# Ambisonic_Clock_Decoder_With_Phase_Shift.net
KiCad netlist of a schematic drawn in EAGLE
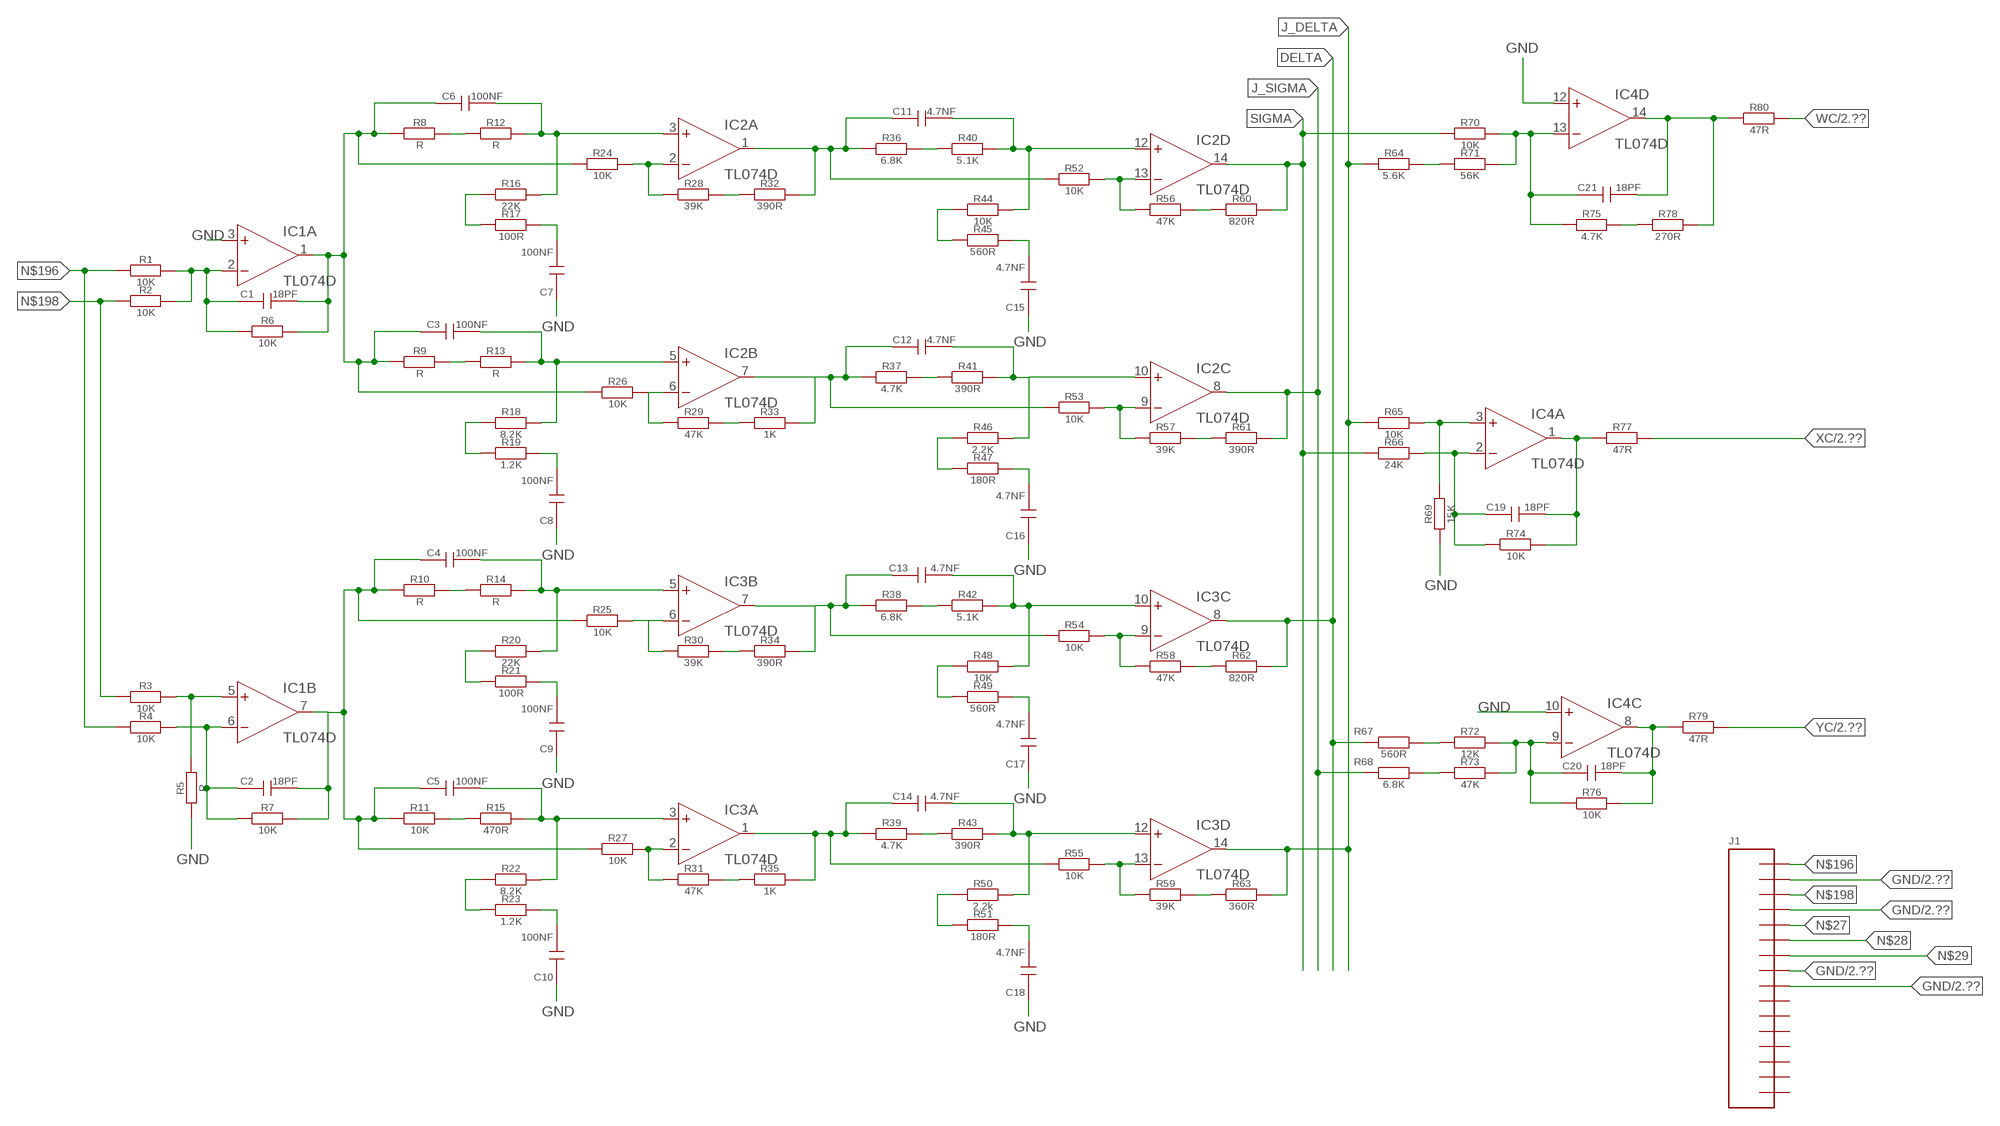
[diagram p0: schematic, sheet 1]
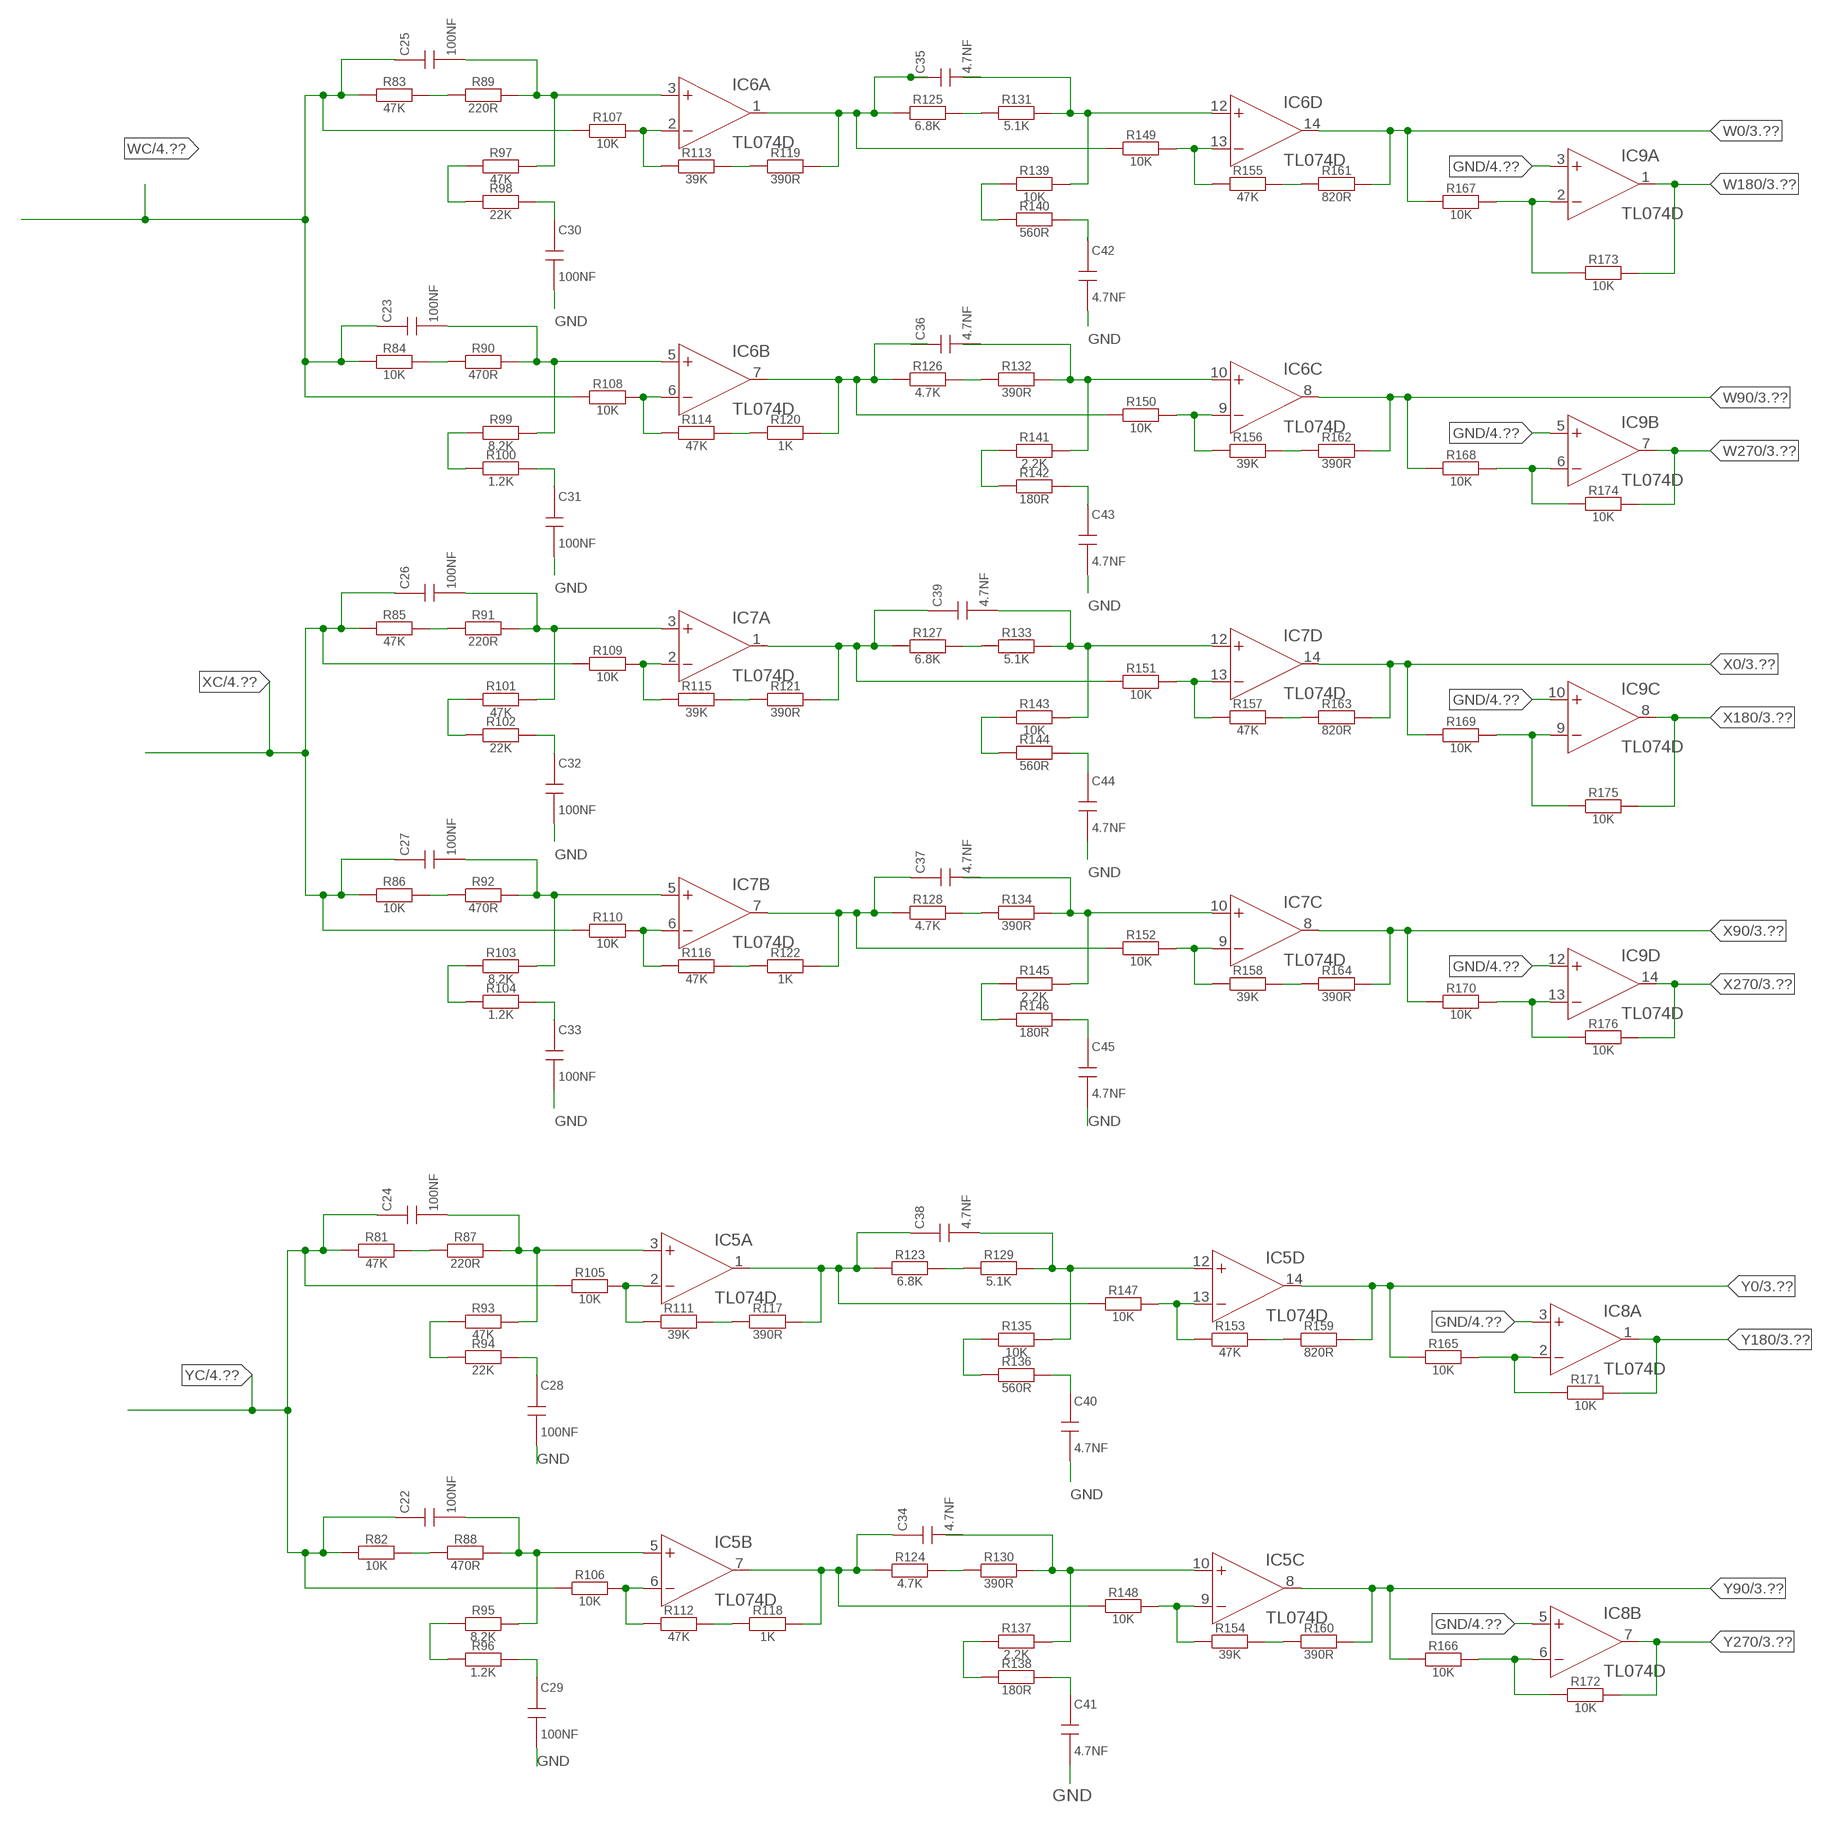
[diagram p1: schematic, sheet 2]
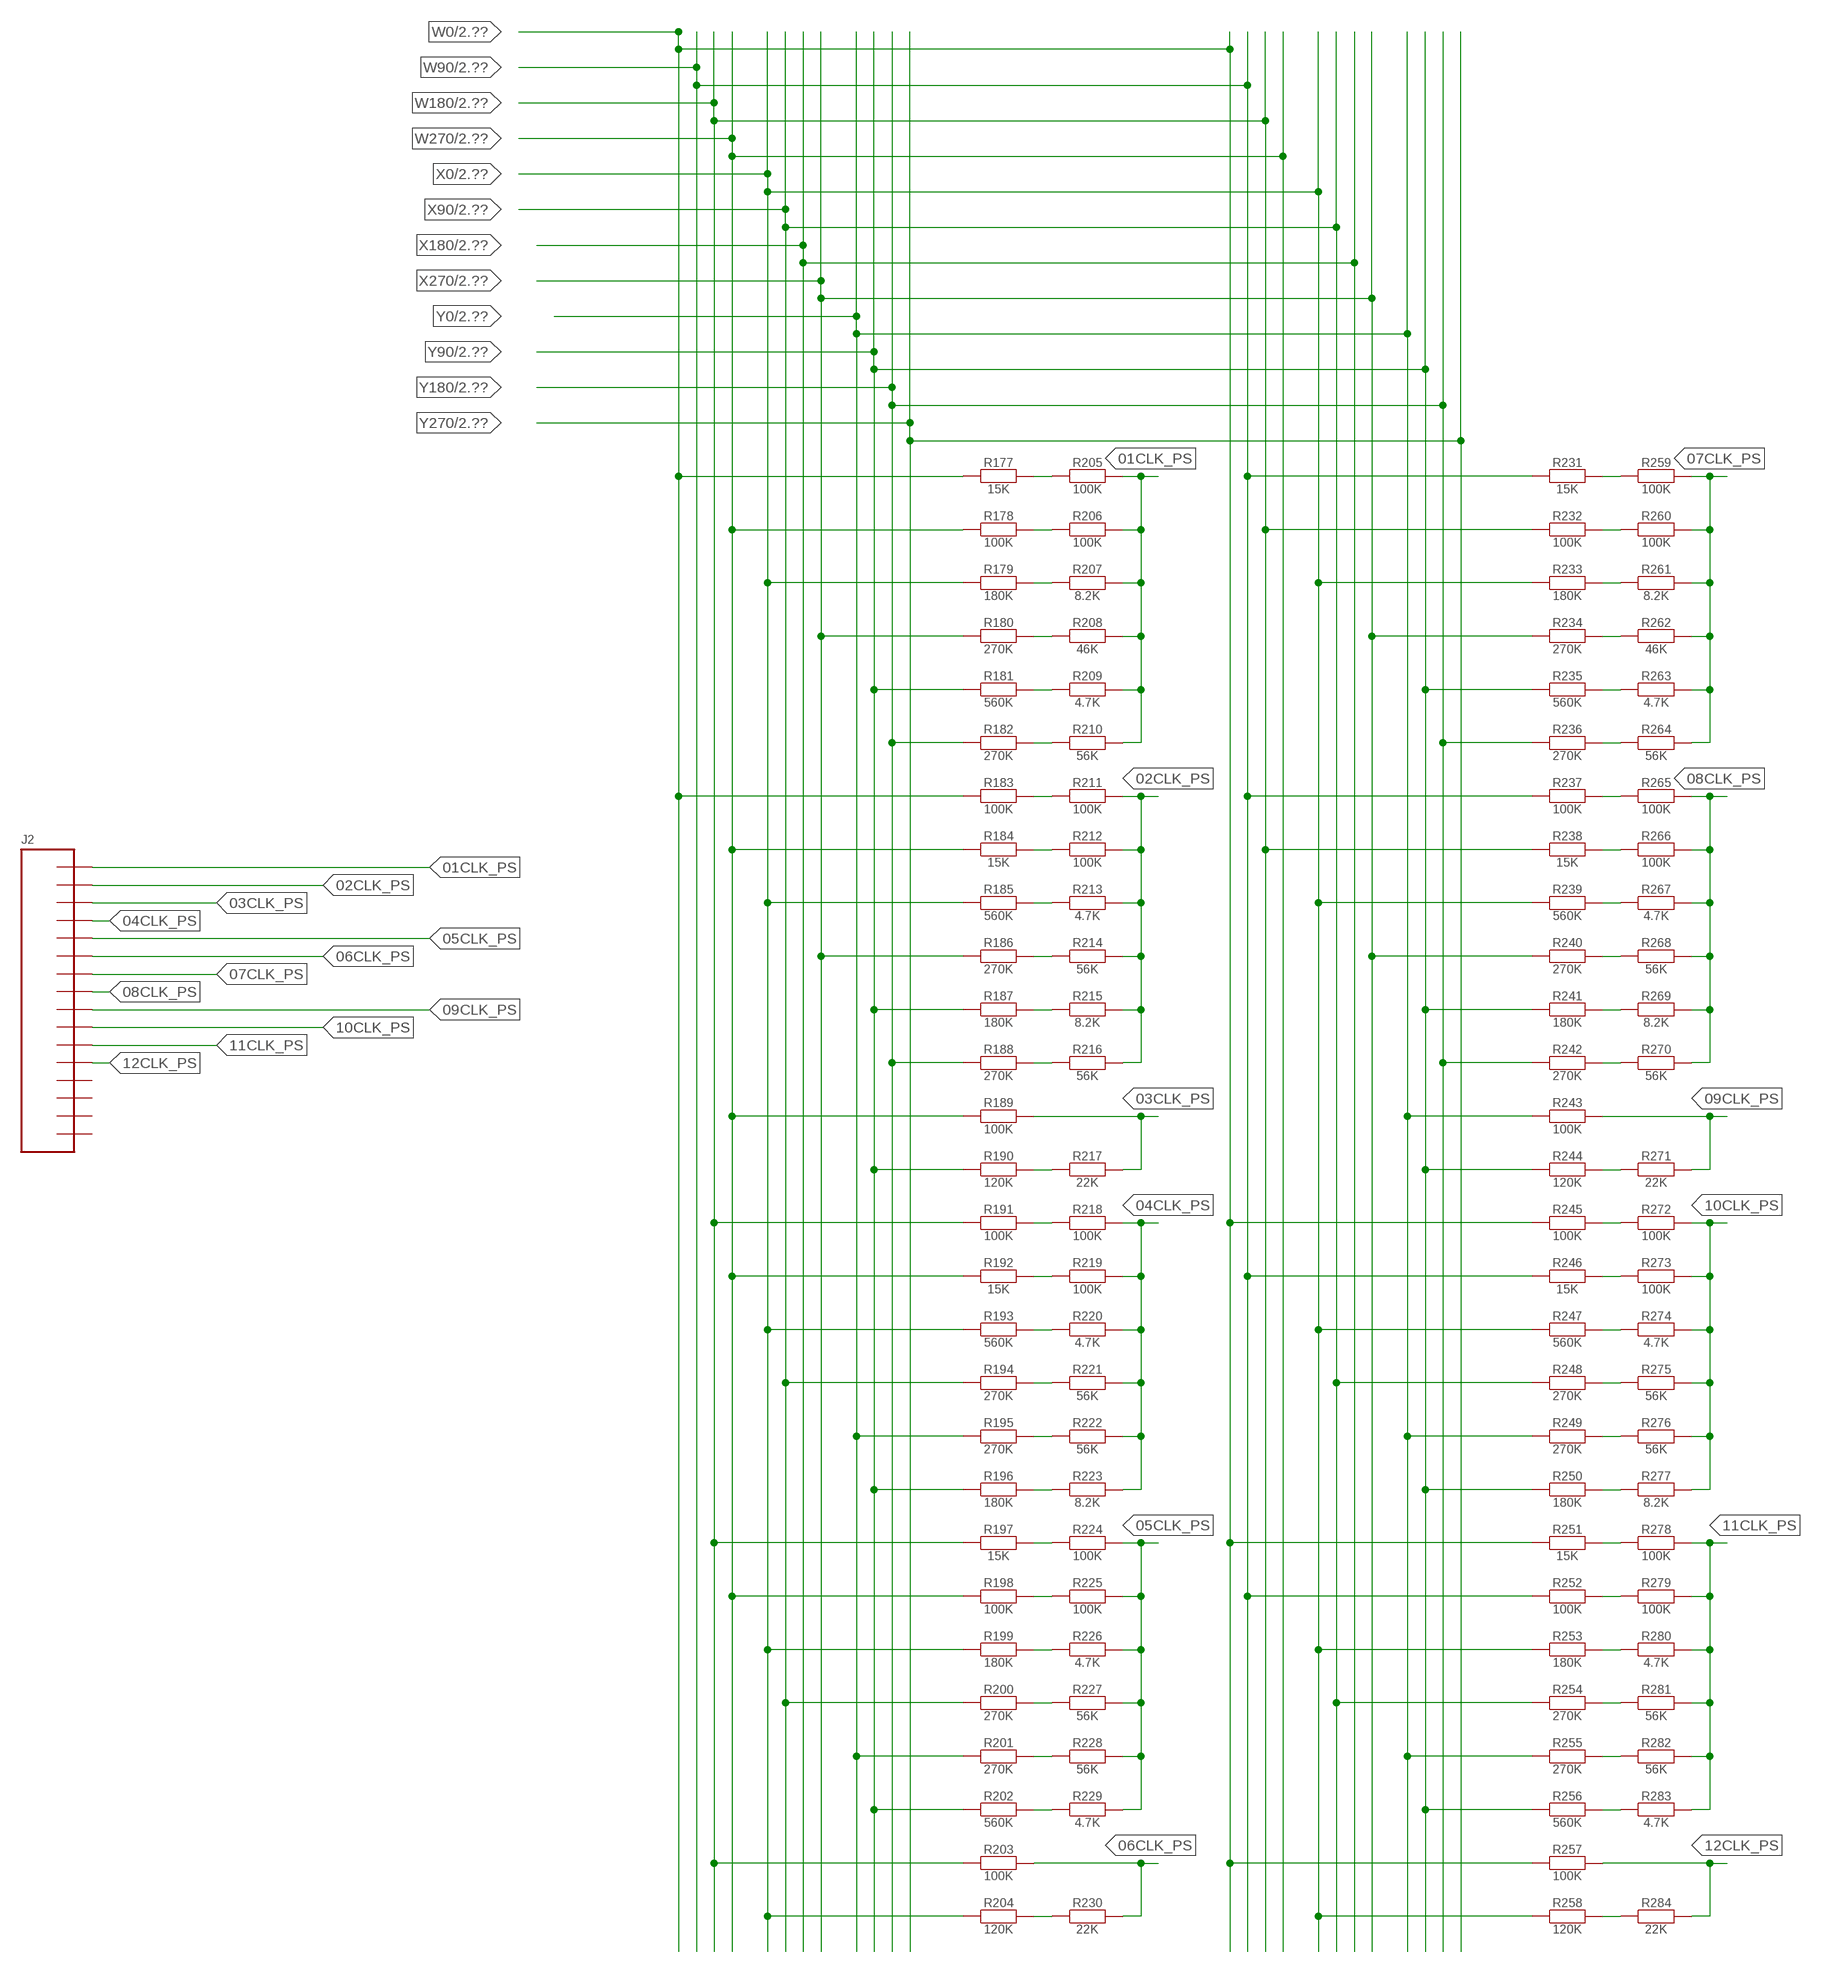
[diagram p2: schematic, sheet 3]
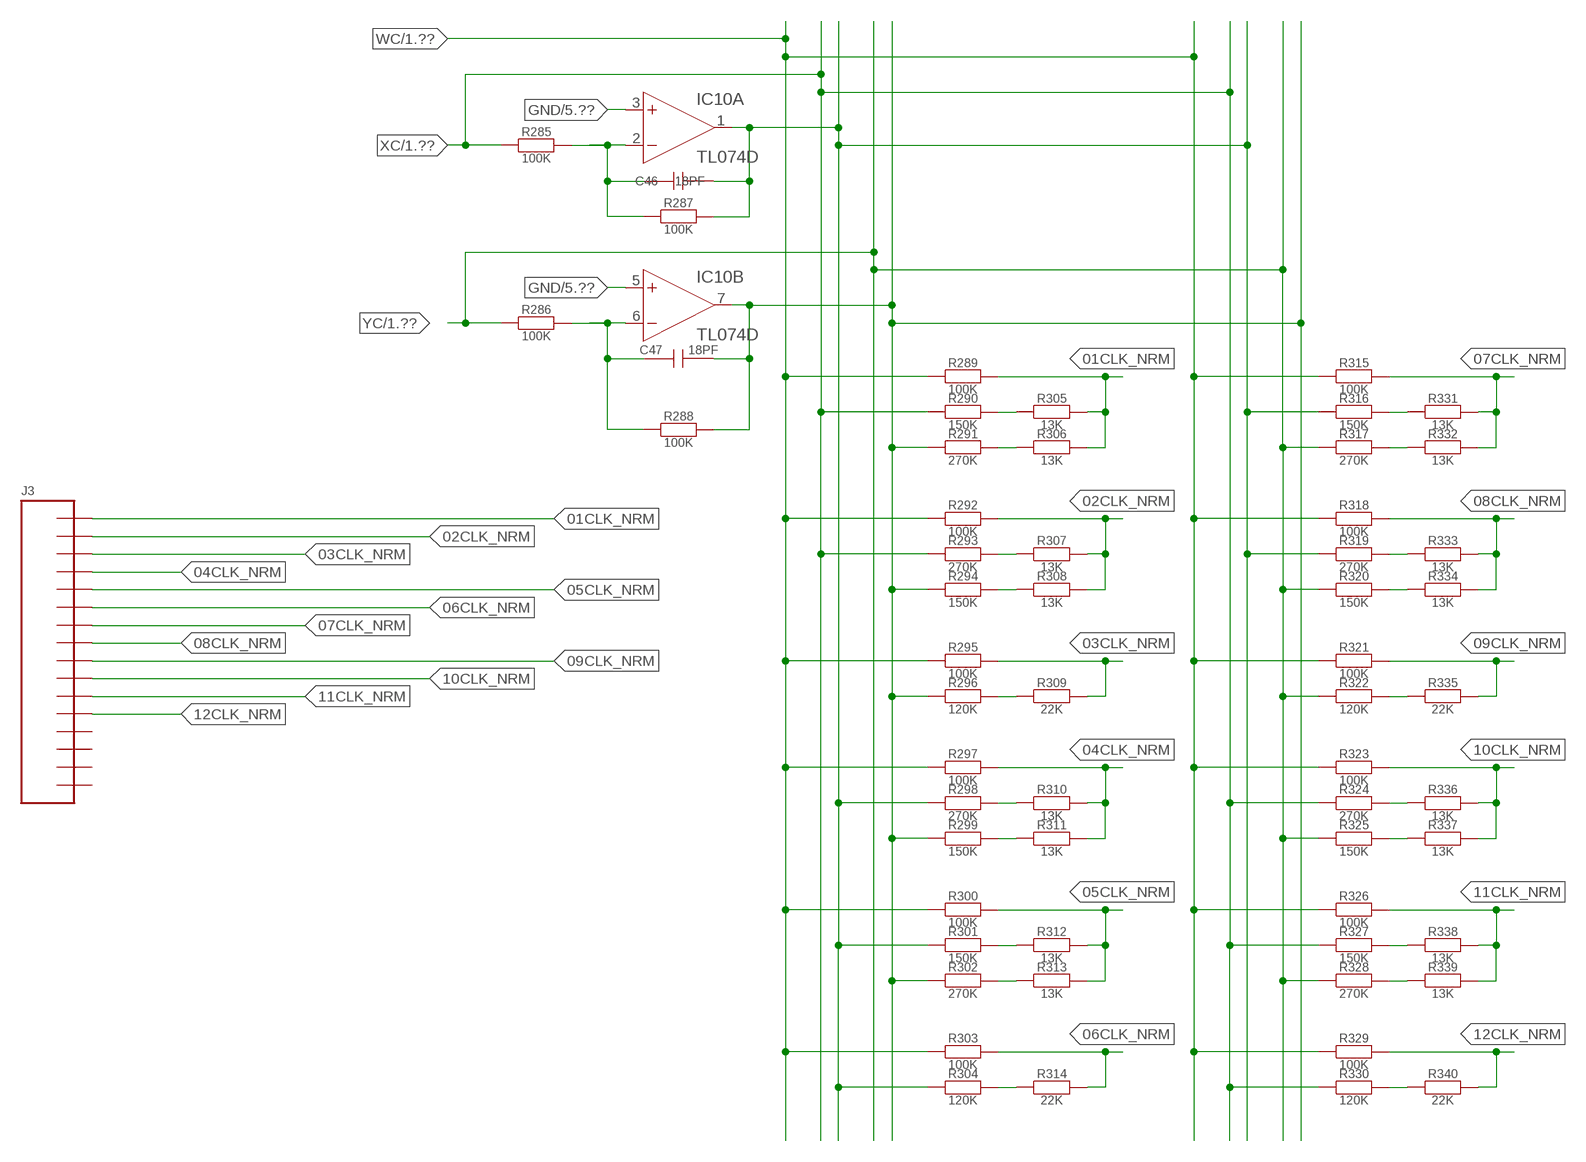
[diagram p3: schematic, sheet 4]
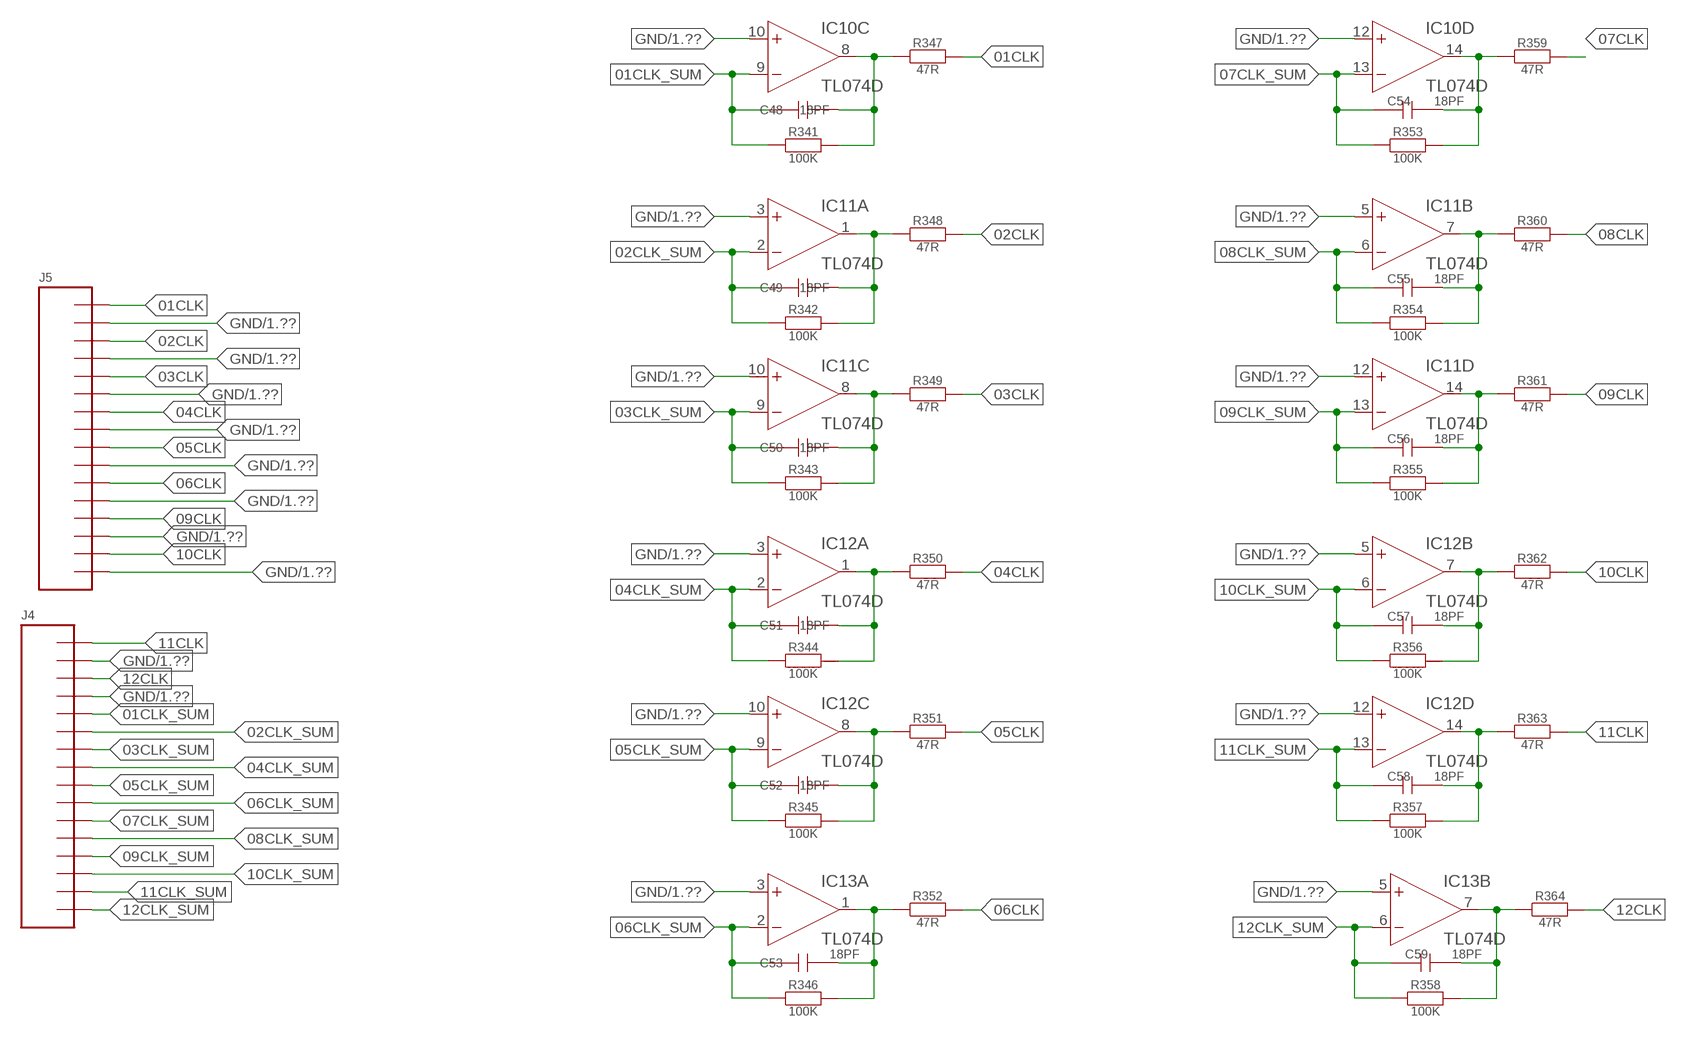
[diagram p4: schematic, sheet 5]

(export (version "E")
  (design (tool "Eeschema 10.0.6"))
  (components
    (comp (ref "J2")
      (value "CON_16")
      (footprint "eagle-import:2X08SMT")
      (libsource (lib "eagle-import") (part "CON_16"))
    )
    (comp (ref "R177")
      (value "15K")
      (footprint "eagle-import:R6332W")
      (libsource (lib "eagle-import") (part "R"))
    )
    (comp (ref "R178")
      (value "100K")
      (footprint "eagle-import:R6332W")
      (libsource (lib "eagle-import") (part "R"))
    )
    (comp (ref "R179")
      (value "180K")
      (footprint "eagle-import:R6332W")
      (libsource (lib "eagle-import") (part "R"))
    )
    (comp (ref "R180")
      (value "270K")
      (footprint "eagle-import:R6332W")
      (libsource (lib "eagle-import") (part "R"))
    )
    (comp (ref "R181")
      (value "560K")
      (footprint "eagle-import:R6332W")
      (libsource (lib "eagle-import") (part "R"))
    )
    (comp (ref "R182")
      (value "270K")
      (footprint "eagle-import:R6332W")
      (libsource (lib "eagle-import") (part "R"))
    )
    (comp (ref "R183")
      (value "100K")
      (footprint "eagle-import:R6332W")
      (libsource (lib "eagle-import") (part "R"))
    )
    (comp (ref "R184")
      (value "15K")
      (footprint "eagle-import:R6332W")
      (libsource (lib "eagle-import") (part "R"))
    )
    (comp (ref "R185")
      (value "560K")
      (footprint "eagle-import:R6332W")
      (libsource (lib "eagle-import") (part "R"))
    )
    (comp (ref "R186")
      (value "270K")
      (footprint "eagle-import:R6332W")
      (libsource (lib "eagle-import") (part "R"))
    )
    (comp (ref "R187")
      (value "180K")
      (footprint "eagle-import:R6332W")
      (libsource (lib "eagle-import") (part "R"))
    )
    (comp (ref "R188")
      (value "270K")
      (footprint "eagle-import:R6332W")
      (libsource (lib "eagle-import") (part "R"))
    )
    (comp (ref "R189")
      (value "100K")
      (footprint "eagle-import:R6332W")
      (libsource (lib "eagle-import") (part "R"))
    )
    (comp (ref "R190")
      (value "120K")
      (footprint "eagle-import:R6332W")
      (libsource (lib "eagle-import") (part "R"))
    )
    (comp (ref "R191")
      (value "100K")
      (footprint "eagle-import:R6332W")
      (libsource (lib "eagle-import") (part "R"))
    )
    (comp (ref "R192")
      (value "15K")
      (footprint "eagle-import:R6332W")
      (libsource (lib "eagle-import") (part "R"))
    )
    (comp (ref "R193")
      (value "560K")
      (footprint "eagle-import:R6332W")
      (libsource (lib "eagle-import") (part "R"))
    )
    (comp (ref "R194")
      (value "270K")
      (footprint "eagle-import:R6332W")
      (libsource (lib "eagle-import") (part "R"))
    )
    (comp (ref "R195")
      (value "270K")
      (footprint "eagle-import:R6332W")
      (libsource (lib "eagle-import") (part "R"))
    )
    (comp (ref "R196")
      (value "180K")
      (footprint "eagle-import:R6332W")
      (libsource (lib "eagle-import") (part "R"))
    )
    (comp (ref "R197")
      (value "15K")
      (footprint "eagle-import:R6332W")
      (libsource (lib "eagle-import") (part "R"))
    )
    (comp (ref "R198")
      (value "100K")
      (footprint "eagle-import:R6332W")
      (libsource (lib "eagle-import") (part "R"))
    )
    (comp (ref "R199")
      (value "180K")
      (footprint "eagle-import:R6332W")
      (libsource (lib "eagle-import") (part "R"))
    )
    (comp (ref "R200")
      (value "270K")
      (footprint "eagle-import:R6332W")
      (libsource (lib "eagle-import") (part "R"))
    )
    (comp (ref "R201")
      (value "270K")
      (footprint "eagle-import:R6332W")
      (libsource (lib "eagle-import") (part "R"))
    )
    (comp (ref "R202")
      (value "560K")
      (footprint "eagle-import:R6332W")
      (libsource (lib "eagle-import") (part "R"))
    )
    (comp (ref "R203")
      (value "100K")
      (footprint "eagle-import:R6332W")
      (libsource (lib "eagle-import") (part "R"))
    )
    (comp (ref "R204")
      (value "120K")
      (footprint "eagle-import:R6332W")
      (libsource (lib "eagle-import") (part "R"))
    )
    (comp (ref "R205")
      (value "100K")
      (footprint "eagle-import:R6332W")
      (libsource (lib "eagle-import") (part "R"))
    )
    (comp (ref "R206")
      (value "100K")
      (footprint "eagle-import:R6332W")
      (libsource (lib "eagle-import") (part "R"))
    )
    (comp (ref "R207")
      (value "8.2K")
      (footprint "eagle-import:R6332W")
      (libsource (lib "eagle-import") (part "R"))
    )
    (comp (ref "R208")
      (value "46K")
      (footprint "eagle-import:R6332W")
      (libsource (lib "eagle-import") (part "R"))
    )
    (comp (ref "R209")
      (value "4.7K")
      (footprint "eagle-import:R6332W")
      (libsource (lib "eagle-import") (part "R"))
    )
    (comp (ref "R210")
      (value "56K")
      (footprint "eagle-import:R6332W")
      (libsource (lib "eagle-import") (part "R"))
    )
    (comp (ref "R211")
      (value "100K")
      (footprint "eagle-import:R6332W")
      (libsource (lib "eagle-import") (part "R"))
    )
    (comp (ref "R212")
      (value "100K")
      (footprint "eagle-import:R6332W")
      (libsource (lib "eagle-import") (part "R"))
    )
    (comp (ref "R213")
      (value "4.7K")
      (footprint "eagle-import:R6332W")
      (libsource (lib "eagle-import") (part "R"))
    )
    (comp (ref "R214")
      (value "56K")
      (footprint "eagle-import:R6332W")
      (libsource (lib "eagle-import") (part "R"))
    )
    (comp (ref "R215")
      (value "8.2K")
      (footprint "eagle-import:R6332W")
      (libsource (lib "eagle-import") (part "R"))
    )
    (comp (ref "R216")
      (value "56K")
      (footprint "eagle-import:R6332W")
      (libsource (lib "eagle-import") (part "R"))
    )
    (comp (ref "R217")
      (value "22K")
      (footprint "eagle-import:R6332W")
      (libsource (lib "eagle-import") (part "R"))
    )
    (comp (ref "R218")
      (value "100K")
      (footprint "eagle-import:R6332W")
      (libsource (lib "eagle-import") (part "R"))
    )
    (comp (ref "R219")
      (value "100K")
      (footprint "eagle-import:R6332W")
      (libsource (lib "eagle-import") (part "R"))
    )
    (comp (ref "R220")
      (value "4.7K")
      (footprint "eagle-import:R6332W")
      (libsource (lib "eagle-import") (part "R"))
    )
    (comp (ref "R221")
      (value "56K")
      (footprint "eagle-import:R6332W")
      (libsource (lib "eagle-import") (part "R"))
    )
    (comp (ref "R222")
      (value "56K")
      (footprint "eagle-import:R6332W")
      (libsource (lib "eagle-import") (part "R"))
    )
    (comp (ref "R223")
      (value "8.2K")
      (footprint "eagle-import:R6332W")
      (libsource (lib "eagle-import") (part "R"))
    )
    (comp (ref "R224")
      (value "100K")
      (footprint "eagle-import:R6332W")
      (libsource (lib "eagle-import") (part "R"))
    )
    (comp (ref "R225")
      (value "100K")
      (footprint "eagle-import:R6332W")
      (libsource (lib "eagle-import") (part "R"))
    )
    (comp (ref "R226")
      (value "4.7K")
      (footprint "eagle-import:R6332W")
      (libsource (lib "eagle-import") (part "R"))
    )
    (comp (ref "R227")
      (value "56K")
      (footprint "eagle-import:R6332W")
      (libsource (lib "eagle-import") (part "R"))
    )
    (comp (ref "R228")
      (value "56K")
      (footprint "eagle-import:R6332W")
      (libsource (lib "eagle-import") (part "R"))
    )
    (comp (ref "R229")
      (value "4.7K")
      (footprint "eagle-import:R6332W")
      (libsource (lib "eagle-import") (part "R"))
    )
    (comp (ref "R230")
      (value "22K")
      (footprint "eagle-import:R6332W")
      (libsource (lib "eagle-import") (part "R"))
    )
    (comp (ref "R231")
      (value "15K")
      (footprint "eagle-import:R6332W")
      (libsource (lib "eagle-import") (part "R"))
    )
    (comp (ref "R232")
      (value "100K")
      (footprint "eagle-import:R6332W")
      (libsource (lib "eagle-import") (part "R"))
    )
    (comp (ref "R233")
      (value "180K")
      (footprint "eagle-import:R6332W")
      (libsource (lib "eagle-import") (part "R"))
    )
    (comp (ref "R234")
      (value "270K")
      (footprint "eagle-import:R6332W")
      (libsource (lib "eagle-import") (part "R"))
    )
    (comp (ref "R235")
      (value "560K")
      (footprint "eagle-import:R6332W")
      (libsource (lib "eagle-import") (part "R"))
    )
    (comp (ref "R236")
      (value "270K")
      (footprint "eagle-import:R6332W")
      (libsource (lib "eagle-import") (part "R"))
    )
    (comp (ref "R237")
      (value "100K")
      (footprint "eagle-import:R6332W")
      (libsource (lib "eagle-import") (part "R"))
    )
    (comp (ref "R238")
      (value "15K")
      (footprint "eagle-import:R6332W")
      (libsource (lib "eagle-import") (part "R"))
    )
    (comp (ref "R239")
      (value "560K")
      (footprint "eagle-import:R6332W")
      (libsource (lib "eagle-import") (part "R"))
    )
    (comp (ref "R240")
      (value "270K")
      (footprint "eagle-import:R6332W")
      (libsource (lib "eagle-import") (part "R"))
    )
    (comp (ref "R241")
      (value "180K")
      (footprint "eagle-import:R6332W")
      (libsource (lib "eagle-import") (part "R"))
    )
    (comp (ref "R242")
      (value "270K")
      (footprint "eagle-import:R6332W")
      (libsource (lib "eagle-import") (part "R"))
    )
    (comp (ref "R243")
      (value "100K")
      (footprint "eagle-import:R6332W")
      (libsource (lib "eagle-import") (part "R"))
    )
    (comp (ref "R244")
      (value "120K")
      (footprint "eagle-import:R6332W")
      (libsource (lib "eagle-import") (part "R"))
    )
    (comp (ref "R245")
      (value "100K")
      (footprint "eagle-import:R6332W")
      (libsource (lib "eagle-import") (part "R"))
    )
    (comp (ref "R246")
      (value "15K")
      (footprint "eagle-import:R6332W")
      (libsource (lib "eagle-import") (part "R"))
    )
    (comp (ref "R247")
      (value "560K")
      (footprint "eagle-import:R6332W")
      (libsource (lib "eagle-import") (part "R"))
    )
    (comp (ref "R248")
      (value "270K")
      (footprint "eagle-import:R6332W")
      (libsource (lib "eagle-import") (part "R"))
    )
    (comp (ref "R249")
      (value "270K")
      (footprint "eagle-import:R6332W")
      (libsource (lib "eagle-import") (part "R"))
    )
    (comp (ref "R250")
      (value "180K")
      (footprint "eagle-import:R6332W")
      (libsource (lib "eagle-import") (part "R"))
    )
    (comp (ref "R251")
      (value "15K")
      (footprint "eagle-import:R6332W")
      (libsource (lib "eagle-import") (part "R"))
    )
    (comp (ref "R252")
      (value "100K")
      (footprint "eagle-import:R6332W")
      (libsource (lib "eagle-import") (part "R"))
    )
    (comp (ref "R253")
      (value "180K")
      (footprint "eagle-import:R6332W")
      (libsource (lib "eagle-import") (part "R"))
    )
    (comp (ref "R254")
      (value "270K")
      (footprint "eagle-import:R6332W")
      (libsource (lib "eagle-import") (part "R"))
    )
    (comp (ref "R255")
      (value "270K")
      (footprint "eagle-import:R6332W")
      (libsource (lib "eagle-import") (part "R"))
    )
    (comp (ref "R256")
      (value "560K")
      (footprint "eagle-import:R6332W")
      (libsource (lib "eagle-import") (part "R"))
    )
    (comp (ref "R257")
      (value "100K")
      (footprint "eagle-import:R6332W")
      (libsource (lib "eagle-import") (part "R"))
    )
    (comp (ref "R258")
      (value "120K")
      (footprint "eagle-import:R6332W")
      (libsource (lib "eagle-import") (part "R"))
    )
    (comp (ref "R259")
      (value "100K")
      (footprint "eagle-import:R6332W")
      (libsource (lib "eagle-import") (part "R"))
    )
    (comp (ref "R260")
      (value "100K")
      (footprint "eagle-import:R6332W")
      (libsource (lib "eagle-import") (part "R"))
    )
    (comp (ref "R261")
      (value "8.2K")
      (footprint "eagle-import:R6332W")
      (libsource (lib "eagle-import") (part "R"))
    )
    (comp (ref "R262")
      (value "46K")
      (footprint "eagle-import:R6332W")
      (libsource (lib "eagle-import") (part "R"))
    )
    (comp (ref "R263")
      (value "4.7K")
      (footprint "eagle-import:R6332W")
      (libsource (lib "eagle-import") (part "R"))
    )
    (comp (ref "R264")
      (value "56K")
      (footprint "eagle-import:R6332W")
      (libsource (lib "eagle-import") (part "R"))
    )
    (comp (ref "R265")
      (value "100K")
      (footprint "eagle-import:R6332W")
      (libsource (lib "eagle-import") (part "R"))
    )
    (comp (ref "R266")
      (value "100K")
      (footprint "eagle-import:R6332W")
      (libsource (lib "eagle-import") (part "R"))
    )
    (comp (ref "R267")
      (value "4.7K")
      (footprint "eagle-import:R6332W")
      (libsource (lib "eagle-import") (part "R"))
    )
    (comp (ref "R268")
      (value "56K")
      (footprint "eagle-import:R6332W")
      (libsource (lib "eagle-import") (part "R"))
    )
    (comp (ref "R269")
      (value "8.2K")
      (footprint "eagle-import:R6332W")
      (libsource (lib "eagle-import") (part "R"))
    )
    (comp (ref "R270")
      (value "56K")
      (footprint "eagle-import:R6332W")
      (libsource (lib "eagle-import") (part "R"))
    )
    (comp (ref "R271")
      (value "22K")
      (footprint "eagle-import:R6332W")
      (libsource (lib "eagle-import") (part "R"))
    )
    (comp (ref "R272")
      (value "100K")
      (footprint "eagle-import:R6332W")
      (libsource (lib "eagle-import") (part "R"))
    )
    (comp (ref "R273")
      (value "100K")
      (footprint "eagle-import:R6332W")
      (libsource (lib "eagle-import") (part "R"))
    )
    (comp (ref "R274")
      (value "4.7K")
      (footprint "eagle-import:R6332W")
      (libsource (lib "eagle-import") (part "R"))
    )
    (comp (ref "R275")
      (value "56K")
      (footprint "eagle-import:R6332W")
      (libsource (lib "eagle-import") (part "R"))
    )
    (comp (ref "R276")
      (value "56K")
      (footprint "eagle-import:R6332W")
      (libsource (lib "eagle-import") (part "R"))
    )
    (comp (ref "R277")
      (value "8.2K")
      (footprint "eagle-import:R6332W")
      (libsource (lib "eagle-import") (part "R"))
    )
    (comp (ref "R278")
      (value "100K")
      (footprint "eagle-import:R6332W")
      (libsource (lib "eagle-import") (part "R"))
    )
    (comp (ref "R279")
      (value "100K")
      (footprint "eagle-import:R6332W")
      (libsource (lib "eagle-import") (part "R"))
    )
    (comp (ref "R280")
      (value "4.7K")
      (footprint "eagle-import:R6332W")
      (libsource (lib "eagle-import") (part "R"))
    )
    (comp (ref "R281")
      (value "56K")
      (footprint "eagle-import:R6332W")
      (libsource (lib "eagle-import") (part "R"))
    )
    (comp (ref "R282")
      (value "56K")
      (footprint "eagle-import:R6332W")
      (libsource (lib "eagle-import") (part "R"))
    )
    (comp (ref "R283")
      (value "4.7K")
      (footprint "eagle-import:R6332W")
      (libsource (lib "eagle-import") (part "R"))
    )
    (comp (ref "R284")
      (value "22K")
      (footprint "eagle-import:R6332W")
      (libsource (lib "eagle-import") (part "R"))
    )
    (comp (ref "C46")
      (value "18PF")
      (footprint "eagle-import:CT6032")
      (libsource (lib "eagle-import") (part "C"))
    )
    (comp (ref "C47")
      (value "18PF")
      (footprint "eagle-import:CT6032")
      (libsource (lib "eagle-import") (part "C"))
    )
    (comp (ref "IC10")
      (value "TL074D")
      (footprint "eagle-import:SO14")
      (libsource (lib "eagle-import") (part "TL074D"))
    )
    (comp (ref "J3")
      (value "CON_16")
      (footprint "eagle-import:2X08SMT")
      (libsource (lib "eagle-import") (part "CON_16"))
    )
    (comp (ref "R285")
      (value "100K")
      (footprint "eagle-import:R6332W")
      (libsource (lib "eagle-import") (part "R"))
    )
    (comp (ref "R286")
      (value "100K")
      (footprint "eagle-import:R6332W")
      (libsource (lib "eagle-import") (part "R"))
    )
    (comp (ref "R287")
      (value "100K")
      (footprint "eagle-import:R6332W")
      (libsource (lib "eagle-import") (part "R"))
    )
    (comp (ref "R288")
      (value "100K")
      (footprint "eagle-import:R6332W")
      (libsource (lib "eagle-import") (part "R"))
    )
    (comp (ref "R289")
      (value "100K")
      (footprint "eagle-import:R6332W")
      (libsource (lib "eagle-import") (part "R"))
    )
    (comp (ref "R290")
      (value "150K")
      (footprint "eagle-import:R6332W")
      (libsource (lib "eagle-import") (part "R"))
    )
    (comp (ref "R291")
      (value "270K")
      (footprint "eagle-import:R6332W")
      (libsource (lib "eagle-import") (part "R"))
    )
    (comp (ref "R292")
      (value "100K")
      (footprint "eagle-import:R6332W")
      (libsource (lib "eagle-import") (part "R"))
    )
    (comp (ref "R293")
      (value "270K")
      (footprint "eagle-import:R6332W")
      (libsource (lib "eagle-import") (part "R"))
    )
    (comp (ref "R294")
      (value "150K")
      (footprint "eagle-import:R6332W")
      (libsource (lib "eagle-import") (part "R"))
    )
    (comp (ref "R295")
      (value "100K")
      (footprint "eagle-import:R6332W")
      (libsource (lib "eagle-import") (part "R"))
    )
    (comp (ref "R296")
      (value "120K")
      (footprint "eagle-import:R6332W")
      (libsource (lib "eagle-import") (part "R"))
    )
    (comp (ref "R297")
      (value "100K")
      (footprint "eagle-import:R6332W")
      (libsource (lib "eagle-import") (part "R"))
    )
    (comp (ref "R298")
      (value "270K")
      (footprint "eagle-import:R6332W")
      (libsource (lib "eagle-import") (part "R"))
    )
    (comp (ref "R299")
      (value "150K")
      (footprint "eagle-import:R6332W")
      (libsource (lib "eagle-import") (part "R"))
    )
    (comp (ref "R300")
      (value "100K")
      (footprint "eagle-import:R6332W")
      (libsource (lib "eagle-import") (part "R"))
    )
    (comp (ref "R301")
      (value "150K")
      (footprint "eagle-import:R6332W")
      (libsource (lib "eagle-import") (part "R"))
    )
    (comp (ref "R302")
      (value "270K")
      (footprint "eagle-import:R6332W")
      (libsource (lib "eagle-import") (part "R"))
    )
    (comp (ref "R303")
      (value "100K")
      (footprint "eagle-import:R6332W")
      (libsource (lib "eagle-import") (part "R"))
    )
    (comp (ref "R304")
      (value "120K")
      (footprint "eagle-import:R6332W")
      (libsource (lib "eagle-import") (part "R"))
    )
    (comp (ref "R305")
      (value "13K")
      (footprint "eagle-import:R6332W")
      (libsource (lib "eagle-import") (part "R"))
    )
    (comp (ref "R306")
      (value "13K")
      (footprint "eagle-import:R6332W")
      (libsource (lib "eagle-import") (part "R"))
    )
    (comp (ref "R307")
      (value "13K")
      (footprint "eagle-import:R6332W")
      (libsource (lib "eagle-import") (part "R"))
    )
    (comp (ref "R308")
      (value "13K")
      (footprint "eagle-import:R6332W")
      (libsource (lib "eagle-import") (part "R"))
    )
    (comp (ref "R309")
      (value "22K")
      (footprint "eagle-import:R6332W")
      (libsource (lib "eagle-import") (part "R"))
    )
    (comp (ref "R310")
      (value "13K")
      (footprint "eagle-import:R6332W")
      (libsource (lib "eagle-import") (part "R"))
    )
    (comp (ref "R311")
      (value "13K")
      (footprint "eagle-import:R6332W")
      (libsource (lib "eagle-import") (part "R"))
    )
    (comp (ref "R312")
      (value "13K")
      (footprint "eagle-import:R6332W")
      (libsource (lib "eagle-import") (part "R"))
    )
    (comp (ref "R313")
      (value "13K")
      (footprint "eagle-import:R6332W")
      (libsource (lib "eagle-import") (part "R"))
    )
    (comp (ref "R314")
      (value "22K")
      (footprint "eagle-import:R6332W")
      (libsource (lib "eagle-import") (part "R"))
    )
    (comp (ref "R315")
      (value "100K")
      (footprint "eagle-import:R6332W")
      (libsource (lib "eagle-import") (part "R"))
    )
    (comp (ref "R316")
      (value "150K")
      (footprint "eagle-import:R6332W")
      (libsource (lib "eagle-import") (part "R"))
    )
    (comp (ref "R317")
      (value "270K")
      (footprint "eagle-import:R6332W")
      (libsource (lib "eagle-import") (part "R"))
    )
    (comp (ref "R318")
      (value "100K")
      (footprint "eagle-import:R6332W")
      (libsource (lib "eagle-import") (part "R"))
    )
    (comp (ref "R319")
      (value "270K")
      (footprint "eagle-import:R6332W")
      (libsource (lib "eagle-import") (part "R"))
    )
    (comp (ref "R320")
      (value "150K")
      (footprint "eagle-import:R6332W")
      (libsource (lib "eagle-import") (part "R"))
    )
    (comp (ref "R321")
      (value "100K")
      (footprint "eagle-import:R6332W")
      (libsource (lib "eagle-import") (part "R"))
    )
    (comp (ref "R322")
      (value "120K")
      (footprint "eagle-import:R6332W")
      (libsource (lib "eagle-import") (part "R"))
    )
    (comp (ref "R323")
      (value "100K")
      (footprint "eagle-import:R6332W")
      (libsource (lib "eagle-import") (part "R"))
    )
    (comp (ref "R324")
      (value "270K")
      (footprint "eagle-import:R6332W")
      (libsource (lib "eagle-import") (part "R"))
    )
    (comp (ref "R325")
      (value "150K")
      (footprint "eagle-import:R6332W")
      (libsource (lib "eagle-import") (part "R"))
    )
    (comp (ref "R326")
      (value "100K")
      (footprint "eagle-import:R6332W")
      (libsource (lib "eagle-import") (part "R"))
    )
    (comp (ref "R327")
      (value "150K")
      (footprint "eagle-import:R6332W")
      (libsource (lib "eagle-import") (part "R"))
    )
    (comp (ref "R328")
      (value "270K")
      (footprint "eagle-import:R6332W")
      (libsource (lib "eagle-import") (part "R"))
    )
    (comp (ref "R329")
      (value "100K")
      (footprint "eagle-import:R6332W")
      (libsource (lib "eagle-import") (part "R"))
    )
    (comp (ref "R330")
      (value "120K")
      (footprint "eagle-import:R6332W")
      (libsource (lib "eagle-import") (part "R"))
    )
    (comp (ref "R331")
      (value "13K")
      (footprint "eagle-import:R6332W")
      (libsource (lib "eagle-import") (part "R"))
    )
    (comp (ref "R332")
      (value "13K")
      (footprint "eagle-import:R6332W")
      (libsource (lib "eagle-import") (part "R"))
    )
    (comp (ref "R333")
      (value "13K")
      (footprint "eagle-import:R6332W")
      (libsource (lib "eagle-import") (part "R"))
    )
    (comp (ref "R334")
      (value "13K")
      (footprint "eagle-import:R6332W")
      (libsource (lib "eagle-import") (part "R"))
    )
    (comp (ref "R335")
      (value "22K")
      (footprint "eagle-import:R6332W")
      (libsource (lib "eagle-import") (part "R"))
    )
    (comp (ref "R336")
      (value "13K")
      (footprint "eagle-import:R6332W")
      (libsource (lib "eagle-import") (part "R"))
    )
    (comp (ref "R337")
      (value "13K")
      (footprint "eagle-import:R6332W")
      (libsource (lib "eagle-import") (part "R"))
    )
    (comp (ref "R338")
      (value "13K")
      (footprint "eagle-import:R6332W")
      (libsource (lib "eagle-import") (part "R"))
    )
    (comp (ref "R339")
      (value "13K")
      (footprint "eagle-import:R6332W")
      (libsource (lib "eagle-import") (part "R"))
    )
    (comp (ref "R340")
      (value "22K")
      (footprint "eagle-import:R6332W")
      (libsource (lib "eagle-import") (part "R"))
    )
    (comp (ref "C48")
      (value "18PF")
      (footprint "eagle-import:CT6032")
      (libsource (lib "eagle-import") (part "C"))
    )
    (comp (ref "C49")
      (value "18PF")
      (footprint "eagle-import:CT6032")
      (libsource (lib "eagle-import") (part "C"))
    )
    (comp (ref "C50")
      (value "18PF")
      (footprint "eagle-import:CT6032")
      (libsource (lib "eagle-import") (part "C"))
    )
    (comp (ref "C51")
      (value "18PF")
      (footprint "eagle-import:CT6032")
      (libsource (lib "eagle-import") (part "C"))
    )
    (comp (ref "C52")
      (value "18PF")
      (footprint "eagle-import:CT6032")
      (libsource (lib "eagle-import") (part "C"))
    )
    (comp (ref "C53")
      (value "18PF")
      (footprint "eagle-import:CT6032")
      (libsource (lib "eagle-import") (part "C"))
    )
    (comp (ref "C54")
      (value "18PF")
      (footprint "eagle-import:CT6032")
      (libsource (lib "eagle-import") (part "C"))
    )
    (comp (ref "C55")
      (value "18PF")
      (footprint "eagle-import:CT6032")
      (libsource (lib "eagle-import") (part "C"))
    )
    (comp (ref "C56")
      (value "18PF")
      (footprint "eagle-import:CT6032")
      (libsource (lib "eagle-import") (part "C"))
    )
    (comp (ref "C57")
      (value "18PF")
      (footprint "eagle-import:CT6032")
      (libsource (lib "eagle-import") (part "C"))
    )
    (comp (ref "C58")
      (value "18PF")
      (footprint "eagle-import:CT6032")
      (libsource (lib "eagle-import") (part "C"))
    )
    (comp (ref "C59")
      (value "18PF")
      (footprint "eagle-import:CT6032")
      (libsource (lib "eagle-import") (part "C"))
    )
    (comp (ref "IC11")
      (value "TL074D")
      (footprint "eagle-import:SO14")
      (libsource (lib "eagle-import") (part "TL074D"))
    )
    (comp (ref "IC12")
      (value "TL074D")
      (footprint "eagle-import:SO14")
      (libsource (lib "eagle-import") (part "TL074D"))
    )
    (comp (ref "IC13")
      (value "TL074D")
      (footprint "eagle-import:SO14")
      (libsource (lib "eagle-import") (part "TL074D"))
    )
    (comp (ref "J4")
      (value "CON_16")
      (footprint "eagle-import:2X08SMT")
      (libsource (lib "eagle-import") (part "CON_16"))
    )
    (comp (ref "J5")
      (value "CON_16")
      (footprint "eagle-import:2X08SMT")
      (libsource (lib "eagle-import") (part "CON_16"))
    )
    (comp (ref "R341")
      (value "100K")
      (footprint "eagle-import:R6332W")
      (libsource (lib "eagle-import") (part "R"))
    )
    (comp (ref "R342")
      (value "100K")
      (footprint "eagle-import:R6332W")
      (libsource (lib "eagle-import") (part "R"))
    )
    (comp (ref "R343")
      (value "100K")
      (footprint "eagle-import:R6332W")
      (libsource (lib "eagle-import") (part "R"))
    )
    (comp (ref "R344")
      (value "100K")
      (footprint "eagle-import:R6332W")
      (libsource (lib "eagle-import") (part "R"))
    )
    (comp (ref "R345")
      (value "100K")
      (footprint "eagle-import:R6332W")
      (libsource (lib "eagle-import") (part "R"))
    )
    (comp (ref "R346")
      (value "100K")
      (footprint "eagle-import:R6332W")
      (libsource (lib "eagle-import") (part "R"))
    )
    (comp (ref "R347")
      (value "47R")
      (footprint "eagle-import:R6332W")
      (libsource (lib "eagle-import") (part "R"))
    )
    (comp (ref "R348")
      (value "47R")
      (footprint "eagle-import:R6332W")
      (libsource (lib "eagle-import") (part "R"))
    )
    (comp (ref "R349")
      (value "47R")
      (footprint "eagle-import:R6332W")
      (libsource (lib "eagle-import") (part "R"))
    )
    (comp (ref "R350")
      (value "47R")
      (footprint "eagle-import:R6332W")
      (libsource (lib "eagle-import") (part "R"))
    )
    (comp (ref "R351")
      (value "47R")
      (footprint "eagle-import:R6332W")
      (libsource (lib "eagle-import") (part "R"))
    )
    (comp (ref "R352")
      (value "47R")
      (footprint "eagle-import:R6332W")
      (libsource (lib "eagle-import") (part "R"))
    )
    (comp (ref "R353")
      (value "100K")
      (footprint "eagle-import:R6332W")
      (libsource (lib "eagle-import") (part "R"))
    )
    (comp (ref "R354")
      (value "100K")
      (footprint "eagle-import:R6332W")
      (libsource (lib "eagle-import") (part "R"))
    )
    (comp (ref "R355")
      (value "100K")
      (footprint "eagle-import:R6332W")
      (libsource (lib "eagle-import") (part "R"))
    )
    (comp (ref "R356")
      (value "100K")
      (footprint "eagle-import:R6332W")
      (libsource (lib "eagle-import") (part "R"))
    )
    (comp (ref "R357")
      (value "100K")
      (footprint "eagle-import:R6332W")
      (libsource (lib "eagle-import") (part "R"))
    )
    (comp (ref "R358")
      (value "100K")
      (footprint "eagle-import:R6332W")
      (libsource (lib "eagle-import") (part "R"))
    )
    (comp (ref "R359")
      (value "47R")
      (footprint "eagle-import:R6332W")
      (libsource (lib "eagle-import") (part "R"))
    )
    (comp (ref "R360")
      (value "47R")
      (footprint "eagle-import:R6332W")
      (libsource (lib "eagle-import") (part "R"))
    )
    (comp (ref "R361")
      (value "47R")
      (footprint "eagle-import:R6332W")
      (libsource (lib "eagle-import") (part "R"))
    )
    (comp (ref "R362")
      (value "47R")
      (footprint "eagle-import:R6332W")
      (libsource (lib "eagle-import") (part "R"))
    )
    (comp (ref "R363")
      (value "47R")
      (footprint "eagle-import:R6332W")
      (libsource (lib "eagle-import") (part "R"))
    )
    (comp (ref "R364")
      (value "47R")
      (footprint "eagle-import:R6332W")
      (libsource (lib "eagle-import") (part "R"))
    )
    (comp (ref "C22")
      (value "100NF")
      (footprint "eagle-import:CT6032")
      (libsource (lib "eagle-import") (part "C"))
    )
    (comp (ref "C23")
      (value "100NF")
      (footprint "eagle-import:CT6032")
      (libsource (lib "eagle-import") (part "C"))
    )
    (comp (ref "C24")
      (value "100NF")
      (footprint "eagle-import:CT6032")
      (libsource (lib "eagle-import") (part "C"))
    )
    (comp (ref "C25")
      (value "100NF")
      (footprint "eagle-import:CT6032")
      (libsource (lib "eagle-import") (part "C"))
    )
    (comp (ref "C26")
      (value "100NF")
      (footprint "eagle-import:CT6032")
      (libsource (lib "eagle-import") (part "C"))
    )
    (comp (ref "C27")
      (value "100NF")
      (footprint "eagle-import:CT6032")
      (libsource (lib "eagle-import") (part "C"))
    )
    (comp (ref "C28")
      (value "100NF")
      (footprint "eagle-import:CT6032")
      (libsource (lib "eagle-import") (part "C"))
    )
    (comp (ref "C29")
      (value "100NF")
      (footprint "eagle-import:CT6032")
      (libsource (lib "eagle-import") (part "C"))
    )
    (comp (ref "C30")
      (value "100NF")
      (footprint "eagle-import:CT6032")
      (libsource (lib "eagle-import") (part "C"))
    )
    (comp (ref "C31")
      (value "100NF")
      (footprint "eagle-import:CT6032")
      (libsource (lib "eagle-import") (part "C"))
    )
    (comp (ref "C32")
      (value "100NF")
      (footprint "eagle-import:CT6032")
      (libsource (lib "eagle-import") (part "C"))
    )
    (comp (ref "C33")
      (value "100NF")
      (footprint "eagle-import:CT6032")
      (libsource (lib "eagle-import") (part "C"))
    )
    (comp (ref "C34")
      (value "4.7NF")
      (footprint "eagle-import:CT6032")
      (libsource (lib "eagle-import") (part "C"))
    )
    (comp (ref "C35")
      (value "4.7NF")
      (footprint "eagle-import:CT6032")
      (libsource (lib "eagle-import") (part "C"))
    )
    (comp (ref "C36")
      (value "4.7NF")
      (footprint "eagle-import:CT6032")
      (libsource (lib "eagle-import") (part "C"))
    )
    (comp (ref "C37")
      (value "4.7NF")
      (footprint "eagle-import:CT6032")
      (libsource (lib "eagle-import") (part "C"))
    )
    (comp (ref "C38")
      (value "4.7NF")
      (footprint "eagle-import:CT6032")
      (libsource (lib "eagle-import") (part "C"))
    )
    (comp (ref "C39")
      (value "4.7NF")
      (footprint "eagle-import:CT6032")
      (libsource (lib "eagle-import") (part "C"))
    )
    (comp (ref "C40")
      (value "4.7NF")
      (footprint "eagle-import:CT6032")
      (libsource (lib "eagle-import") (part "C"))
    )
    (comp (ref "C41")
      (value "4.7NF")
      (footprint "eagle-import:CT6032")
      (libsource (lib "eagle-import") (part "C"))
    )
    (comp (ref "C42")
      (value "4.7NF")
      (footprint "eagle-import:CT6032")
      (libsource (lib "eagle-import") (part "C"))
    )
    (comp (ref "C43")
      (value "4.7NF")
      (footprint "eagle-import:CT6032")
      (libsource (lib "eagle-import") (part "C"))
    )
    (comp (ref "C44")
      (value "4.7NF")
      (footprint "eagle-import:CT6032")
      (libsource (lib "eagle-import") (part "C"))
    )
    (comp (ref "C45")
      (value "4.7NF")
      (footprint "eagle-import:CT6032")
      (libsource (lib "eagle-import") (part "C"))
    )
    (comp (ref "IC5")
      (value "TL074D")
      (footprint "eagle-import:SO14")
      (libsource (lib "eagle-import") (part "TL074D"))
    )
    (comp (ref "IC6")
      (value "TL074D")
      (footprint "eagle-import:SO14")
      (libsource (lib "eagle-import") (part "TL074D"))
    )
    (comp (ref "IC7")
      (value "TL074D")
      (footprint "eagle-import:SO14")
      (libsource (lib "eagle-import") (part "TL074D"))
    )
    (comp (ref "IC8")
      (value "TL074D")
      (footprint "eagle-import:SO14")
      (libsource (lib "eagle-import") (part "TL074D"))
    )
    (comp (ref "IC9")
      (value "TL074D")
      (footprint "eagle-import:SO14")
      (libsource (lib "eagle-import") (part "TL074D"))
    )
    (comp (ref "R81")
      (value "47K")
      (footprint "eagle-import:R6332W")
      (libsource (lib "eagle-import") (part "R"))
    )
    (comp (ref "R82")
      (value "10K")
      (footprint "eagle-import:R6332W")
      (libsource (lib "eagle-import") (part "R"))
    )
    (comp (ref "R83")
      (value "47K")
      (footprint "eagle-import:R6332W")
      (libsource (lib "eagle-import") (part "R"))
    )
    (comp (ref "R84")
      (value "10K")
      (footprint "eagle-import:R6332W")
      (libsource (lib "eagle-import") (part "R"))
    )
    (comp (ref "R85")
      (value "47K")
      (footprint "eagle-import:R6332W")
      (libsource (lib "eagle-import") (part "R"))
    )
    (comp (ref "R86")
      (value "10K")
      (footprint "eagle-import:R6332W")
      (libsource (lib "eagle-import") (part "R"))
    )
    (comp (ref "R87")
      (value "220R")
      (footprint "eagle-import:R6332W")
      (libsource (lib "eagle-import") (part "R"))
    )
    (comp (ref "R88")
      (value "470R")
      (footprint "eagle-import:R6332W")
      (libsource (lib "eagle-import") (part "R"))
    )
    (comp (ref "R89")
      (value "220R")
      (footprint "eagle-import:R6332W")
      (libsource (lib "eagle-import") (part "R"))
    )
    (comp (ref "R90")
      (value "470R")
      (footprint "eagle-import:R6332W")
      (libsource (lib "eagle-import") (part "R"))
    )
    (comp (ref "R91")
      (value "220R")
      (footprint "eagle-import:R6332W")
      (libsource (lib "eagle-import") (part "R"))
    )
    (comp (ref "R92")
      (value "470R")
      (footprint "eagle-import:R6332W")
      (libsource (lib "eagle-import") (part "R"))
    )
    (comp (ref "R93")
      (value "47K")
      (footprint "eagle-import:R6332W")
      (libsource (lib "eagle-import") (part "R"))
    )
    (comp (ref "R94")
      (value "22K")
      (footprint "eagle-import:R6332W")
      (libsource (lib "eagle-import") (part "R"))
    )
    (comp (ref "R95")
      (value "8.2K")
      (footprint "eagle-import:R6332W")
      (libsource (lib "eagle-import") (part "R"))
    )
    (comp (ref "R96")
      (value "1.2K")
      (footprint "eagle-import:R6332W")
      (libsource (lib "eagle-import") (part "R"))
    )
    (comp (ref "R97")
      (value "47K")
      (footprint "eagle-import:R6332W")
      (libsource (lib "eagle-import") (part "R"))
    )
    (comp (ref "R98")
      (value "22K")
      (footprint "eagle-import:R6332W")
      (libsource (lib "eagle-import") (part "R"))
    )
    (comp (ref "R99")
      (value "8.2K")
      (footprint "eagle-import:R6332W")
      (libsource (lib "eagle-import") (part "R"))
    )
    (comp (ref "R100")
      (value "1.2K")
      (footprint "eagle-import:R6332W")
      (libsource (lib "eagle-import") (part "R"))
    )
    (comp (ref "R101")
      (value "47K")
      (footprint "eagle-import:R6332W")
      (libsource (lib "eagle-import") (part "R"))
    )
    (comp (ref "R102")
      (value "22K")
      (footprint "eagle-import:R6332W")
      (libsource (lib "eagle-import") (part "R"))
    )
    (comp (ref "R103")
      (value "8.2K")
      (footprint "eagle-import:R6332W")
      (libsource (lib "eagle-import") (part "R"))
    )
    (comp (ref "R104")
      (value "1.2K")
      (footprint "eagle-import:R6332W")
      (libsource (lib "eagle-import") (part "R"))
    )
    (comp (ref "R105")
      (value "10K")
      (footprint "eagle-import:R6332W")
      (libsource (lib "eagle-import") (part "R"))
    )
    (comp (ref "R106")
      (value "10K")
      (footprint "eagle-import:R6332W")
      (libsource (lib "eagle-import") (part "R"))
    )
    (comp (ref "R107")
      (value "10K")
      (footprint "eagle-import:R6332W")
      (libsource (lib "eagle-import") (part "R"))
    )
    (comp (ref "R108")
      (value "10K")
      (footprint "eagle-import:R6332W")
      (libsource (lib "eagle-import") (part "R"))
    )
    (comp (ref "R109")
      (value "10K")
      (footprint "eagle-import:R6332W")
      (libsource (lib "eagle-import") (part "R"))
    )
    (comp (ref "R110")
      (value "10K")
      (footprint "eagle-import:R6332W")
      (libsource (lib "eagle-import") (part "R"))
    )
    (comp (ref "R111")
      (value "39K")
      (footprint "eagle-import:R6332W")
      (libsource (lib "eagle-import") (part "R"))
    )
    (comp (ref "R112")
      (value "47K")
      (footprint "eagle-import:R6332W")
      (libsource (lib "eagle-import") (part "R"))
    )
    (comp (ref "R113")
      (value "39K")
      (footprint "eagle-import:R6332W")
      (libsource (lib "eagle-import") (part "R"))
    )
    (comp (ref "R114")
      (value "47K")
      (footprint "eagle-import:R6332W")
      (libsource (lib "eagle-import") (part "R"))
    )
    (comp (ref "R115")
      (value "39K")
      (footprint "eagle-import:R6332W")
      (libsource (lib "eagle-import") (part "R"))
    )
    (comp (ref "R116")
      (value "47K")
      (footprint "eagle-import:R6332W")
      (libsource (lib "eagle-import") (part "R"))
    )
    (comp (ref "R117")
      (value "390R")
      (footprint "eagle-import:R6332W")
      (libsource (lib "eagle-import") (part "R"))
    )
    (comp (ref "R118")
      (value "1K")
      (footprint "eagle-import:R6332W")
      (libsource (lib "eagle-import") (part "R"))
    )
    (comp (ref "R119")
      (value "390R")
      (footprint "eagle-import:R6332W")
      (libsource (lib "eagle-import") (part "R"))
    )
    (comp (ref "R120")
      (value "1K")
      (footprint "eagle-import:R6332W")
      (libsource (lib "eagle-import") (part "R"))
    )
    (comp (ref "R121")
      (value "390R")
      (footprint "eagle-import:R6332W")
      (libsource (lib "eagle-import") (part "R"))
    )
    (comp (ref "R122")
      (value "1K")
      (footprint "eagle-import:R6332W")
      (libsource (lib "eagle-import") (part "R"))
    )
    (comp (ref "R123")
      (value "6.8K")
      (footprint "eagle-import:R6332W")
      (libsource (lib "eagle-import") (part "R"))
    )
    (comp (ref "R124")
      (value "4.7K")
      (footprint "eagle-import:R6332W")
      (libsource (lib "eagle-import") (part "R"))
    )
    (comp (ref "R125")
      (value "6.8K")
      (footprint "eagle-import:R6332W")
      (libsource (lib "eagle-import") (part "R"))
    )
    (comp (ref "R126")
      (value "4.7K")
      (footprint "eagle-import:R6332W")
      (libsource (lib "eagle-import") (part "R"))
    )
    (comp (ref "R127")
      (value "6.8K")
      (footprint "eagle-import:R6332W")
      (libsource (lib "eagle-import") (part "R"))
    )
    (comp (ref "R128")
      (value "4.7K")
      (footprint "eagle-import:R6332W")
      (libsource (lib "eagle-import") (part "R"))
    )
    (comp (ref "R129")
      (value "5.1K")
      (footprint "eagle-import:R6332W")
      (libsource (lib "eagle-import") (part "R"))
    )
    (comp (ref "R130")
      (value "390R")
      (footprint "eagle-import:R6332W")
      (libsource (lib "eagle-import") (part "R"))
    )
    (comp (ref "R131")
      (value "5.1K")
      (footprint "eagle-import:R6332W")
      (libsource (lib "eagle-import") (part "R"))
    )
    (comp (ref "R132")
      (value "390R")
      (footprint "eagle-import:R6332W")
      (libsource (lib "eagle-import") (part "R"))
    )
    (comp (ref "R133")
      (value "5.1K")
      (footprint "eagle-import:R6332W")
      (libsource (lib "eagle-import") (part "R"))
    )
    (comp (ref "R134")
      (value "390R")
      (footprint "eagle-import:R6332W")
      (libsource (lib "eagle-import") (part "R"))
    )
    (comp (ref "R135")
      (value "10K")
      (footprint "eagle-import:R6332W")
      (libsource (lib "eagle-import") (part "R"))
    )
    (comp (ref "R136")
      (value "560R")
      (footprint "eagle-import:R6332W")
      (libsource (lib "eagle-import") (part "R"))
    )
    (comp (ref "R137")
      (value "2.2K")
      (footprint "eagle-import:R6332W")
      (libsource (lib "eagle-import") (part "R"))
    )
    (comp (ref "R138")
      (value "180R")
      (footprint "eagle-import:R6332W")
      (libsource (lib "eagle-import") (part "R"))
    )
    (comp (ref "R139")
      (value "10K")
      (footprint "eagle-import:R6332W")
      (libsource (lib "eagle-import") (part "R"))
    )
    (comp (ref "R140")
      (value "560R")
      (footprint "eagle-import:R6332W")
      (libsource (lib "eagle-import") (part "R"))
    )
    (comp (ref "R141")
      (value "2.2K")
      (footprint "eagle-import:R6332W")
      (libsource (lib "eagle-import") (part "R"))
    )
    (comp (ref "R142")
      (value "180R")
      (footprint "eagle-import:R6332W")
      (libsource (lib "eagle-import") (part "R"))
    )
    (comp (ref "R143")
      (value "10K")
      (footprint "eagle-import:R6332W")
      (libsource (lib "eagle-import") (part "R"))
    )
    (comp (ref "R144")
      (value "560R")
      (footprint "eagle-import:R6332W")
      (libsource (lib "eagle-import") (part "R"))
    )
    (comp (ref "R145")
      (value "2.2K")
      (footprint "eagle-import:R6332W")
      (libsource (lib "eagle-import") (part "R"))
    )
    (comp (ref "R146")
      (value "180R")
      (footprint "eagle-import:R6332W")
      (libsource (lib "eagle-import") (part "R"))
    )
    (comp (ref "R147")
      (value "10K")
      (footprint "eagle-import:R6332W")
      (libsource (lib "eagle-import") (part "R"))
    )
    (comp (ref "R148")
      (value "10K")
      (footprint "eagle-import:R6332W")
      (libsource (lib "eagle-import") (part "R"))
    )
    (comp (ref "R149")
      (value "10K")
      (footprint "eagle-import:R6332W")
      (libsource (lib "eagle-import") (part "R"))
    )
    (comp (ref "R150")
      (value "10K")
      (footprint "eagle-import:R6332W")
      (libsource (lib "eagle-import") (part "R"))
    )
    (comp (ref "R151")
      (value "10K")
      (footprint "eagle-import:R6332W")
      (libsource (lib "eagle-import") (part "R"))
    )
    (comp (ref "R152")
      (value "10K")
      (footprint "eagle-import:R6332W")
      (libsource (lib "eagle-import") (part "R"))
    )
    (comp (ref "R153")
      (value "47K")
      (footprint "eagle-import:R6332W")
      (libsource (lib "eagle-import") (part "R"))
    )
    (comp (ref "R154")
      (value "39K")
      (footprint "eagle-import:R6332W")
      (libsource (lib "eagle-import") (part "R"))
    )
    (comp (ref "R155")
      (value "47K")
      (footprint "eagle-import:R6332W")
      (libsource (lib "eagle-import") (part "R"))
    )
    (comp (ref "R156")
      (value "39K")
      (footprint "eagle-import:R6332W")
      (libsource (lib "eagle-import") (part "R"))
    )
    (comp (ref "R157")
      (value "47K")
      (footprint "eagle-import:R6332W")
      (libsource (lib "eagle-import") (part "R"))
    )
    (comp (ref "R158")
      (value "39K")
      (footprint "eagle-import:R6332W")
      (libsource (lib "eagle-import") (part "R"))
    )
    (comp (ref "R159")
      (value "820R")
      (footprint "eagle-import:R6332W")
      (libsource (lib "eagle-import") (part "R"))
    )
    (comp (ref "R160")
      (value "390R")
      (footprint "eagle-import:R6332W")
      (libsource (lib "eagle-import") (part "R"))
    )
    (comp (ref "R161")
      (value "820R")
      (footprint "eagle-import:R6332W")
      (libsource (lib "eagle-import") (part "R"))
    )
    (comp (ref "R162")
      (value "390R")
      (footprint "eagle-import:R6332W")
      (libsource (lib "eagle-import") (part "R"))
    )
    (comp (ref "R163")
      (value "820R")
      (footprint "eagle-import:R6332W")
      (libsource (lib "eagle-import") (part "R"))
    )
    (comp (ref "R164")
      (value "390R")
      (footprint "eagle-import:R6332W")
      (libsource (lib "eagle-import") (part "R"))
    )
    (comp (ref "R165")
      (value "10K")
      (footprint "eagle-import:R6332W")
      (libsource (lib "eagle-import") (part "R"))
    )
    (comp (ref "R166")
      (value "10K")
      (footprint "eagle-import:R6332W")
      (libsource (lib "eagle-import") (part "R"))
    )
    (comp (ref "R167")
      (value "10K")
      (footprint "eagle-import:R6332W")
      (libsource (lib "eagle-import") (part "R"))
    )
    (comp (ref "R168")
      (value "10K")
      (footprint "eagle-import:R6332W")
      (libsource (lib "eagle-import") (part "R"))
    )
    (comp (ref "R169")
      (value "10K")
      (footprint "eagle-import:R6332W")
      (libsource (lib "eagle-import") (part "R"))
    )
    (comp (ref "R170")
      (value "10K")
      (footprint "eagle-import:R6332W")
      (libsource (lib "eagle-import") (part "R"))
    )
    (comp (ref "R171")
      (value "10K")
      (footprint "eagle-import:R6332W")
      (libsource (lib "eagle-import") (part "R"))
    )
    (comp (ref "R172")
      (value "10K")
      (footprint "eagle-import:R6332W")
      (libsource (lib "eagle-import") (part "R"))
    )
    (comp (ref "R173")
      (value "10K")
      (footprint "eagle-import:R6332W")
      (libsource (lib "eagle-import") (part "R"))
    )
    (comp (ref "R174")
      (value "10K")
      (footprint "eagle-import:R6332W")
      (libsource (lib "eagle-import") (part "R"))
    )
    (comp (ref "R175")
      (value "10K")
      (footprint "eagle-import:R6332W")
      (libsource (lib "eagle-import") (part "R"))
    )
    (comp (ref "R176")
      (value "10K")
      (footprint "eagle-import:R6332W")
      (libsource (lib "eagle-import") (part "R"))
    )
    (comp (ref "C1")
      (value "18PF")
      (footprint "eagle-import:CT6032")
      (libsource (lib "eagle-import") (part "C"))
    )
    (comp (ref "C2")
      (value "18PF")
      (footprint "eagle-import:CT6032")
      (libsource (lib "eagle-import") (part "C"))
    )
    (comp (ref "C3")
      (value "100NF")
      (footprint "eagle-import:CT6032")
      (libsource (lib "eagle-import") (part "C"))
    )
    (comp (ref "C4")
      (value "100NF")
      (footprint "eagle-import:CT6032")
      (libsource (lib "eagle-import") (part "C"))
    )
    (comp (ref "C5")
      (value "100NF")
      (footprint "eagle-import:CT6032")
      (libsource (lib "eagle-import") (part "C"))
    )
    (comp (ref "C6")
      (value "100NF")
      (footprint "eagle-import:CT6032")
      (libsource (lib "eagle-import") (part "C"))
    )
    (comp (ref "C7")
      (value "100NF")
      (footprint "eagle-import:CT6032")
      (libsource (lib "eagle-import") (part "C"))
    )
    (comp (ref "C8")
      (value "100NF")
      (footprint "eagle-import:CT6032")
      (libsource (lib "eagle-import") (part "C"))
    )
    (comp (ref "C9")
      (value "100NF")
      (footprint "eagle-import:CT6032")
      (libsource (lib "eagle-import") (part "C"))
    )
    (comp (ref "C10")
      (value "100NF")
      (footprint "eagle-import:CT6032")
      (libsource (lib "eagle-import") (part "C"))
    )
    (comp (ref "C11")
      (value "4.7NF")
      (footprint "eagle-import:CT6032")
      (libsource (lib "eagle-import") (part "C"))
    )
    (comp (ref "C12")
      (value "4.7NF")
      (footprint "eagle-import:CT6032")
      (libsource (lib "eagle-import") (part "C"))
    )
    (comp (ref "C13")
      (value "4.7NF")
      (footprint "eagle-import:CT6032")
      (libsource (lib "eagle-import") (part "C"))
    )
    (comp (ref "C14")
      (value "4.7NF")
      (footprint "eagle-import:CT6032")
      (libsource (lib "eagle-import") (part "C"))
    )
    (comp (ref "C15")
      (value "4.7NF")
      (footprint "eagle-import:CT6032")
      (libsource (lib "eagle-import") (part "C"))
    )
    (comp (ref "C16")
      (value "4.7NF")
      (footprint "eagle-import:CT6032")
      (libsource (lib "eagle-import") (part "C"))
    )
    (comp (ref "C17")
      (value "4.7NF")
      (footprint "eagle-import:CT6032")
      (libsource (lib "eagle-import") (part "C"))
    )
    (comp (ref "C18")
      (value "4.7NF")
      (footprint "eagle-import:CT6032")
      (libsource (lib "eagle-import") (part "C"))
    )
    (comp (ref "C19")
      (value "18PF")
      (footprint "eagle-import:CT6032")
      (libsource (lib "eagle-import") (part "C"))
    )
    (comp (ref "C20")
      (value "18PF")
      (footprint "eagle-import:CT6032")
      (libsource (lib "eagle-import") (part "C"))
    )
    (comp (ref "C21")
      (value "18PF")
      (footprint "eagle-import:CT6032")
      (libsource (lib "eagle-import") (part "C"))
    )
    (comp (ref "IC1")
      (value "TL074D")
      (footprint "eagle-import:SO14")
      (libsource (lib "eagle-import") (part "TL074D"))
    )
    (comp (ref "IC2")
      (value "TL074D")
      (footprint "eagle-import:SO14")
      (libsource (lib "eagle-import") (part "TL074D"))
    )
    (comp (ref "IC3")
      (value "TL074D")
      (footprint "eagle-import:SO14")
      (libsource (lib "eagle-import") (part "TL074D"))
    )
    (comp (ref "IC4")
      (value "TL074D")
      (footprint "eagle-import:SO14")
      (libsource (lib "eagle-import") (part "TL074D"))
    )
    (comp (ref "J1")
      (value "CON_16")
      (footprint "eagle-import:2X08SMT")
      (libsource (lib "eagle-import") (part "CON_16"))
    )
    (comp (ref "R1")
      (value "10K")
      (footprint "eagle-import:R6332W")
      (libsource (lib "eagle-import") (part "R"))
    )
    (comp (ref "R2")
      (value "10K")
      (footprint "eagle-import:R6332W")
      (libsource (lib "eagle-import") (part "R"))
    )
    (comp (ref "R3")
      (value "10K")
      (footprint "eagle-import:R6332W")
      (libsource (lib "eagle-import") (part "R"))
    )
    (comp (ref "R4")
      (value "10K")
      (footprint "eagle-import:R6332W")
      (libsource (lib "eagle-import") (part "R"))
    )
    (comp (ref "R5")
      (value "R")
      (footprint "eagle-import:R6332W")
      (libsource (lib "eagle-import") (part "R"))
    )
    (comp (ref "R6")
      (value "10K")
      (footprint "eagle-import:R6332W")
      (libsource (lib "eagle-import") (part "R"))
    )
    (comp (ref "R7")
      (value "10K")
      (footprint "eagle-import:R6332W")
      (libsource (lib "eagle-import") (part "R"))
    )
    (comp (ref "R8")
      (value "R")
      (footprint "eagle-import:R6332W")
      (libsource (lib "eagle-import") (part "R"))
    )
    (comp (ref "R9")
      (value "R")
      (footprint "eagle-import:R6332W")
      (libsource (lib "eagle-import") (part "R"))
    )
    (comp (ref "R10")
      (value "R")
      (footprint "eagle-import:R6332W")
      (libsource (lib "eagle-import") (part "R"))
    )
    (comp (ref "R11")
      (value "10K")
      (footprint "eagle-import:R6332W")
      (libsource (lib "eagle-import") (part "R"))
    )
    (comp (ref "R12")
      (value "R")
      (footprint "eagle-import:R6332W")
      (libsource (lib "eagle-import") (part "R"))
    )
    (comp (ref "R13")
      (value "R")
      (footprint "eagle-import:R6332W")
      (libsource (lib "eagle-import") (part "R"))
    )
    (comp (ref "R14")
      (value "R")
      (footprint "eagle-import:R6332W")
      (libsource (lib "eagle-import") (part "R"))
    )
    (comp (ref "R15")
      (value "470R")
      (footprint "eagle-import:R6332W")
      (libsource (lib "eagle-import") (part "R"))
    )
    (comp (ref "R16")
      (value "22K")
      (footprint "eagle-import:R6332W")
      (libsource (lib "eagle-import") (part "R"))
    )
    (comp (ref "R17")
      (value "100R")
      (footprint "eagle-import:R6332W")
      (libsource (lib "eagle-import") (part "R"))
    )
    (comp (ref "R18")
      (value "8.2K")
      (footprint "eagle-import:R6332W")
      (libsource (lib "eagle-import") (part "R"))
    )
    (comp (ref "R19")
      (value "1.2K")
      (footprint "eagle-import:R6332W")
      (libsource (lib "eagle-import") (part "R"))
    )
    (comp (ref "R20")
      (value "22K")
      (footprint "eagle-import:R6332W")
      (libsource (lib "eagle-import") (part "R"))
    )
    (comp (ref "R21")
      (value "100R")
      (footprint "eagle-import:R6332W")
      (libsource (lib "eagle-import") (part "R"))
    )
    (comp (ref "R22")
      (value "8.2K")
      (footprint "eagle-import:R6332W")
      (libsource (lib "eagle-import") (part "R"))
    )
    (comp (ref "R23")
      (value "1.2K")
      (footprint "eagle-import:R6332W")
      (libsource (lib "eagle-import") (part "R"))
    )
    (comp (ref "R24")
      (value "10K")
      (footprint "eagle-import:R6332W")
      (libsource (lib "eagle-import") (part "R"))
    )
    (comp (ref "R25")
      (value "10K")
      (footprint "eagle-import:R6332W")
      (libsource (lib "eagle-import") (part "R"))
    )
    (comp (ref "R26")
      (value "10K")
      (footprint "eagle-import:R6332W")
      (libsource (lib "eagle-import") (part "R"))
    )
    (comp (ref "R27")
      (value "10K")
      (footprint "eagle-import:R6332W")
      (libsource (lib "eagle-import") (part "R"))
    )
    (comp (ref "R28")
      (value "39K")
      (footprint "eagle-import:R6332W")
      (libsource (lib "eagle-import") (part "R"))
    )
    (comp (ref "R29")
      (value "47K")
      (footprint "eagle-import:R6332W")
      (libsource (lib "eagle-import") (part "R"))
    )
    (comp (ref "R30")
      (value "39K")
      (footprint "eagle-import:R6332W")
      (libsource (lib "eagle-import") (part "R"))
    )
    (comp (ref "R31")
      (value "47K")
      (footprint "eagle-import:R6332W")
      (libsource (lib "eagle-import") (part "R"))
    )
    (comp (ref "R32")
      (value "390R")
      (footprint "eagle-import:R6332W")
      (libsource (lib "eagle-import") (part "R"))
    )
    (comp (ref "R33")
      (value "1K")
      (footprint "eagle-import:R6332W")
      (libsource (lib "eagle-import") (part "R"))
    )
    (comp (ref "R34")
      (value "390R")
      (footprint "eagle-import:R6332W")
      (libsource (lib "eagle-import") (part "R"))
    )
    (comp (ref "R35")
      (value "1K")
      (footprint "eagle-import:R6332W")
      (libsource (lib "eagle-import") (part "R"))
    )
    (comp (ref "R36")
      (value "6.8K")
      (footprint "eagle-import:R6332W")
      (libsource (lib "eagle-import") (part "R"))
    )
    (comp (ref "R37")
      (value "4.7K")
      (footprint "eagle-import:R6332W")
      (libsource (lib "eagle-import") (part "R"))
    )
    (comp (ref "R38")
      (value "6.8K")
      (footprint "eagle-import:R6332W")
      (libsource (lib "eagle-import") (part "R"))
    )
    (comp (ref "R39")
      (value "4.7K")
      (footprint "eagle-import:R6332W")
      (libsource (lib "eagle-import") (part "R"))
    )
    (comp (ref "R40")
      (value "5.1K")
      (footprint "eagle-import:R6332W")
      (libsource (lib "eagle-import") (part "R"))
    )
    (comp (ref "R41")
      (value "390R")
      (footprint "eagle-import:R6332W")
      (libsource (lib "eagle-import") (part "R"))
    )
    (comp (ref "R42")
      (value "5.1K")
      (footprint "eagle-import:R6332W")
      (libsource (lib "eagle-import") (part "R"))
    )
    (comp (ref "R43")
      (value "390R")
      (footprint "eagle-import:R6332W")
      (libsource (lib "eagle-import") (part "R"))
    )
    (comp (ref "R44")
      (value "10K")
      (footprint "eagle-import:R6332W")
      (libsource (lib "eagle-import") (part "R"))
    )
    (comp (ref "R45")
      (value "560R")
      (footprint "eagle-import:R6332W")
      (libsource (lib "eagle-import") (part "R"))
    )
    (comp (ref "R46")
      (value "2.2K")
      (footprint "eagle-import:R6332W")
      (libsource (lib "eagle-import") (part "R"))
    )
    (comp (ref "R47")
      (value "180R")
      (footprint "eagle-import:R6332W")
      (libsource (lib "eagle-import") (part "R"))
    )
    (comp (ref "R48")
      (value "10K")
      (footprint "eagle-import:R6332W")
      (libsource (lib "eagle-import") (part "R"))
    )
    (comp (ref "R49")
      (value "560R")
      (footprint "eagle-import:R6332W")
      (libsource (lib "eagle-import") (part "R"))
    )
    (comp (ref "R50")
      (value "2.2k")
      (footprint "eagle-import:R6332W")
      (libsource (lib "eagle-import") (part "R"))
    )
    (comp (ref "R51")
      (value "180R")
      (footprint "eagle-import:R6332W")
      (libsource (lib "eagle-import") (part "R"))
    )
    (comp (ref "R52")
      (value "10K")
      (footprint "eagle-import:R6332W")
      (libsource (lib "eagle-import") (part "R"))
    )
    (comp (ref "R53")
      (value "10K")
      (footprint "eagle-import:R6332W")
      (libsource (lib "eagle-import") (part "R"))
    )
    (comp (ref "R54")
      (value "10K")
      (footprint "eagle-import:R6332W")
      (libsource (lib "eagle-import") (part "R"))
    )
    (comp (ref "R55")
      (value "10K")
      (footprint "eagle-import:R6332W")
      (libsource (lib "eagle-import") (part "R"))
    )
    (comp (ref "R56")
      (value "47K")
      (footprint "eagle-import:R6332W")
      (libsource (lib "eagle-import") (part "R"))
    )
    (comp (ref "R57")
      (value "39K")
      (footprint "eagle-import:R6332W")
      (libsource (lib "eagle-import") (part "R"))
    )
    (comp (ref "R58")
      (value "47K")
      (footprint "eagle-import:R6332W")
      (libsource (lib "eagle-import") (part "R"))
    )
    (comp (ref "R59")
      (value "39K")
      (footprint "eagle-import:R6332W")
      (libsource (lib "eagle-import") (part "R"))
    )
    (comp (ref "R60")
      (value "820R")
      (footprint "eagle-import:R6332W")
      (libsource (lib "eagle-import") (part "R"))
    )
    (comp (ref "R61")
      (value "390R")
      (footprint "eagle-import:R6332W")
      (libsource (lib "eagle-import") (part "R"))
    )
    (comp (ref "R62")
      (value "820R")
      (footprint "eagle-import:R6332W")
      (libsource (lib "eagle-import") (part "R"))
    )
    (comp (ref "R63")
      (value "360R")
      (footprint "eagle-import:R6332W")
      (libsource (lib "eagle-import") (part "R"))
    )
    (comp (ref "R64")
      (value "5.6K")
      (footprint "eagle-import:R6332W")
      (libsource (lib "eagle-import") (part "R"))
    )
    (comp (ref "R65")
      (value "10K")
      (footprint "eagle-import:R6332W")
      (libsource (lib "eagle-import") (part "R"))
    )
    (comp (ref "R66")
      (value "24K")
      (footprint "eagle-import:R6332W")
      (libsource (lib "eagle-import") (part "R"))
    )
    (comp (ref "R67")
      (value "560R")
      (footprint "eagle-import:R6332W")
      (libsource (lib "eagle-import") (part "R"))
    )
    (comp (ref "R68")
      (value "6.8K")
      (footprint "eagle-import:R6332W")
      (libsource (lib "eagle-import") (part "R"))
    )
    (comp (ref "R69")
      (value "15K")
      (footprint "eagle-import:R6332W")
      (libsource (lib "eagle-import") (part "R"))
    )
    (comp (ref "R70")
      (value "10K")
      (footprint "eagle-import:R6332W")
      (libsource (lib "eagle-import") (part "R"))
    )
    (comp (ref "R71")
      (value "56K")
      (footprint "eagle-import:R6332W")
      (libsource (lib "eagle-import") (part "R"))
    )
    (comp (ref "R72")
      (value "12K")
      (footprint "eagle-import:R6332W")
      (libsource (lib "eagle-import") (part "R"))
    )
    (comp (ref "R73")
      (value "47K")
      (footprint "eagle-import:R6332W")
      (libsource (lib "eagle-import") (part "R"))
    )
    (comp (ref "R74")
      (value "10K")
      (footprint "eagle-import:R6332W")
      (libsource (lib "eagle-import") (part "R"))
    )
    (comp (ref "R75")
      (value "4.7K")
      (footprint "eagle-import:R6332W")
      (libsource (lib "eagle-import") (part "R"))
    )
    (comp (ref "R76")
      (value "10K")
      (footprint "eagle-import:R6332W")
      (libsource (lib "eagle-import") (part "R"))
    )
    (comp (ref "R77")
      (value "47R")
      (footprint "eagle-import:R6332W")
      (libsource (lib "eagle-import") (part "R"))
    )
    (comp (ref "R78")
      (value "270R")
      (footprint "eagle-import:R6332W")
      (libsource (lib "eagle-import") (part "R"))
    )
    (comp (ref "R79")
      (value "47R")
      (footprint "eagle-import:R6332W")
      (libsource (lib "eagle-import") (part "R"))
    )
    (comp (ref "R80")
      (value "47R")
      (footprint "eagle-import:R6332W")
      (libsource (lib "eagle-import") (part "R"))
    )
  )
  (nets
    (net (code "1") (name "01CLK") (class "Default")
      (node (ref "J5") (pin "1") (pinfunction "1_1") (pintype "bidirectional"))
      (node (ref "R347") (pin "2") (pinfunction "2_2") (pintype "passive"))
    )
    (net (code "2") (name "01CLK_NRM") (class "Default")
      (node (ref "J3") (pin "1") (pinfunction "1_1") (pintype "bidirectional"))
      (node (ref "R289") (pin "2") (pinfunction "2_2") (pintype "passive"))
      (node (ref "R305") (pin "2") (pinfunction "2_2") (pintype "passive"))
      (node (ref "R306") (pin "2") (pinfunction "2_2") (pintype "passive"))
    )
    (net (code "3") (name "01CLK_PS") (class "Default")
      (node (ref "J2") (pin "1") (pinfunction "1_1") (pintype "bidirectional"))
      (node (ref "R205") (pin "2") (pinfunction "2_2") (pintype "passive"))
      (node (ref "R206") (pin "2") (pinfunction "2_2") (pintype "passive"))
      (node (ref "R207") (pin "2") (pinfunction "2_2") (pintype "passive"))
      (node (ref "R208") (pin "2") (pinfunction "2_2") (pintype "passive"))
      (node (ref "R209") (pin "2") (pinfunction "2_2") (pintype "passive"))
      (node (ref "R210") (pin "2") (pinfunction "2_2") (pintype "passive"))
    )
    (net (code "4") (name "01CLK_SUM") (class "Default")
      (node (ref "C48") (pin "+") (pinfunction "1_+") (pintype "passive"))
      (node (ref "IC10") (pin "9") (pinfunction "-IN_9") (pintype "input"))
      (node (ref "J4") (pin "5") (pinfunction "5_5") (pintype "bidirectional"))
      (node (ref "R341") (pin "1") (pinfunction "1_1") (pintype "passive"))
    )
    (net (code "5") (name "02CLK") (class "Default")
      (node (ref "J5") (pin "3") (pinfunction "3_3") (pintype "bidirectional"))
      (node (ref "R348") (pin "2") (pinfunction "2_2") (pintype "passive"))
    )
    (net (code "6") (name "02CLK_NRM") (class "Default")
      (node (ref "J3") (pin "2") (pinfunction "2_2") (pintype "bidirectional"))
      (node (ref "R292") (pin "2") (pinfunction "2_2") (pintype "passive"))
      (node (ref "R307") (pin "2") (pinfunction "2_2") (pintype "passive"))
      (node (ref "R308") (pin "2") (pinfunction "2_2") (pintype "passive"))
    )
    (net (code "7") (name "02CLK_PS") (class "Default")
      (node (ref "J2") (pin "2") (pinfunction "2_2") (pintype "bidirectional"))
      (node (ref "R211") (pin "2") (pinfunction "2_2") (pintype "passive"))
      (node (ref "R212") (pin "2") (pinfunction "2_2") (pintype "passive"))
      (node (ref "R213") (pin "2") (pinfunction "2_2") (pintype "passive"))
      (node (ref "R214") (pin "2") (pinfunction "2_2") (pintype "passive"))
      (node (ref "R215") (pin "2") (pinfunction "2_2") (pintype "passive"))
      (node (ref "R216") (pin "2") (pinfunction "2_2") (pintype "passive"))
    )
    (net (code "8") (name "02CLK_SUM") (class "Default")
      (node (ref "C49") (pin "+") (pinfunction "1_+") (pintype "passive"))
      (node (ref "IC11") (pin "2") (pinfunction "-IN_2") (pintype "input"))
      (node (ref "J4") (pin "6") (pinfunction "6_6") (pintype "bidirectional"))
      (node (ref "R342") (pin "1") (pinfunction "1_1") (pintype "passive"))
    )
    (net (code "9") (name "03CLK") (class "Default")
      (node (ref "J5") (pin "5") (pinfunction "5_5") (pintype "bidirectional"))
      (node (ref "R349") (pin "2") (pinfunction "2_2") (pintype "passive"))
    )
    (net (code "10") (name "03CLK_NRM") (class "Default")
      (node (ref "J3") (pin "3") (pinfunction "3_3") (pintype "bidirectional"))
      (node (ref "R295") (pin "2") (pinfunction "2_2") (pintype "passive"))
      (node (ref "R309") (pin "2") (pinfunction "2_2") (pintype "passive"))
    )
    (net (code "11") (name "03CLK_PS") (class "Default")
      (node (ref "J2") (pin "3") (pinfunction "3_3") (pintype "bidirectional"))
      (node (ref "R189") (pin "2") (pinfunction "2_2") (pintype "passive"))
      (node (ref "R217") (pin "2") (pinfunction "2_2") (pintype "passive"))
    )
    (net (code "12") (name "03CLK_SUM") (class "Default")
      (node (ref "C50") (pin "+") (pinfunction "1_+") (pintype "passive"))
      (node (ref "IC11") (pin "9") (pinfunction "-IN_9") (pintype "input"))
      (node (ref "J4") (pin "7") (pinfunction "7_7") (pintype "bidirectional"))
      (node (ref "R343") (pin "1") (pinfunction "1_1") (pintype "passive"))
    )
    (net (code "13") (name "04CLK") (class "Default")
      (node (ref "J5") (pin "7") (pinfunction "7_7") (pintype "bidirectional"))
      (node (ref "R350") (pin "2") (pinfunction "2_2") (pintype "passive"))
    )
    (net (code "14") (name "04CLK_NRM") (class "Default")
      (node (ref "J3") (pin "4") (pinfunction "4_4") (pintype "bidirectional"))
      (node (ref "R297") (pin "2") (pinfunction "2_2") (pintype "passive"))
      (node (ref "R310") (pin "2") (pinfunction "2_2") (pintype "passive"))
      (node (ref "R311") (pin "2") (pinfunction "2_2") (pintype "passive"))
    )
    (net (code "15") (name "04CLK_PS") (class "Default")
      (node (ref "J2") (pin "4") (pinfunction "4_4") (pintype "bidirectional"))
      (node (ref "R218") (pin "2") (pinfunction "2_2") (pintype "passive"))
      (node (ref "R219") (pin "2") (pinfunction "2_2") (pintype "passive"))
      (node (ref "R220") (pin "2") (pinfunction "2_2") (pintype "passive"))
      (node (ref "R221") (pin "2") (pinfunction "2_2") (pintype "passive"))
      (node (ref "R222") (pin "2") (pinfunction "2_2") (pintype "passive"))
      (node (ref "R223") (pin "2") (pinfunction "2_2") (pintype "passive"))
    )
    (net (code "16") (name "04CLK_SUM") (class "Default")
      (node (ref "C51") (pin "+") (pinfunction "1_+") (pintype "passive"))
      (node (ref "IC12") (pin "2") (pinfunction "-IN_2") (pintype "input"))
      (node (ref "J4") (pin "8") (pinfunction "8_8") (pintype "bidirectional"))
      (node (ref "R344") (pin "1") (pinfunction "1_1") (pintype "passive"))
    )
    (net (code "17") (name "05CLK") (class "Default")
      (node (ref "J5") (pin "9") (pinfunction "9_9") (pintype "bidirectional"))
      (node (ref "R351") (pin "2") (pinfunction "2_2") (pintype "passive"))
    )
    (net (code "18") (name "05CLK_NRM") (class "Default")
      (node (ref "J3") (pin "5") (pinfunction "5_5") (pintype "bidirectional"))
      (node (ref "R300") (pin "2") (pinfunction "2_2") (pintype "passive"))
      (node (ref "R312") (pin "2") (pinfunction "2_2") (pintype "passive"))
      (node (ref "R313") (pin "2") (pinfunction "2_2") (pintype "passive"))
    )
    (net (code "19") (name "05CLK_PS") (class "Default")
      (node (ref "J2") (pin "5") (pinfunction "5_5") (pintype "bidirectional"))
      (node (ref "R224") (pin "2") (pinfunction "2_2") (pintype "passive"))
      (node (ref "R225") (pin "2") (pinfunction "2_2") (pintype "passive"))
      (node (ref "R226") (pin "2") (pinfunction "2_2") (pintype "passive"))
      (node (ref "R227") (pin "2") (pinfunction "2_2") (pintype "passive"))
      (node (ref "R228") (pin "2") (pinfunction "2_2") (pintype "passive"))
      (node (ref "R229") (pin "2") (pinfunction "2_2") (pintype "passive"))
    )
    (net (code "20") (name "05CLK_SUM") (class "Default")
      (node (ref "C52") (pin "+") (pinfunction "1_+") (pintype "passive"))
      (node (ref "IC12") (pin "9") (pinfunction "-IN_9") (pintype "input"))
      (node (ref "J4") (pin "9") (pinfunction "9_9") (pintype "bidirectional"))
      (node (ref "R345") (pin "1") (pinfunction "1_1") (pintype "passive"))
    )
    (net (code "21") (name "06CLK") (class "Default")
      (node (ref "J5") (pin "11") (pinfunction "11_11") (pintype "bidirectional"))
      (node (ref "R352") (pin "2") (pinfunction "2_2") (pintype "passive"))
    )
    (net (code "22") (name "06CLK_NRM") (class "Default")
      (node (ref "J3") (pin "6") (pinfunction "6_6") (pintype "bidirectional"))
      (node (ref "R303") (pin "2") (pinfunction "2_2") (pintype "passive"))
      (node (ref "R314") (pin "2") (pinfunction "2_2") (pintype "passive"))
    )
    (net (code "23") (name "06CLK_PS") (class "Default")
      (node (ref "J2") (pin "6") (pinfunction "6_6") (pintype "bidirectional"))
      (node (ref "R203") (pin "2") (pinfunction "2_2") (pintype "passive"))
      (node (ref "R230") (pin "2") (pinfunction "2_2") (pintype "passive"))
    )
    (net (code "24") (name "06CLK_SUM") (class "Default")
      (node (ref "C53") (pin "+") (pinfunction "1_+") (pintype "passive"))
      (node (ref "IC13") (pin "2") (pinfunction "-IN_2") (pintype "input"))
      (node (ref "J4") (pin "10") (pinfunction "10_10") (pintype "bidirectional"))
      (node (ref "R346") (pin "1") (pinfunction "1_1") (pintype "passive"))
    )
    (net (code "25") (name "07CLK") (class "Default")
      (node (ref "R359") (pin "2") (pinfunction "2_2") (pintype "passive"))
    )
    (net (code "26") (name "07CLK_NRM") (class "Default")
      (node (ref "J3") (pin "7") (pinfunction "7_7") (pintype "bidirectional"))
      (node (ref "R315") (pin "2") (pinfunction "2_2") (pintype "passive"))
      (node (ref "R331") (pin "2") (pinfunction "2_2") (pintype "passive"))
      (node (ref "R332") (pin "2") (pinfunction "2_2") (pintype "passive"))
    )
    (net (code "27") (name "07CLK_PS") (class "Default")
      (node (ref "J2") (pin "7") (pinfunction "7_7") (pintype "bidirectional"))
      (node (ref "R259") (pin "2") (pinfunction "2_2") (pintype "passive"))
      (node (ref "R260") (pin "2") (pinfunction "2_2") (pintype "passive"))
      (node (ref "R261") (pin "2") (pinfunction "2_2") (pintype "passive"))
      (node (ref "R262") (pin "2") (pinfunction "2_2") (pintype "passive"))
      (node (ref "R263") (pin "2") (pinfunction "2_2") (pintype "passive"))
      (node (ref "R264") (pin "2") (pinfunction "2_2") (pintype "passive"))
    )
    (net (code "28") (name "07CLK_SUM") (class "Default")
      (node (ref "C54") (pin "+") (pinfunction "1_+") (pintype "passive"))
      (node (ref "IC10") (pin "13") (pinfunction "-IN_13") (pintype "input"))
      (node (ref "J4") (pin "11") (pinfunction "11_11") (pintype "bidirectional"))
      (node (ref "R353") (pin "1") (pinfunction "1_1") (pintype "passive"))
    )
    (net (code "29") (name "08CLK") (class "Default")
      (node (ref "R360") (pin "2") (pinfunction "2_2") (pintype "passive"))
    )
    (net (code "30") (name "08CLK_NRM") (class "Default")
      (node (ref "J3") (pin "8") (pinfunction "8_8") (pintype "bidirectional"))
      (node (ref "R318") (pin "2") (pinfunction "2_2") (pintype "passive"))
      (node (ref "R333") (pin "2") (pinfunction "2_2") (pintype "passive"))
      (node (ref "R334") (pin "2") (pinfunction "2_2") (pintype "passive"))
    )
    (net (code "31") (name "08CLK_PS") (class "Default")
      (node (ref "J2") (pin "8") (pinfunction "8_8") (pintype "bidirectional"))
      (node (ref "R265") (pin "2") (pinfunction "2_2") (pintype "passive"))
      (node (ref "R266") (pin "2") (pinfunction "2_2") (pintype "passive"))
      (node (ref "R267") (pin "2") (pinfunction "2_2") (pintype "passive"))
      (node (ref "R268") (pin "2") (pinfunction "2_2") (pintype "passive"))
      (node (ref "R269") (pin "2") (pinfunction "2_2") (pintype "passive"))
      (node (ref "R270") (pin "2") (pinfunction "2_2") (pintype "passive"))
    )
    (net (code "32") (name "08CLK_SUM") (class "Default")
      (node (ref "C55") (pin "+") (pinfunction "1_+") (pintype "passive"))
      (node (ref "IC11") (pin "6") (pinfunction "-IN_6") (pintype "input"))
      (node (ref "J4") (pin "12") (pinfunction "12_12") (pintype "bidirectional"))
      (node (ref "R354") (pin "1") (pinfunction "1_1") (pintype "passive"))
    )
    (net (code "33") (name "09CLK") (class "Default")
      (node (ref "J5") (pin "13") (pinfunction "13_13") (pintype "bidirectional"))
      (node (ref "R361") (pin "2") (pinfunction "2_2") (pintype "passive"))
    )
    (net (code "34") (name "09CLK_NRM") (class "Default")
      (node (ref "J3") (pin "9") (pinfunction "9_9") (pintype "bidirectional"))
      (node (ref "R321") (pin "2") (pinfunction "2_2") (pintype "passive"))
      (node (ref "R335") (pin "2") (pinfunction "2_2") (pintype "passive"))
    )
    (net (code "35") (name "09CLK_PS") (class "Default")
      (node (ref "J2") (pin "9") (pinfunction "9_9") (pintype "bidirectional"))
      (node (ref "R243") (pin "2") (pinfunction "2_2") (pintype "passive"))
      (node (ref "R271") (pin "2") (pinfunction "2_2") (pintype "passive"))
    )
    (net (code "36") (name "09CLK_SUM") (class "Default")
      (node (ref "C56") (pin "+") (pinfunction "1_+") (pintype "passive"))
      (node (ref "IC11") (pin "13") (pinfunction "-IN_13") (pintype "input"))
      (node (ref "J4") (pin "13") (pinfunction "13_13") (pintype "bidirectional"))
      (node (ref "R355") (pin "1") (pinfunction "1_1") (pintype "passive"))
    )
    (net (code "37") (name "10CLK") (class "Default")
      (node (ref "J5") (pin "15") (pinfunction "15_15") (pintype "bidirectional"))
      (node (ref "R362") (pin "2") (pinfunction "2_2") (pintype "passive"))
    )
    (net (code "38") (name "10CLK_NRM") (class "Default")
      (node (ref "J3") (pin "10") (pinfunction "10_10") (pintype "bidirectional"))
      (node (ref "R323") (pin "2") (pinfunction "2_2") (pintype "passive"))
      (node (ref "R336") (pin "2") (pinfunction "2_2") (pintype "passive"))
      (node (ref "R337") (pin "2") (pinfunction "2_2") (pintype "passive"))
    )
    (net (code "39") (name "10CLK_PS") (class "Default")
      (node (ref "J2") (pin "10") (pinfunction "10_10") (pintype "bidirectional"))
      (node (ref "R272") (pin "2") (pinfunction "2_2") (pintype "passive"))
      (node (ref "R273") (pin "2") (pinfunction "2_2") (pintype "passive"))
      (node (ref "R274") (pin "2") (pinfunction "2_2") (pintype "passive"))
      (node (ref "R275") (pin "2") (pinfunction "2_2") (pintype "passive"))
      (node (ref "R276") (pin "2") (pinfunction "2_2") (pintype "passive"))
      (node (ref "R277") (pin "2") (pinfunction "2_2") (pintype "passive"))
    )
    (net (code "40") (name "10CLK_SUM") (class "Default")
      (node (ref "C57") (pin "+") (pinfunction "1_+") (pintype "passive"))
      (node (ref "IC12") (pin "6") (pinfunction "-IN_6") (pintype "input"))
      (node (ref "J4") (pin "14") (pinfunction "14_14") (pintype "bidirectional"))
      (node (ref "R356") (pin "1") (pinfunction "1_1") (pintype "passive"))
    )
    (net (code "41") (name "11CLK") (class "Default")
      (node (ref "J4") (pin "1") (pinfunction "1_1") (pintype "bidirectional"))
      (node (ref "R363") (pin "2") (pinfunction "2_2") (pintype "passive"))
    )
    (net (code "42") (name "11CLK_NRM") (class "Default")
      (node (ref "J3") (pin "11") (pinfunction "11_11") (pintype "bidirectional"))
      (node (ref "R326") (pin "2") (pinfunction "2_2") (pintype "passive"))
      (node (ref "R338") (pin "2") (pinfunction "2_2") (pintype "passive"))
      (node (ref "R339") (pin "2") (pinfunction "2_2") (pintype "passive"))
    )
    (net (code "43") (name "11CLK_PS") (class "Default")
      (node (ref "J2") (pin "11") (pinfunction "11_11") (pintype "bidirectional"))
      (node (ref "R278") (pin "2") (pinfunction "2_2") (pintype "passive"))
      (node (ref "R279") (pin "2") (pinfunction "2_2") (pintype "passive"))
      (node (ref "R280") (pin "2") (pinfunction "2_2") (pintype "passive"))
      (node (ref "R281") (pin "2") (pinfunction "2_2") (pintype "passive"))
      (node (ref "R282") (pin "2") (pinfunction "2_2") (pintype "passive"))
      (node (ref "R283") (pin "2") (pinfunction "2_2") (pintype "passive"))
    )
    (net (code "44") (name "11CLK_SUM") (class "Default")
      (node (ref "C58") (pin "+") (pinfunction "1_+") (pintype "passive"))
      (node (ref "IC12") (pin "13") (pinfunction "-IN_13") (pintype "input"))
      (node (ref "J4") (pin "15") (pinfunction "15_15") (pintype "bidirectional"))
      (node (ref "R357") (pin "1") (pinfunction "1_1") (pintype "passive"))
    )
    (net (code "45") (name "12CLK") (class "Default")
      (node (ref "J4") (pin "3") (pinfunction "3_3") (pintype "bidirectional"))
      (node (ref "R364") (pin "2") (pinfunction "2_2") (pintype "passive"))
    )
    (net (code "46") (name "12CLK_NRM") (class "Default")
      (node (ref "J3") (pin "12") (pinfunction "12_12") (pintype "bidirectional"))
      (node (ref "R329") (pin "2") (pinfunction "2_2") (pintype "passive"))
      (node (ref "R340") (pin "2") (pinfunction "2_2") (pintype "passive"))
    )
    (net (code "47") (name "12CLK_PS") (class "Default")
      (node (ref "J2") (pin "12") (pinfunction "12_12") (pintype "bidirectional"))
      (node (ref "R257") (pin "2") (pinfunction "2_2") (pintype "passive"))
      (node (ref "R284") (pin "2") (pinfunction "2_2") (pintype "passive"))
    )
    (net (code "48") (name "12CLK_SUM") (class "Default")
      (node (ref "C59") (pin "+") (pinfunction "1_+") (pintype "passive"))
      (node (ref "IC13") (pin "6") (pinfunction "-IN_6") (pintype "input"))
      (node (ref "J4") (pin "16") (pinfunction "16_16") (pintype "bidirectional"))
      (node (ref "R358") (pin "1") (pinfunction "1_1") (pintype "passive"))
    )
    (net (code "49") (name "DELTA") (class "Default")
      (node (ref "IC3") (pin "8") (pinfunction "OUT_8") (pintype "output"))
      (node (ref "R62") (pin "2") (pinfunction "2_2") (pintype "passive"))
      (node (ref "R67") (pin "1") (pinfunction "1_1") (pintype "passive"))
    )
    (net (code "50") (name "GND") (class "Default")
      (node (ref "C10") (pin "+") (pinfunction "1_+") (pintype "passive"))
      (node (ref "C15") (pin "+") (pinfunction "1_+") (pintype "passive"))
      (node (ref "C16") (pin "+") (pinfunction "1_+") (pintype "passive"))
      (node (ref "C17") (pin "+") (pinfunction "1_+") (pintype "passive"))
      (node (ref "C18") (pin "+") (pinfunction "1_+") (pintype "passive"))
      (node (ref "C28") (pin "-") (pinfunction "2_-") (pintype "passive"))
      (node (ref "C29") (pin "-") (pinfunction "2_-") (pintype "passive"))
      (node (ref "C30") (pin "-") (pinfunction "2_-") (pintype "passive"))
      (node (ref "C31") (pin "-") (pinfunction "2_-") (pintype "passive"))
      (node (ref "C32") (pin "-") (pinfunction "2_-") (pintype "passive"))
      (node (ref "C33") (pin "-") (pinfunction "2_-") (pintype "passive"))
      (node (ref "C40") (pin "-") (pinfunction "2_-") (pintype "passive"))
      (node (ref "C41") (pin "-") (pinfunction "2_-") (pintype "passive"))
      (node (ref "C42") (pin "-") (pinfunction "2_-") (pintype "passive"))
      (node (ref "C43") (pin "-") (pinfunction "2_-") (pintype "passive"))
      (node (ref "C44") (pin "-") (pinfunction "2_-") (pintype "passive"))
      (node (ref "C45") (pin "-") (pinfunction "2_-") (pintype "passive"))
      (node (ref "C7") (pin "+") (pinfunction "1_+") (pintype "passive"))
      (node (ref "C8") (pin "+") (pinfunction "1_+") (pintype "passive"))
      (node (ref "C9") (pin "+") (pinfunction "1_+") (pintype "passive"))
      (node (ref "IC1") (pin "3") (pinfunction "+IN_3") (pintype "input"))
      (node (ref "IC10") (pin "10") (pinfunction "+IN_10") (pintype "input"))
      (node (ref "IC10") (pin "12") (pinfunction "+IN_12") (pintype "input"))
      (node (ref "IC10") (pin "3") (pinfunction "+IN_3") (pintype "input"))
      (node (ref "IC10") (pin "5") (pinfunction "+IN_5") (pintype "input"))
      (node (ref "IC11") (pin "10") (pinfunction "+IN_10") (pintype "input"))
      (node (ref "IC11") (pin "12") (pinfunction "+IN_12") (pintype "input"))
      (node (ref "IC11") (pin "3") (pinfunction "+IN_3") (pintype "input"))
      (node (ref "IC11") (pin "5") (pinfunction "+IN_5") (pintype "input"))
      (node (ref "IC12") (pin "10") (pinfunction "+IN_10") (pintype "input"))
      (node (ref "IC12") (pin "12") (pinfunction "+IN_12") (pintype "input"))
      (node (ref "IC12") (pin "3") (pinfunction "+IN_3") (pintype "input"))
      (node (ref "IC12") (pin "5") (pinfunction "+IN_5") (pintype "input"))
      (node (ref "IC13") (pin "3") (pinfunction "+IN_3") (pintype "input"))
      (node (ref "IC13") (pin "5") (pinfunction "+IN_5") (pintype "input"))
      (node (ref "IC4") (pin "10") (pinfunction "+IN_10") (pintype "input"))
      (node (ref "IC4") (pin "12") (pinfunction "+IN_12") (pintype "input"))
      (node (ref "IC8") (pin "3") (pinfunction "+IN_3") (pintype "input"))
      (node (ref "IC8") (pin "5") (pinfunction "+IN_5") (pintype "input"))
      (node (ref "IC9") (pin "10") (pinfunction "+IN_10") (pintype "input"))
      (node (ref "IC9") (pin "12") (pinfunction "+IN_12") (pintype "input"))
      (node (ref "IC9") (pin "3") (pinfunction "+IN_3") (pintype "input"))
      (node (ref "IC9") (pin "5") (pinfunction "+IN_5") (pintype "input"))
      (node (ref "J1") (pin "2") (pinfunction "2_2") (pintype "bidirectional"))
      (node (ref "J1") (pin "4") (pinfunction "4_4") (pintype "bidirectional"))
      (node (ref "J1") (pin "8") (pinfunction "8_8") (pintype "bidirectional"))
      (node (ref "J1") (pin "9") (pinfunction "9_9") (pintype "bidirectional"))
      (node (ref "J4") (pin "2") (pinfunction "2_2") (pintype "bidirectional"))
      (node (ref "J4") (pin "4") (pinfunction "4_4") (pintype "bidirectional"))
      (node (ref "J5") (pin "10") (pinfunction "10_10") (pintype "bidirectional"))
      (node (ref "J5") (pin "12") (pinfunction "12_12") (pintype "bidirectional"))
      (node (ref "J5") (pin "14") (pinfunction "14_14") (pintype "bidirectional"))
      (node (ref "J5") (pin "16") (pinfunction "16_16") (pintype "bidirectional"))
      (node (ref "J5") (pin "2") (pinfunction "2_2") (pintype "bidirectional"))
      (node (ref "J5") (pin "4") (pinfunction "4_4") (pintype "bidirectional"))
      (node (ref "J5") (pin "6") (pinfunction "6_6") (pintype "bidirectional"))
      (node (ref "J5") (pin "8") (pinfunction "8_8") (pintype "bidirectional"))
      (node (ref "R5") (pin "1") (pinfunction "1_1") (pintype "passive"))
      (node (ref "R69") (pin "1") (pinfunction "1_1") (pintype "passive"))
    )
    (net (code "51") (name "J_DELTA") (class "Default")
      (node (ref "IC3") (pin "14") (pinfunction "OUT_14") (pintype "output"))
      (node (ref "R63") (pin "2") (pinfunction "2_2") (pintype "passive"))
      (node (ref "R64") (pin "1") (pinfunction "1_1") (pintype "passive"))
      (node (ref "R65") (pin "1") (pinfunction "1_1") (pintype "passive"))
    )
    (net (code "52") (name "J_SIGMA") (class "Default")
      (node (ref "IC2") (pin "8") (pinfunction "OUT_8") (pintype "output"))
      (node (ref "R61") (pin "2") (pinfunction "2_2") (pintype "passive"))
      (node (ref "R68") (pin "1") (pinfunction "1_1") (pintype "passive"))
    )
    (net (code "53") (name "N$27") (class "Default")
      (node (ref "J1") (pin "5") (pinfunction "5_5") (pintype "bidirectional"))
    )
    (net (code "54") (name "N$28") (class "Default")
      (node (ref "J1") (pin "6") (pinfunction "6_6") (pintype "bidirectional"))
    )
    (net (code "55") (name "N$29") (class "Default")
      (node (ref "J1") (pin "7") (pinfunction "7_7") (pintype "bidirectional"))
    )
    (net (code "56") (name "N$196") (class "Default")
      (node (ref "J1") (pin "1") (pinfunction "1_1") (pintype "bidirectional"))
      (node (ref "R1") (pin "1") (pinfunction "1_1") (pintype "passive"))
      (node (ref "R4") (pin "1") (pinfunction "1_1") (pintype "passive"))
    )
    (net (code "57") (name "N$198") (class "Default")
      (node (ref "J1") (pin "3") (pinfunction "3_3") (pintype "bidirectional"))
      (node (ref "R2") (pin "1") (pinfunction "1_1") (pintype "passive"))
      (node (ref "R3") (pin "1") (pinfunction "1_1") (pintype "passive"))
    )
    (net (code "58") (name "Net-(C1-1)") (class "Default")
      (node (ref "C1") (pin "+") (pinfunction "1_+") (pintype "passive"))
      (node (ref "IC1") (pin "2") (pinfunction "-IN_2") (pintype "input"))
      (node (ref "R1") (pin "2") (pinfunction "2_2") (pintype "passive"))
      (node (ref "R2") (pin "2") (pinfunction "2_2") (pintype "passive"))
      (node (ref "R6") (pin "1") (pinfunction "1_1") (pintype "passive"))
    )
    (net (code "59") (name "Net-(C1-2)") (class "Default")
      (node (ref "C1") (pin "-") (pinfunction "2_-") (pintype "passive"))
      (node (ref "C3") (pin "+") (pinfunction "1_+") (pintype "passive"))
      (node (ref "C6") (pin "+") (pinfunction "1_+") (pintype "passive"))
      (node (ref "IC1") (pin "1") (pinfunction "OUT_1") (pintype "output"))
      (node (ref "R24") (pin "1") (pinfunction "1_1") (pintype "passive"))
      (node (ref "R26") (pin "1") (pinfunction "1_1") (pintype "passive"))
      (node (ref "R6") (pin "2") (pinfunction "2_2") (pintype "passive"))
      (node (ref "R8") (pin "1") (pinfunction "1_1") (pintype "passive"))
      (node (ref "R9") (pin "1") (pinfunction "1_1") (pintype "passive"))
    )
    (net (code "60") (name "Net-(C2-1)") (class "Default")
      (node (ref "C2") (pin "+") (pinfunction "1_+") (pintype "passive"))
      (node (ref "IC1") (pin "6") (pinfunction "-IN_6") (pintype "input"))
      (node (ref "R4") (pin "2") (pinfunction "2_2") (pintype "passive"))
      (node (ref "R7") (pin "1") (pinfunction "1_1") (pintype "passive"))
    )
    (net (code "61") (name "Net-(C2-2)") (class "Default")
      (node (ref "C2") (pin "-") (pinfunction "2_-") (pintype "passive"))
      (node (ref "C4") (pin "+") (pinfunction "1_+") (pintype "passive"))
      (node (ref "C5") (pin "+") (pinfunction "1_+") (pintype "passive"))
      (node (ref "IC1") (pin "7") (pinfunction "OUT_7") (pintype "output"))
      (node (ref "R10") (pin "1") (pinfunction "1_1") (pintype "passive"))
      (node (ref "R11") (pin "1") (pinfunction "1_1") (pintype "passive"))
      (node (ref "R25") (pin "1") (pinfunction "1_1") (pintype "passive"))
      (node (ref "R27") (pin "1") (pinfunction "1_1") (pintype "passive"))
      (node (ref "R7") (pin "2") (pinfunction "2_2") (pintype "passive"))
    )
    (net (code "62") (name "Net-(C3-2)") (class "Default")
      (node (ref "C3") (pin "-") (pinfunction "2_-") (pintype "passive"))
      (node (ref "IC2") (pin "5") (pinfunction "+IN_5") (pintype "input"))
      (node (ref "R13") (pin "2") (pinfunction "2_2") (pintype "passive"))
      (node (ref "R18") (pin "2") (pinfunction "2_2") (pintype "passive"))
    )
    (net (code "63") (name "Net-(C4-2)") (class "Default")
      (node (ref "C4") (pin "-") (pinfunction "2_-") (pintype "passive"))
      (node (ref "IC3") (pin "5") (pinfunction "+IN_5") (pintype "input"))
      (node (ref "R14") (pin "2") (pinfunction "2_2") (pintype "passive"))
      (node (ref "R20") (pin "2") (pinfunction "2_2") (pintype "passive"))
    )
    (net (code "64") (name "Net-(C5-2)") (class "Default")
      (node (ref "C5") (pin "-") (pinfunction "2_-") (pintype "passive"))
      (node (ref "IC3") (pin "3") (pinfunction "+IN_3") (pintype "input"))
      (node (ref "R15") (pin "2") (pinfunction "2_2") (pintype "passive"))
      (node (ref "R22") (pin "2") (pinfunction "2_2") (pintype "passive"))
    )
    (net (code "65") (name "Net-(C6-2)") (class "Default")
      (node (ref "C6") (pin "-") (pinfunction "2_-") (pintype "passive"))
      (node (ref "IC2") (pin "3") (pinfunction "+IN_3") (pintype "input"))
      (node (ref "R12") (pin "2") (pinfunction "2_2") (pintype "passive"))
      (node (ref "R16") (pin "2") (pinfunction "2_2") (pintype "passive"))
    )
    (net (code "66") (name "Net-(C7-2)") (class "Default")
      (node (ref "C7") (pin "-") (pinfunction "2_-") (pintype "passive"))
      (node (ref "R17") (pin "2") (pinfunction "2_2") (pintype "passive"))
    )
    (net (code "67") (name "Net-(C8-2)") (class "Default")
      (node (ref "C8") (pin "-") (pinfunction "2_-") (pintype "passive"))
      (node (ref "R19") (pin "2") (pinfunction "2_2") (pintype "passive"))
    )
    (net (code "68") (name "Net-(C9-2)") (class "Default")
      (node (ref "C9") (pin "-") (pinfunction "2_-") (pintype "passive"))
      (node (ref "R21") (pin "2") (pinfunction "2_2") (pintype "passive"))
    )
    (net (code "69") (name "Net-(C10-2)") (class "Default")
      (node (ref "C10") (pin "-") (pinfunction "2_-") (pintype "passive"))
      (node (ref "R23") (pin "2") (pinfunction "2_2") (pintype "passive"))
    )
    (net (code "70") (name "Net-(C11-1)") (class "Default")
      (node (ref "C11") (pin "+") (pinfunction "1_+") (pintype "passive"))
      (node (ref "IC2") (pin "1") (pinfunction "OUT_1") (pintype "output"))
      (node (ref "R32") (pin "2") (pinfunction "2_2") (pintype "passive"))
      (node (ref "R36") (pin "1") (pinfunction "1_1") (pintype "passive"))
      (node (ref "R52") (pin "1") (pinfunction "1_1") (pintype "passive"))
    )
    (net (code "71") (name "Net-(C11-2)") (class "Default")
      (node (ref "C11") (pin "-") (pinfunction "2_-") (pintype "passive"))
      (node (ref "IC2") (pin "12") (pinfunction "+IN_12") (pintype "input"))
      (node (ref "R40") (pin "2") (pinfunction "2_2") (pintype "passive"))
      (node (ref "R44") (pin "2") (pinfunction "2_2") (pintype "passive"))
    )
    (net (code "72") (name "Net-(C12-1)") (class "Default")
      (node (ref "C12") (pin "+") (pinfunction "1_+") (pintype "passive"))
      (node (ref "IC2") (pin "7") (pinfunction "OUT_7") (pintype "output"))
      (node (ref "R33") (pin "2") (pinfunction "2_2") (pintype "passive"))
      (node (ref "R37") (pin "1") (pinfunction "1_1") (pintype "passive"))
      (node (ref "R53") (pin "1") (pinfunction "1_1") (pintype "passive"))
    )
    (net (code "73") (name "Net-(C12-2)") (class "Default")
      (node (ref "C12") (pin "-") (pinfunction "2_-") (pintype "passive"))
      (node (ref "IC2") (pin "10") (pinfunction "+IN_10") (pintype "input"))
      (node (ref "R41") (pin "2") (pinfunction "2_2") (pintype "passive"))
      (node (ref "R46") (pin "2") (pinfunction "2_2") (pintype "passive"))
    )
    (net (code "74") (name "Net-(C13-1)") (class "Default")
      (node (ref "C13") (pin "+") (pinfunction "1_+") (pintype "passive"))
      (node (ref "IC3") (pin "7") (pinfunction "OUT_7") (pintype "output"))
      (node (ref "R34") (pin "2") (pinfunction "2_2") (pintype "passive"))
      (node (ref "R38") (pin "1") (pinfunction "1_1") (pintype "passive"))
      (node (ref "R54") (pin "1") (pinfunction "1_1") (pintype "passive"))
    )
    (net (code "75") (name "Net-(C13-2)") (class "Default")
      (node (ref "C13") (pin "-") (pinfunction "2_-") (pintype "passive"))
      (node (ref "IC3") (pin "10") (pinfunction "+IN_10") (pintype "input"))
      (node (ref "R42") (pin "2") (pinfunction "2_2") (pintype "passive"))
      (node (ref "R48") (pin "2") (pinfunction "2_2") (pintype "passive"))
    )
    (net (code "76") (name "Net-(C14-1)") (class "Default")
      (node (ref "C14") (pin "+") (pinfunction "1_+") (pintype "passive"))
      (node (ref "IC3") (pin "1") (pinfunction "OUT_1") (pintype "output"))
      (node (ref "R35") (pin "2") (pinfunction "2_2") (pintype "passive"))
      (node (ref "R39") (pin "1") (pinfunction "1_1") (pintype "passive"))
      (node (ref "R55") (pin "1") (pinfunction "1_1") (pintype "passive"))
    )
    (net (code "77") (name "Net-(C14-2)") (class "Default")
      (node (ref "C14") (pin "-") (pinfunction "2_-") (pintype "passive"))
      (node (ref "IC3") (pin "12") (pinfunction "+IN_12") (pintype "input"))
      (node (ref "R43") (pin "2") (pinfunction "2_2") (pintype "passive"))
      (node (ref "R50") (pin "2") (pinfunction "2_2") (pintype "passive"))
    )
    (net (code "78") (name "Net-(C15-2)") (class "Default")
      (node (ref "C15") (pin "-") (pinfunction "2_-") (pintype "passive"))
      (node (ref "R45") (pin "2") (pinfunction "2_2") (pintype "passive"))
    )
    (net (code "79") (name "Net-(C16-2)") (class "Default")
      (node (ref "C16") (pin "-") (pinfunction "2_-") (pintype "passive"))
      (node (ref "R47") (pin "2") (pinfunction "2_2") (pintype "passive"))
    )
    (net (code "80") (name "Net-(C17-2)") (class "Default")
      (node (ref "C17") (pin "-") (pinfunction "2_-") (pintype "passive"))
      (node (ref "R49") (pin "2") (pinfunction "2_2") (pintype "passive"))
    )
    (net (code "81") (name "Net-(C18-2)") (class "Default")
      (node (ref "C18") (pin "-") (pinfunction "2_-") (pintype "passive"))
      (node (ref "R51") (pin "2") (pinfunction "2_2") (pintype "passive"))
    )
    (net (code "82") (name "Net-(C19-1)") (class "Default")
      (node (ref "C19") (pin "+") (pinfunction "1_+") (pintype "passive"))
      (node (ref "IC4") (pin "2") (pinfunction "-IN_2") (pintype "input"))
      (node (ref "R66") (pin "2") (pinfunction "2_2") (pintype "passive"))
      (node (ref "R74") (pin "1") (pinfunction "1_1") (pintype "passive"))
    )
    (net (code "83") (name "Net-(C19-2)") (class "Default")
      (node (ref "C19") (pin "-") (pinfunction "2_-") (pintype "passive"))
      (node (ref "IC4") (pin "1") (pinfunction "OUT_1") (pintype "output"))
      (node (ref "R74") (pin "2") (pinfunction "2_2") (pintype "passive"))
      (node (ref "R77") (pin "1") (pinfunction "1_1") (pintype "passive"))
    )
    (net (code "84") (name "Net-(C20-1)") (class "Default")
      (node (ref "C20") (pin "+") (pinfunction "1_+") (pintype "passive"))
      (node (ref "IC4") (pin "9") (pinfunction "-IN_9") (pintype "input"))
      (node (ref "R72") (pin "2") (pinfunction "2_2") (pintype "passive"))
      (node (ref "R73") (pin "2") (pinfunction "2_2") (pintype "passive"))
      (node (ref "R76") (pin "1") (pinfunction "1_1") (pintype "passive"))
    )
    (net (code "85") (name "Net-(C20-2)") (class "Default")
      (node (ref "C20") (pin "-") (pinfunction "2_-") (pintype "passive"))
      (node (ref "IC4") (pin "8") (pinfunction "OUT_8") (pintype "output"))
      (node (ref "R76") (pin "2") (pinfunction "2_2") (pintype "passive"))
      (node (ref "R79") (pin "1") (pinfunction "1_1") (pintype "passive"))
    )
    (net (code "86") (name "Net-(C21-1)") (class "Default")
      (node (ref "C21") (pin "+") (pinfunction "1_+") (pintype "passive"))
      (node (ref "IC4") (pin "13") (pinfunction "-IN_13") (pintype "input"))
      (node (ref "R70") (pin "2") (pinfunction "2_2") (pintype "passive"))
      (node (ref "R71") (pin "2") (pinfunction "2_2") (pintype "passive"))
      (node (ref "R75") (pin "1") (pinfunction "1_1") (pintype "passive"))
    )
    (net (code "87") (name "Net-(C21-2)") (class "Default")
      (node (ref "C21") (pin "-") (pinfunction "2_-") (pintype "passive"))
      (node (ref "IC4") (pin "14") (pinfunction "OUT_14") (pintype "output"))
      (node (ref "R78") (pin "2") (pinfunction "2_2") (pintype "passive"))
      (node (ref "R80") (pin "1") (pinfunction "1_1") (pintype "passive"))
    )
    (net (code "88") (name "Net-(C22-2)") (class "Default")
      (node (ref "C22") (pin "-") (pinfunction "2_-") (pintype "passive"))
      (node (ref "IC5") (pin "5") (pinfunction "+IN_5") (pintype "input"))
      (node (ref "R88") (pin "2") (pinfunction "2_2") (pintype "passive"))
      (node (ref "R95") (pin "2") (pinfunction "2_2") (pintype "passive"))
    )
    (net (code "89") (name "Net-(C23-2)") (class "Default")
      (node (ref "C23") (pin "-") (pinfunction "2_-") (pintype "passive"))
      (node (ref "IC6") (pin "5") (pinfunction "+IN_5") (pintype "input"))
      (node (ref "R90") (pin "2") (pinfunction "2_2") (pintype "passive"))
      (node (ref "R99") (pin "2") (pinfunction "2_2") (pintype "passive"))
    )
    (net (code "90") (name "Net-(C24-2)") (class "Default")
      (node (ref "C24") (pin "-") (pinfunction "2_-") (pintype "passive"))
      (node (ref "IC5") (pin "3") (pinfunction "+IN_3") (pintype "input"))
      (node (ref "R87") (pin "2") (pinfunction "2_2") (pintype "passive"))
      (node (ref "R93") (pin "2") (pinfunction "2_2") (pintype "passive"))
    )
    (net (code "91") (name "Net-(C25-2)") (class "Default")
      (node (ref "C25") (pin "-") (pinfunction "2_-") (pintype "passive"))
      (node (ref "IC6") (pin "3") (pinfunction "+IN_3") (pintype "input"))
      (node (ref "R89") (pin "2") (pinfunction "2_2") (pintype "passive"))
      (node (ref "R97") (pin "2") (pinfunction "2_2") (pintype "passive"))
    )
    (net (code "92") (name "Net-(C26-2)") (class "Default")
      (node (ref "C26") (pin "-") (pinfunction "2_-") (pintype "passive"))
      (node (ref "IC7") (pin "3") (pinfunction "+IN_3") (pintype "input"))
      (node (ref "R101") (pin "2") (pinfunction "2_2") (pintype "passive"))
      (node (ref "R91") (pin "2") (pinfunction "2_2") (pintype "passive"))
    )
    (net (code "93") (name "Net-(C27-2)") (class "Default")
      (node (ref "C27") (pin "-") (pinfunction "2_-") (pintype "passive"))
      (node (ref "IC7") (pin "5") (pinfunction "+IN_5") (pintype "input"))
      (node (ref "R103") (pin "2") (pinfunction "2_2") (pintype "passive"))
      (node (ref "R92") (pin "2") (pinfunction "2_2") (pintype "passive"))
    )
    (net (code "94") (name "Net-(C28-1)") (class "Default")
      (node (ref "C28") (pin "+") (pinfunction "1_+") (pintype "passive"))
      (node (ref "R94") (pin "2") (pinfunction "2_2") (pintype "passive"))
    )
    (net (code "95") (name "Net-(C29-1)") (class "Default")
      (node (ref "C29") (pin "+") (pinfunction "1_+") (pintype "passive"))
      (node (ref "R96") (pin "2") (pinfunction "2_2") (pintype "passive"))
    )
    (net (code "96") (name "Net-(C30-1)") (class "Default")
      (node (ref "C30") (pin "+") (pinfunction "1_+") (pintype "passive"))
      (node (ref "R98") (pin "2") (pinfunction "2_2") (pintype "passive"))
    )
    (net (code "97") (name "Net-(C31-1)") (class "Default")
      (node (ref "C31") (pin "+") (pinfunction "1_+") (pintype "passive"))
      (node (ref "R100") (pin "2") (pinfunction "2_2") (pintype "passive"))
    )
    (net (code "98") (name "Net-(C32-1)") (class "Default")
      (node (ref "C32") (pin "+") (pinfunction "1_+") (pintype "passive"))
      (node (ref "R102") (pin "2") (pinfunction "2_2") (pintype "passive"))
    )
    (net (code "99") (name "Net-(C33-1)") (class "Default")
      (node (ref "C33") (pin "+") (pinfunction "1_+") (pintype "passive"))
      (node (ref "R104") (pin "2") (pinfunction "2_2") (pintype "passive"))
    )
    (net (code "100") (name "Net-(C34-1)") (class "Default")
      (node (ref "C34") (pin "+") (pinfunction "1_+") (pintype "passive"))
      (node (ref "IC5") (pin "7") (pinfunction "OUT_7") (pintype "output"))
      (node (ref "R118") (pin "2") (pinfunction "2_2") (pintype "passive"))
      (node (ref "R124") (pin "1") (pinfunction "1_1") (pintype "passive"))
      (node (ref "R148") (pin "1") (pinfunction "1_1") (pintype "passive"))
    )
    (net (code "101") (name "Net-(C34-2)") (class "Default")
      (node (ref "C34") (pin "-") (pinfunction "2_-") (pintype "passive"))
      (node (ref "IC5") (pin "10") (pinfunction "+IN_10") (pintype "input"))
      (node (ref "R130") (pin "2") (pinfunction "2_2") (pintype "passive"))
      (node (ref "R137") (pin "2") (pinfunction "2_2") (pintype "passive"))
    )
    (net (code "102") (name "Net-(C35-1)") (class "Default")
      (node (ref "C35") (pin "+") (pinfunction "1_+") (pintype "passive"))
      (node (ref "IC6") (pin "1") (pinfunction "OUT_1") (pintype "output"))
      (node (ref "R119") (pin "2") (pinfunction "2_2") (pintype "passive"))
      (node (ref "R125") (pin "1") (pinfunction "1_1") (pintype "passive"))
      (node (ref "R149") (pin "1") (pinfunction "1_1") (pintype "passive"))
    )
    (net (code "103") (name "Net-(C35-2)") (class "Default")
      (node (ref "C35") (pin "-") (pinfunction "2_-") (pintype "passive"))
      (node (ref "IC6") (pin "12") (pinfunction "+IN_12") (pintype "input"))
      (node (ref "R131") (pin "2") (pinfunction "2_2") (pintype "passive"))
      (node (ref "R139") (pin "2") (pinfunction "2_2") (pintype "passive"))
    )
    (net (code "104") (name "Net-(C36-1)") (class "Default")
      (node (ref "C36") (pin "+") (pinfunction "1_+") (pintype "passive"))
      (node (ref "IC6") (pin "7") (pinfunction "OUT_7") (pintype "output"))
      (node (ref "R120") (pin "2") (pinfunction "2_2") (pintype "passive"))
      (node (ref "R126") (pin "1") (pinfunction "1_1") (pintype "passive"))
      (node (ref "R150") (pin "1") (pinfunction "1_1") (pintype "passive"))
    )
    (net (code "105") (name "Net-(C36-2)") (class "Default")
      (node (ref "C36") (pin "-") (pinfunction "2_-") (pintype "passive"))
      (node (ref "IC6") (pin "10") (pinfunction "+IN_10") (pintype "input"))
      (node (ref "R132") (pin "2") (pinfunction "2_2") (pintype "passive"))
      (node (ref "R141") (pin "2") (pinfunction "2_2") (pintype "passive"))
    )
    (net (code "106") (name "Net-(C37-1)") (class "Default")
      (node (ref "C37") (pin "+") (pinfunction "1_+") (pintype "passive"))
      (node (ref "IC7") (pin "7") (pinfunction "OUT_7") (pintype "output"))
      (node (ref "R122") (pin "2") (pinfunction "2_2") (pintype "passive"))
      (node (ref "R128") (pin "1") (pinfunction "1_1") (pintype "passive"))
      (node (ref "R152") (pin "1") (pinfunction "1_1") (pintype "passive"))
    )
    (net (code "107") (name "Net-(C37-2)") (class "Default")
      (node (ref "C37") (pin "-") (pinfunction "2_-") (pintype "passive"))
      (node (ref "IC7") (pin "10") (pinfunction "+IN_10") (pintype "input"))
      (node (ref "R134") (pin "2") (pinfunction "2_2") (pintype "passive"))
      (node (ref "R145") (pin "2") (pinfunction "2_2") (pintype "passive"))
    )
    (net (code "108") (name "Net-(C38-1)") (class "Default")
      (node (ref "C38") (pin "+") (pinfunction "1_+") (pintype "passive"))
      (node (ref "IC5") (pin "1") (pinfunction "OUT_1") (pintype "output"))
      (node (ref "R117") (pin "2") (pinfunction "2_2") (pintype "passive"))
      (node (ref "R123") (pin "1") (pinfunction "1_1") (pintype "passive"))
      (node (ref "R147") (pin "1") (pinfunction "1_1") (pintype "passive"))
    )
    (net (code "109") (name "Net-(C38-2)") (class "Default")
      (node (ref "C38") (pin "-") (pinfunction "2_-") (pintype "passive"))
      (node (ref "IC5") (pin "12") (pinfunction "+IN_12") (pintype "input"))
      (node (ref "R129") (pin "2") (pinfunction "2_2") (pintype "passive"))
      (node (ref "R135") (pin "2") (pinfunction "2_2") (pintype "passive"))
    )
    (net (code "110") (name "Net-(C39-1)") (class "Default")
      (node (ref "C39") (pin "+") (pinfunction "1_+") (pintype "passive"))
      (node (ref "IC7") (pin "1") (pinfunction "OUT_1") (pintype "output"))
      (node (ref "R121") (pin "2") (pinfunction "2_2") (pintype "passive"))
      (node (ref "R127") (pin "1") (pinfunction "1_1") (pintype "passive"))
      (node (ref "R151") (pin "1") (pinfunction "1_1") (pintype "passive"))
    )
    (net (code "111") (name "Net-(C39-2)") (class "Default")
      (node (ref "C39") (pin "-") (pinfunction "2_-") (pintype "passive"))
      (node (ref "IC7") (pin "12") (pinfunction "+IN_12") (pintype "input"))
      (node (ref "R133") (pin "2") (pinfunction "2_2") (pintype "passive"))
      (node (ref "R143") (pin "2") (pinfunction "2_2") (pintype "passive"))
    )
    (net (code "112") (name "Net-(C40-1)") (class "Default")
      (node (ref "C40") (pin "+") (pinfunction "1_+") (pintype "passive"))
      (node (ref "R136") (pin "2") (pinfunction "2_2") (pintype "passive"))
    )
    (net (code "113") (name "Net-(C41-1)") (class "Default")
      (node (ref "C41") (pin "+") (pinfunction "1_+") (pintype "passive"))
      (node (ref "R138") (pin "2") (pinfunction "2_2") (pintype "passive"))
    )
    (net (code "114") (name "Net-(C42-1)") (class "Default")
      (node (ref "C42") (pin "+") (pinfunction "1_+") (pintype "passive"))
      (node (ref "R140") (pin "2") (pinfunction "2_2") (pintype "passive"))
    )
    (net (code "115") (name "Net-(C43-1)") (class "Default")
      (node (ref "C43") (pin "+") (pinfunction "1_+") (pintype "passive"))
      (node (ref "R142") (pin "2") (pinfunction "2_2") (pintype "passive"))
    )
    (net (code "116") (name "Net-(C44-1)") (class "Default")
      (node (ref "C44") (pin "+") (pinfunction "1_+") (pintype "passive"))
      (node (ref "R144") (pin "2") (pinfunction "2_2") (pintype "passive"))
    )
    (net (code "117") (name "Net-(C45-1)") (class "Default")
      (node (ref "C45") (pin "+") (pinfunction "1_+") (pintype "passive"))
      (node (ref "R146") (pin "2") (pinfunction "2_2") (pintype "passive"))
    )
    (net (code "118") (name "Net-(C46-1)") (class "Default")
      (node (ref "C46") (pin "+") (pinfunction "1_+") (pintype "passive"))
      (node (ref "IC10") (pin "2") (pinfunction "-IN_2") (pintype "input"))
      (node (ref "R285") (pin "2") (pinfunction "2_2") (pintype "passive"))
      (node (ref "R287") (pin "1") (pinfunction "1_1") (pintype "passive"))
    )
    (net (code "119") (name "Net-(C46-2)") (class "Default")
      (node (ref "C46") (pin "-") (pinfunction "2_-") (pintype "passive"))
      (node (ref "IC10") (pin "1") (pinfunction "OUT_1") (pintype "output"))
      (node (ref "R287") (pin "2") (pinfunction "2_2") (pintype "passive"))
      (node (ref "R298") (pin "1") (pinfunction "1_1") (pintype "passive"))
      (node (ref "R301") (pin "1") (pinfunction "1_1") (pintype "passive"))
      (node (ref "R304") (pin "1") (pinfunction "1_1") (pintype "passive"))
      (node (ref "R316") (pin "1") (pinfunction "1_1") (pintype "passive"))
      (node (ref "R319") (pin "1") (pinfunction "1_1") (pintype "passive"))
    )
    (net (code "120") (name "Net-(C47-1)") (class "Default")
      (node (ref "C47") (pin "+") (pinfunction "1_+") (pintype "passive"))
      (node (ref "IC10") (pin "6") (pinfunction "-IN_6") (pintype "input"))
      (node (ref "R286") (pin "2") (pinfunction "2_2") (pintype "passive"))
      (node (ref "R288") (pin "1") (pinfunction "1_1") (pintype "passive"))
    )
    (net (code "121") (name "Net-(C47-2)") (class "Default")
      (node (ref "C47") (pin "-") (pinfunction "2_-") (pintype "passive"))
      (node (ref "IC10") (pin "7") (pinfunction "OUT_7") (pintype "output"))
      (node (ref "R288") (pin "2") (pinfunction "2_2") (pintype "passive"))
      (node (ref "R291") (pin "1") (pinfunction "1_1") (pintype "passive"))
      (node (ref "R294") (pin "1") (pinfunction "1_1") (pintype "passive"))
      (node (ref "R296") (pin "1") (pinfunction "1_1") (pintype "passive"))
      (node (ref "R299") (pin "1") (pinfunction "1_1") (pintype "passive"))
      (node (ref "R302") (pin "1") (pinfunction "1_1") (pintype "passive"))
    )
    (net (code "122") (name "Net-(C48-2)") (class "Default")
      (node (ref "C48") (pin "-") (pinfunction "2_-") (pintype "passive"))
      (node (ref "IC10") (pin "8") (pinfunction "OUT_8") (pintype "output"))
      (node (ref "R341") (pin "2") (pinfunction "2_2") (pintype "passive"))
      (node (ref "R347") (pin "1") (pinfunction "1_1") (pintype "passive"))
    )
    (net (code "123") (name "Net-(C49-2)") (class "Default")
      (node (ref "C49") (pin "-") (pinfunction "2_-") (pintype "passive"))
      (node (ref "IC11") (pin "1") (pinfunction "OUT_1") (pintype "output"))
      (node (ref "R342") (pin "2") (pinfunction "2_2") (pintype "passive"))
      (node (ref "R348") (pin "1") (pinfunction "1_1") (pintype "passive"))
    )
    (net (code "124") (name "Net-(C50-2)") (class "Default")
      (node (ref "C50") (pin "-") (pinfunction "2_-") (pintype "passive"))
      (node (ref "IC11") (pin "8") (pinfunction "OUT_8") (pintype "output"))
      (node (ref "R343") (pin "2") (pinfunction "2_2") (pintype "passive"))
      (node (ref "R349") (pin "1") (pinfunction "1_1") (pintype "passive"))
    )
    (net (code "125") (name "Net-(C51-2)") (class "Default")
      (node (ref "C51") (pin "-") (pinfunction "2_-") (pintype "passive"))
      (node (ref "IC12") (pin "1") (pinfunction "OUT_1") (pintype "output"))
      (node (ref "R344") (pin "2") (pinfunction "2_2") (pintype "passive"))
      (node (ref "R350") (pin "1") (pinfunction "1_1") (pintype "passive"))
    )
    (net (code "126") (name "Net-(C52-2)") (class "Default")
      (node (ref "C52") (pin "-") (pinfunction "2_-") (pintype "passive"))
      (node (ref "IC12") (pin "8") (pinfunction "OUT_8") (pintype "output"))
      (node (ref "R345") (pin "2") (pinfunction "2_2") (pintype "passive"))
      (node (ref "R351") (pin "1") (pinfunction "1_1") (pintype "passive"))
    )
    (net (code "127") (name "Net-(C53-2)") (class "Default")
      (node (ref "C53") (pin "-") (pinfunction "2_-") (pintype "passive"))
      (node (ref "IC13") (pin "1") (pinfunction "OUT_1") (pintype "output"))
      (node (ref "R346") (pin "2") (pinfunction "2_2") (pintype "passive"))
      (node (ref "R352") (pin "1") (pinfunction "1_1") (pintype "passive"))
    )
    (net (code "128") (name "Net-(C54-2)") (class "Default")
      (node (ref "C54") (pin "-") (pinfunction "2_-") (pintype "passive"))
      (node (ref "IC10") (pin "14") (pinfunction "OUT_14") (pintype "output"))
      (node (ref "R353") (pin "2") (pinfunction "2_2") (pintype "passive"))
      (node (ref "R359") (pin "1") (pinfunction "1_1") (pintype "passive"))
    )
    (net (code "129") (name "Net-(C55-2)") (class "Default")
      (node (ref "C55") (pin "-") (pinfunction "2_-") (pintype "passive"))
      (node (ref "IC11") (pin "7") (pinfunction "OUT_7") (pintype "output"))
      (node (ref "R354") (pin "2") (pinfunction "2_2") (pintype "passive"))
      (node (ref "R360") (pin "1") (pinfunction "1_1") (pintype "passive"))
    )
    (net (code "130") (name "Net-(C56-2)") (class "Default")
      (node (ref "C56") (pin "-") (pinfunction "2_-") (pintype "passive"))
      (node (ref "IC11") (pin "14") (pinfunction "OUT_14") (pintype "output"))
      (node (ref "R355") (pin "2") (pinfunction "2_2") (pintype "passive"))
      (node (ref "R361") (pin "1") (pinfunction "1_1") (pintype "passive"))
    )
    (net (code "131") (name "Net-(C57-2)") (class "Default")
      (node (ref "C57") (pin "-") (pinfunction "2_-") (pintype "passive"))
      (node (ref "IC12") (pin "7") (pinfunction "OUT_7") (pintype "output"))
      (node (ref "R356") (pin "2") (pinfunction "2_2") (pintype "passive"))
      (node (ref "R362") (pin "1") (pinfunction "1_1") (pintype "passive"))
    )
    (net (code "132") (name "Net-(C58-2)") (class "Default")
      (node (ref "C58") (pin "-") (pinfunction "2_-") (pintype "passive"))
      (node (ref "IC12") (pin "14") (pinfunction "OUT_14") (pintype "output"))
      (node (ref "R357") (pin "2") (pinfunction "2_2") (pintype "passive"))
      (node (ref "R363") (pin "1") (pinfunction "1_1") (pintype "passive"))
    )
    (net (code "133") (name "Net-(C59-2)") (class "Default")
      (node (ref "C59") (pin "-") (pinfunction "2_-") (pintype "passive"))
      (node (ref "IC13") (pin "7") (pinfunction "OUT_7") (pintype "output"))
      (node (ref "R358") (pin "2") (pinfunction "2_2") (pintype "passive"))
      (node (ref "R364") (pin "1") (pinfunction "1_1") (pintype "passive"))
    )
    (net (code "134") (name "Net-(IC1B-+IN)") (class "Default")
      (node (ref "IC1") (pin "5") (pinfunction "+IN_5") (pintype "input"))
      (node (ref "R3") (pin "2") (pinfunction "2_2") (pintype "passive"))
      (node (ref "R5") (pin "2") (pinfunction "2_2") (pintype "passive"))
    )
    (net (code "135") (name "Net-(IC2A--IN)") (class "Default")
      (node (ref "IC2") (pin "2") (pinfunction "-IN_2") (pintype "input"))
      (node (ref "R24") (pin "2") (pinfunction "2_2") (pintype "passive"))
      (node (ref "R28") (pin "1") (pinfunction "1_1") (pintype "passive"))
    )
    (net (code "136") (name "Net-(IC2B--IN)") (class "Default")
      (node (ref "IC2") (pin "6") (pinfunction "-IN_6") (pintype "input"))
      (node (ref "R26") (pin "2") (pinfunction "2_2") (pintype "passive"))
      (node (ref "R29") (pin "1") (pinfunction "1_1") (pintype "passive"))
    )
    (net (code "137") (name "Net-(IC2C--IN)") (class "Default")
      (node (ref "IC2") (pin "9") (pinfunction "-IN_9") (pintype "input"))
      (node (ref "R53") (pin "2") (pinfunction "2_2") (pintype "passive"))
      (node (ref "R57") (pin "1") (pinfunction "1_1") (pintype "passive"))
    )
    (net (code "138") (name "Net-(IC2D--IN)") (class "Default")
      (node (ref "IC2") (pin "13") (pinfunction "-IN_13") (pintype "input"))
      (node (ref "R52") (pin "2") (pinfunction "2_2") (pintype "passive"))
      (node (ref "R56") (pin "1") (pinfunction "1_1") (pintype "passive"))
    )
    (net (code "139") (name "Net-(IC3A--IN)") (class "Default")
      (node (ref "IC3") (pin "2") (pinfunction "-IN_2") (pintype "input"))
      (node (ref "R27") (pin "2") (pinfunction "2_2") (pintype "passive"))
      (node (ref "R31") (pin "1") (pinfunction "1_1") (pintype "passive"))
    )
    (net (code "140") (name "Net-(IC3B--IN)") (class "Default")
      (node (ref "IC3") (pin "6") (pinfunction "-IN_6") (pintype "input"))
      (node (ref "R25") (pin "2") (pinfunction "2_2") (pintype "passive"))
      (node (ref "R30") (pin "1") (pinfunction "1_1") (pintype "passive"))
    )
    (net (code "141") (name "Net-(IC3C--IN)") (class "Default")
      (node (ref "IC3") (pin "9") (pinfunction "-IN_9") (pintype "input"))
      (node (ref "R54") (pin "2") (pinfunction "2_2") (pintype "passive"))
      (node (ref "R58") (pin "1") (pinfunction "1_1") (pintype "passive"))
    )
    (net (code "142") (name "Net-(IC3D--IN)") (class "Default")
      (node (ref "IC3") (pin "13") (pinfunction "-IN_13") (pintype "input"))
      (node (ref "R55") (pin "2") (pinfunction "2_2") (pintype "passive"))
      (node (ref "R59") (pin "1") (pinfunction "1_1") (pintype "passive"))
    )
    (net (code "143") (name "Net-(IC4A-+IN)") (class "Default")
      (node (ref "IC4") (pin "3") (pinfunction "+IN_3") (pintype "input"))
      (node (ref "R65") (pin "2") (pinfunction "2_2") (pintype "passive"))
      (node (ref "R69") (pin "2") (pinfunction "2_2") (pintype "passive"))
    )
    (net (code "144") (name "Net-(IC5A--IN)") (class "Default")
      (node (ref "IC5") (pin "2") (pinfunction "-IN_2") (pintype "input"))
      (node (ref "R105") (pin "2") (pinfunction "2_2") (pintype "passive"))
      (node (ref "R111") (pin "1") (pinfunction "1_1") (pintype "passive"))
    )
    (net (code "145") (name "Net-(IC5B--IN)") (class "Default")
      (node (ref "IC5") (pin "6") (pinfunction "-IN_6") (pintype "input"))
      (node (ref "R106") (pin "2") (pinfunction "2_2") (pintype "passive"))
      (node (ref "R112") (pin "1") (pinfunction "1_1") (pintype "passive"))
    )
    (net (code "146") (name "Net-(IC5C--IN)") (class "Default")
      (node (ref "IC5") (pin "9") (pinfunction "-IN_9") (pintype "input"))
      (node (ref "R148") (pin "2") (pinfunction "2_2") (pintype "passive"))
      (node (ref "R154") (pin "1") (pinfunction "1_1") (pintype "passive"))
    )
    (net (code "147") (name "Net-(IC5D--IN)") (class "Default")
      (node (ref "IC5") (pin "13") (pinfunction "-IN_13") (pintype "input"))
      (node (ref "R147") (pin "2") (pinfunction "2_2") (pintype "passive"))
      (node (ref "R153") (pin "1") (pinfunction "1_1") (pintype "passive"))
    )
    (net (code "148") (name "Net-(IC6A--IN)") (class "Default")
      (node (ref "IC6") (pin "2") (pinfunction "-IN_2") (pintype "input"))
      (node (ref "R107") (pin "2") (pinfunction "2_2") (pintype "passive"))
      (node (ref "R113") (pin "1") (pinfunction "1_1") (pintype "passive"))
    )
    (net (code "149") (name "Net-(IC6B--IN)") (class "Default")
      (node (ref "IC6") (pin "6") (pinfunction "-IN_6") (pintype "input"))
      (node (ref "R108") (pin "2") (pinfunction "2_2") (pintype "passive"))
      (node (ref "R114") (pin "1") (pinfunction "1_1") (pintype "passive"))
    )
    (net (code "150") (name "Net-(IC6C--IN)") (class "Default")
      (node (ref "IC6") (pin "9") (pinfunction "-IN_9") (pintype "input"))
      (node (ref "R150") (pin "2") (pinfunction "2_2") (pintype "passive"))
      (node (ref "R156") (pin "1") (pinfunction "1_1") (pintype "passive"))
    )
    (net (code "151") (name "Net-(IC6D--IN)") (class "Default")
      (node (ref "IC6") (pin "13") (pinfunction "-IN_13") (pintype "input"))
      (node (ref "R149") (pin "2") (pinfunction "2_2") (pintype "passive"))
      (node (ref "R155") (pin "1") (pinfunction "1_1") (pintype "passive"))
    )
    (net (code "152") (name "Net-(IC7A--IN)") (class "Default")
      (node (ref "IC7") (pin "2") (pinfunction "-IN_2") (pintype "input"))
      (node (ref "R109") (pin "2") (pinfunction "2_2") (pintype "passive"))
      (node (ref "R115") (pin "1") (pinfunction "1_1") (pintype "passive"))
    )
    (net (code "153") (name "Net-(IC7B--IN)") (class "Default")
      (node (ref "IC7") (pin "6") (pinfunction "-IN_6") (pintype "input"))
      (node (ref "R110") (pin "2") (pinfunction "2_2") (pintype "passive"))
      (node (ref "R116") (pin "1") (pinfunction "1_1") (pintype "passive"))
    )
    (net (code "154") (name "Net-(IC7C--IN)") (class "Default")
      (node (ref "IC7") (pin "9") (pinfunction "-IN_9") (pintype "input"))
      (node (ref "R152") (pin "2") (pinfunction "2_2") (pintype "passive"))
      (node (ref "R158") (pin "1") (pinfunction "1_1") (pintype "passive"))
    )
    (net (code "155") (name "Net-(IC7D--IN)") (class "Default")
      (node (ref "IC7") (pin "13") (pinfunction "-IN_13") (pintype "input"))
      (node (ref "R151") (pin "2") (pinfunction "2_2") (pintype "passive"))
      (node (ref "R157") (pin "1") (pinfunction "1_1") (pintype "passive"))
    )
    (net (code "156") (name "Net-(IC8A--IN)") (class "Default")
      (node (ref "IC8") (pin "2") (pinfunction "-IN_2") (pintype "input"))
      (node (ref "R165") (pin "2") (pinfunction "2_2") (pintype "passive"))
      (node (ref "R171") (pin "1") (pinfunction "1_1") (pintype "passive"))
    )
    (net (code "157") (name "Net-(IC8B--IN)") (class "Default")
      (node (ref "IC8") (pin "6") (pinfunction "-IN_6") (pintype "input"))
      (node (ref "R166") (pin "2") (pinfunction "2_2") (pintype "passive"))
      (node (ref "R172") (pin "1") (pinfunction "1_1") (pintype "passive"))
    )
    (net (code "158") (name "Net-(IC9A--IN)") (class "Default")
      (node (ref "IC9") (pin "2") (pinfunction "-IN_2") (pintype "input"))
      (node (ref "R167") (pin "2") (pinfunction "2_2") (pintype "passive"))
      (node (ref "R173") (pin "1") (pinfunction "1_1") (pintype "passive"))
    )
    (net (code "159") (name "Net-(IC9B--IN)") (class "Default")
      (node (ref "IC9") (pin "6") (pinfunction "-IN_6") (pintype "input"))
      (node (ref "R168") (pin "2") (pinfunction "2_2") (pintype "passive"))
      (node (ref "R174") (pin "1") (pinfunction "1_1") (pintype "passive"))
    )
    (net (code "160") (name "Net-(IC9C--IN)") (class "Default")
      (node (ref "IC9") (pin "9") (pinfunction "-IN_9") (pintype "input"))
      (node (ref "R169") (pin "2") (pinfunction "2_2") (pintype "passive"))
      (node (ref "R175") (pin "1") (pinfunction "1_1") (pintype "passive"))
    )
    (net (code "161") (name "Net-(IC9D--IN)") (class "Default")
      (node (ref "IC9") (pin "13") (pinfunction "-IN_13") (pintype "input"))
      (node (ref "R170") (pin "2") (pinfunction "2_2") (pintype "passive"))
      (node (ref "R176") (pin "1") (pinfunction "1_1") (pintype "passive"))
    )
    (net (code "162") (name "Net-(R10-Pad2)") (class "Default")
      (node (ref "R10") (pin "2") (pinfunction "2_2") (pintype "passive"))
      (node (ref "R14") (pin "1") (pinfunction "1_1") (pintype "passive"))
    )
    (net (code "163") (name "Net-(R11-Pad2)") (class "Default")
      (node (ref "R11") (pin "2") (pinfunction "2_2") (pintype "passive"))
      (node (ref "R15") (pin "1") (pinfunction "1_1") (pintype "passive"))
    )
    (net (code "164") (name "Net-(R12-Pad1)") (class "Default")
      (node (ref "R12") (pin "1") (pinfunction "1_1") (pintype "passive"))
      (node (ref "R8") (pin "2") (pinfunction "2_2") (pintype "passive"))
    )
    (net (code "165") (name "Net-(R13-Pad1)") (class "Default")
      (node (ref "R13") (pin "1") (pinfunction "1_1") (pintype "passive"))
      (node (ref "R9") (pin "2") (pinfunction "2_2") (pintype "passive"))
    )
    (net (code "166") (name "Net-(R16-Pad1)") (class "Default")
      (node (ref "R16") (pin "1") (pinfunction "1_1") (pintype "passive"))
      (node (ref "R17") (pin "1") (pinfunction "1_1") (pintype "passive"))
    )
    (net (code "167") (name "Net-(R18-Pad1)") (class "Default")
      (node (ref "R18") (pin "1") (pinfunction "1_1") (pintype "passive"))
      (node (ref "R19") (pin "1") (pinfunction "1_1") (pintype "passive"))
    )
    (net (code "168") (name "Net-(R20-Pad1)") (class "Default")
      (node (ref "R20") (pin "1") (pinfunction "1_1") (pintype "passive"))
      (node (ref "R21") (pin "1") (pinfunction "1_1") (pintype "passive"))
    )
    (net (code "169") (name "Net-(R22-Pad1)") (class "Default")
      (node (ref "R22") (pin "1") (pinfunction "1_1") (pintype "passive"))
      (node (ref "R23") (pin "1") (pinfunction "1_1") (pintype "passive"))
    )
    (net (code "170") (name "Net-(R28-Pad2)") (class "Default")
      (node (ref "R28") (pin "2") (pinfunction "2_2") (pintype "passive"))
      (node (ref "R32") (pin "1") (pinfunction "1_1") (pintype "passive"))
    )
    (net (code "171") (name "Net-(R29-Pad2)") (class "Default")
      (node (ref "R29") (pin "2") (pinfunction "2_2") (pintype "passive"))
      (node (ref "R33") (pin "1") (pinfunction "1_1") (pintype "passive"))
    )
    (net (code "172") (name "Net-(R30-Pad2)") (class "Default")
      (node (ref "R30") (pin "2") (pinfunction "2_2") (pintype "passive"))
      (node (ref "R34") (pin "1") (pinfunction "1_1") (pintype "passive"))
    )
    (net (code "173") (name "Net-(R31-Pad2)") (class "Default")
      (node (ref "R31") (pin "2") (pinfunction "2_2") (pintype "passive"))
      (node (ref "R35") (pin "1") (pinfunction "1_1") (pintype "passive"))
    )
    (net (code "174") (name "Net-(R36-Pad2)") (class "Default")
      (node (ref "R36") (pin "2") (pinfunction "2_2") (pintype "passive"))
      (node (ref "R40") (pin "1") (pinfunction "1_1") (pintype "passive"))
    )
    (net (code "175") (name "Net-(R37-Pad2)") (class "Default")
      (node (ref "R37") (pin "2") (pinfunction "2_2") (pintype "passive"))
      (node (ref "R41") (pin "1") (pinfunction "1_1") (pintype "passive"))
    )
    (net (code "176") (name "Net-(R38-Pad2)") (class "Default")
      (node (ref "R38") (pin "2") (pinfunction "2_2") (pintype "passive"))
      (node (ref "R42") (pin "1") (pinfunction "1_1") (pintype "passive"))
    )
    (net (code "177") (name "Net-(R39-Pad2)") (class "Default")
      (node (ref "R39") (pin "2") (pinfunction "2_2") (pintype "passive"))
      (node (ref "R43") (pin "1") (pinfunction "1_1") (pintype "passive"))
    )
    (net (code "178") (name "Net-(R44-Pad1)") (class "Default")
      (node (ref "R44") (pin "1") (pinfunction "1_1") (pintype "passive"))
      (node (ref "R45") (pin "1") (pinfunction "1_1") (pintype "passive"))
    )
    (net (code "179") (name "Net-(R46-Pad1)") (class "Default")
      (node (ref "R46") (pin "1") (pinfunction "1_1") (pintype "passive"))
      (node (ref "R47") (pin "1") (pinfunction "1_1") (pintype "passive"))
    )
    (net (code "180") (name "Net-(R48-Pad1)") (class "Default")
      (node (ref "R48") (pin "1") (pinfunction "1_1") (pintype "passive"))
      (node (ref "R49") (pin "1") (pinfunction "1_1") (pintype "passive"))
    )
    (net (code "181") (name "Net-(R50-Pad1)") (class "Default")
      (node (ref "R50") (pin "1") (pinfunction "1_1") (pintype "passive"))
      (node (ref "R51") (pin "1") (pinfunction "1_1") (pintype "passive"))
    )
    (net (code "182") (name "Net-(R56-Pad2)") (class "Default")
      (node (ref "R56") (pin "2") (pinfunction "2_2") (pintype "passive"))
      (node (ref "R60") (pin "1") (pinfunction "1_1") (pintype "passive"))
    )
    (net (code "183") (name "Net-(R57-Pad2)") (class "Default")
      (node (ref "R57") (pin "2") (pinfunction "2_2") (pintype "passive"))
      (node (ref "R61") (pin "1") (pinfunction "1_1") (pintype "passive"))
    )
    (net (code "184") (name "Net-(R58-Pad2)") (class "Default")
      (node (ref "R58") (pin "2") (pinfunction "2_2") (pintype "passive"))
      (node (ref "R62") (pin "1") (pinfunction "1_1") (pintype "passive"))
    )
    (net (code "185") (name "Net-(R59-Pad2)") (class "Default")
      (node (ref "R59") (pin "2") (pinfunction "2_2") (pintype "passive"))
      (node (ref "R63") (pin "1") (pinfunction "1_1") (pintype "passive"))
    )
    (net (code "186") (name "Net-(R64-Pad2)") (class "Default")
      (node (ref "R64") (pin "2") (pinfunction "2_2") (pintype "passive"))
      (node (ref "R71") (pin "1") (pinfunction "1_1") (pintype "passive"))
    )
    (net (code "187") (name "Net-(R67-Pad2)") (class "Default")
      (node (ref "R67") (pin "2") (pinfunction "2_2") (pintype "passive"))
      (node (ref "R72") (pin "1") (pinfunction "1_1") (pintype "passive"))
    )
    (net (code "188") (name "Net-(R68-Pad2)") (class "Default")
      (node (ref "R68") (pin "2") (pinfunction "2_2") (pintype "passive"))
      (node (ref "R73") (pin "1") (pinfunction "1_1") (pintype "passive"))
    )
    (net (code "189") (name "Net-(R75-Pad2)") (class "Default")
      (node (ref "R75") (pin "2") (pinfunction "2_2") (pintype "passive"))
      (node (ref "R78") (pin "1") (pinfunction "1_1") (pintype "passive"))
    )
    (net (code "190") (name "Net-(R81-Pad2)") (class "Default")
      (node (ref "R81") (pin "2") (pinfunction "2_2") (pintype "passive"))
      (node (ref "R87") (pin "1") (pinfunction "1_1") (pintype "passive"))
    )
    (net (code "191") (name "Net-(R82-Pad2)") (class "Default")
      (node (ref "R82") (pin "2") (pinfunction "2_2") (pintype "passive"))
      (node (ref "R88") (pin "1") (pinfunction "1_1") (pintype "passive"))
    )
    (net (code "192") (name "Net-(R83-Pad2)") (class "Default")
      (node (ref "R83") (pin "2") (pinfunction "2_2") (pintype "passive"))
      (node (ref "R89") (pin "1") (pinfunction "1_1") (pintype "passive"))
    )
    (net (code "193") (name "Net-(R84-Pad2)") (class "Default")
      (node (ref "R84") (pin "2") (pinfunction "2_2") (pintype "passive"))
      (node (ref "R90") (pin "1") (pinfunction "1_1") (pintype "passive"))
    )
    (net (code "194") (name "Net-(R85-Pad2)") (class "Default")
      (node (ref "R85") (pin "2") (pinfunction "2_2") (pintype "passive"))
      (node (ref "R91") (pin "1") (pinfunction "1_1") (pintype "passive"))
    )
    (net (code "195") (name "Net-(R86-Pad2)") (class "Default")
      (node (ref "R86") (pin "2") (pinfunction "2_2") (pintype "passive"))
      (node (ref "R92") (pin "1") (pinfunction "1_1") (pintype "passive"))
    )
    (net (code "196") (name "Net-(R93-Pad1)") (class "Default")
      (node (ref "R93") (pin "1") (pinfunction "1_1") (pintype "passive"))
      (node (ref "R94") (pin "1") (pinfunction "1_1") (pintype "passive"))
    )
    (net (code "197") (name "Net-(R95-Pad1)") (class "Default")
      (node (ref "R95") (pin "1") (pinfunction "1_1") (pintype "passive"))
      (node (ref "R96") (pin "1") (pinfunction "1_1") (pintype "passive"))
    )
    (net (code "198") (name "Net-(R97-Pad1)") (class "Default")
      (node (ref "R97") (pin "1") (pinfunction "1_1") (pintype "passive"))
      (node (ref "R98") (pin "1") (pinfunction "1_1") (pintype "passive"))
    )
    (net (code "199") (name "Net-(R100-Pad1)") (class "Default")
      (node (ref "R100") (pin "1") (pinfunction "1_1") (pintype "passive"))
      (node (ref "R99") (pin "1") (pinfunction "1_1") (pintype "passive"))
    )
    (net (code "200") (name "Net-(R101-Pad1)") (class "Default")
      (node (ref "R101") (pin "1") (pinfunction "1_1") (pintype "passive"))
      (node (ref "R102") (pin "1") (pinfunction "1_1") (pintype "passive"))
    )
    (net (code "201") (name "Net-(R103-Pad1)") (class "Default")
      (node (ref "R103") (pin "1") (pinfunction "1_1") (pintype "passive"))
      (node (ref "R104") (pin "1") (pinfunction "1_1") (pintype "passive"))
    )
    (net (code "202") (name "Net-(R111-Pad2)") (class "Default")
      (node (ref "R111") (pin "2") (pinfunction "2_2") (pintype "passive"))
      (node (ref "R117") (pin "1") (pinfunction "1_1") (pintype "passive"))
    )
    (net (code "203") (name "Net-(R112-Pad2)") (class "Default")
      (node (ref "R112") (pin "2") (pinfunction "2_2") (pintype "passive"))
      (node (ref "R118") (pin "1") (pinfunction "1_1") (pintype "passive"))
    )
    (net (code "204") (name "Net-(R113-Pad2)") (class "Default")
      (node (ref "R113") (pin "2") (pinfunction "2_2") (pintype "passive"))
      (node (ref "R119") (pin "1") (pinfunction "1_1") (pintype "passive"))
    )
    (net (code "205") (name "Net-(R114-Pad2)") (class "Default")
      (node (ref "R114") (pin "2") (pinfunction "2_2") (pintype "passive"))
      (node (ref "R120") (pin "1") (pinfunction "1_1") (pintype "passive"))
    )
    (net (code "206") (name "Net-(R115-Pad2)") (class "Default")
      (node (ref "R115") (pin "2") (pinfunction "2_2") (pintype "passive"))
      (node (ref "R121") (pin "1") (pinfunction "1_1") (pintype "passive"))
    )
    (net (code "207") (name "Net-(R116-Pad2)") (class "Default")
      (node (ref "R116") (pin "2") (pinfunction "2_2") (pintype "passive"))
      (node (ref "R122") (pin "1") (pinfunction "1_1") (pintype "passive"))
    )
    (net (code "208") (name "Net-(R123-Pad2)") (class "Default")
      (node (ref "R123") (pin "2") (pinfunction "2_2") (pintype "passive"))
      (node (ref "R129") (pin "1") (pinfunction "1_1") (pintype "passive"))
    )
    (net (code "209") (name "Net-(R124-Pad2)") (class "Default")
      (node (ref "R124") (pin "2") (pinfunction "2_2") (pintype "passive"))
      (node (ref "R130") (pin "1") (pinfunction "1_1") (pintype "passive"))
    )
    (net (code "210") (name "Net-(R125-Pad2)") (class "Default")
      (node (ref "R125") (pin "2") (pinfunction "2_2") (pintype "passive"))
      (node (ref "R131") (pin "1") (pinfunction "1_1") (pintype "passive"))
    )
    (net (code "211") (name "Net-(R126-Pad2)") (class "Default")
      (node (ref "R126") (pin "2") (pinfunction "2_2") (pintype "passive"))
      (node (ref "R132") (pin "1") (pinfunction "1_1") (pintype "passive"))
    )
    (net (code "212") (name "Net-(R127-Pad2)") (class "Default")
      (node (ref "R127") (pin "2") (pinfunction "2_2") (pintype "passive"))
      (node (ref "R133") (pin "1") (pinfunction "1_1") (pintype "passive"))
    )
    (net (code "213") (name "Net-(R128-Pad2)") (class "Default")
      (node (ref "R128") (pin "2") (pinfunction "2_2") (pintype "passive"))
      (node (ref "R134") (pin "1") (pinfunction "1_1") (pintype "passive"))
    )
    (net (code "214") (name "Net-(R135-Pad1)") (class "Default")
      (node (ref "R135") (pin "1") (pinfunction "1_1") (pintype "passive"))
      (node (ref "R136") (pin "1") (pinfunction "1_1") (pintype "passive"))
    )
    (net (code "215") (name "Net-(R137-Pad1)") (class "Default")
      (node (ref "R137") (pin "1") (pinfunction "1_1") (pintype "passive"))
      (node (ref "R138") (pin "1") (pinfunction "1_1") (pintype "passive"))
    )
    (net (code "216") (name "Net-(R139-Pad1)") (class "Default")
      (node (ref "R139") (pin "1") (pinfunction "1_1") (pintype "passive"))
      (node (ref "R140") (pin "1") (pinfunction "1_1") (pintype "passive"))
    )
    (net (code "217") (name "Net-(R141-Pad1)") (class "Default")
      (node (ref "R141") (pin "1") (pinfunction "1_1") (pintype "passive"))
      (node (ref "R142") (pin "1") (pinfunction "1_1") (pintype "passive"))
    )
    (net (code "218") (name "Net-(R143-Pad1)") (class "Default")
      (node (ref "R143") (pin "1") (pinfunction "1_1") (pintype "passive"))
      (node (ref "R144") (pin "1") (pinfunction "1_1") (pintype "passive"))
    )
    (net (code "219") (name "Net-(R145-Pad1)") (class "Default")
      (node (ref "R145") (pin "1") (pinfunction "1_1") (pintype "passive"))
      (node (ref "R146") (pin "1") (pinfunction "1_1") (pintype "passive"))
    )
    (net (code "220") (name "Net-(R153-Pad2)") (class "Default")
      (node (ref "R153") (pin "2") (pinfunction "2_2") (pintype "passive"))
      (node (ref "R159") (pin "1") (pinfunction "1_1") (pintype "passive"))
    )
    (net (code "221") (name "Net-(R154-Pad2)") (class "Default")
      (node (ref "R154") (pin "2") (pinfunction "2_2") (pintype "passive"))
      (node (ref "R160") (pin "1") (pinfunction "1_1") (pintype "passive"))
    )
    (net (code "222") (name "Net-(R155-Pad2)") (class "Default")
      (node (ref "R155") (pin "2") (pinfunction "2_2") (pintype "passive"))
      (node (ref "R161") (pin "1") (pinfunction "1_1") (pintype "passive"))
    )
    (net (code "223") (name "Net-(R156-Pad2)") (class "Default")
      (node (ref "R156") (pin "2") (pinfunction "2_2") (pintype "passive"))
      (node (ref "R162") (pin "1") (pinfunction "1_1") (pintype "passive"))
    )
    (net (code "224") (name "Net-(R157-Pad2)") (class "Default")
      (node (ref "R157") (pin "2") (pinfunction "2_2") (pintype "passive"))
      (node (ref "R163") (pin "1") (pinfunction "1_1") (pintype "passive"))
    )
    (net (code "225") (name "Net-(R158-Pad2)") (class "Default")
      (node (ref "R158") (pin "2") (pinfunction "2_2") (pintype "passive"))
      (node (ref "R164") (pin "1") (pinfunction "1_1") (pintype "passive"))
    )
    (net (code "226") (name "Net-(R177-Pad2)") (class "Default")
      (node (ref "R177") (pin "2") (pinfunction "2_2") (pintype "passive"))
      (node (ref "R205") (pin "1") (pinfunction "1_1") (pintype "passive"))
    )
    (net (code "227") (name "Net-(R178-Pad2)") (class "Default")
      (node (ref "R178") (pin "2") (pinfunction "2_2") (pintype "passive"))
      (node (ref "R206") (pin "1") (pinfunction "1_1") (pintype "passive"))
    )
    (net (code "228") (name "Net-(R179-Pad2)") (class "Default")
      (node (ref "R179") (pin "2") (pinfunction "2_2") (pintype "passive"))
      (node (ref "R207") (pin "1") (pinfunction "1_1") (pintype "passive"))
    )
    (net (code "229") (name "Net-(R180-Pad2)") (class "Default")
      (node (ref "R180") (pin "2") (pinfunction "2_2") (pintype "passive"))
      (node (ref "R208") (pin "1") (pinfunction "1_1") (pintype "passive"))
    )
    (net (code "230") (name "Net-(R181-Pad2)") (class "Default")
      (node (ref "R181") (pin "2") (pinfunction "2_2") (pintype "passive"))
      (node (ref "R209") (pin "1") (pinfunction "1_1") (pintype "passive"))
    )
    (net (code "231") (name "Net-(R182-Pad2)") (class "Default")
      (node (ref "R182") (pin "2") (pinfunction "2_2") (pintype "passive"))
      (node (ref "R210") (pin "1") (pinfunction "1_1") (pintype "passive"))
    )
    (net (code "232") (name "Net-(R183-Pad2)") (class "Default")
      (node (ref "R183") (pin "2") (pinfunction "2_2") (pintype "passive"))
      (node (ref "R211") (pin "1") (pinfunction "1_1") (pintype "passive"))
    )
    (net (code "233") (name "Net-(R184-Pad2)") (class "Default")
      (node (ref "R184") (pin "2") (pinfunction "2_2") (pintype "passive"))
      (node (ref "R212") (pin "1") (pinfunction "1_1") (pintype "passive"))
    )
    (net (code "234") (name "Net-(R185-Pad2)") (class "Default")
      (node (ref "R185") (pin "2") (pinfunction "2_2") (pintype "passive"))
      (node (ref "R213") (pin "1") (pinfunction "1_1") (pintype "passive"))
    )
    (net (code "235") (name "Net-(R186-Pad2)") (class "Default")
      (node (ref "R186") (pin "2") (pinfunction "2_2") (pintype "passive"))
      (node (ref "R214") (pin "1") (pinfunction "1_1") (pintype "passive"))
    )
    (net (code "236") (name "Net-(R187-Pad2)") (class "Default")
      (node (ref "R187") (pin "2") (pinfunction "2_2") (pintype "passive"))
      (node (ref "R215") (pin "1") (pinfunction "1_1") (pintype "passive"))
    )
    (net (code "237") (name "Net-(R188-Pad2)") (class "Default")
      (node (ref "R188") (pin "2") (pinfunction "2_2") (pintype "passive"))
      (node (ref "R216") (pin "1") (pinfunction "1_1") (pintype "passive"))
    )
    (net (code "238") (name "Net-(R190-Pad2)") (class "Default")
      (node (ref "R190") (pin "2") (pinfunction "2_2") (pintype "passive"))
      (node (ref "R217") (pin "1") (pinfunction "1_1") (pintype "passive"))
    )
    (net (code "239") (name "Net-(R191-Pad2)") (class "Default")
      (node (ref "R191") (pin "2") (pinfunction "2_2") (pintype "passive"))
      (node (ref "R218") (pin "1") (pinfunction "1_1") (pintype "passive"))
    )
    (net (code "240") (name "Net-(R192-Pad2)") (class "Default")
      (node (ref "R192") (pin "2") (pinfunction "2_2") (pintype "passive"))
      (node (ref "R219") (pin "1") (pinfunction "1_1") (pintype "passive"))
    )
    (net (code "241") (name "Net-(R193-Pad2)") (class "Default")
      (node (ref "R193") (pin "2") (pinfunction "2_2") (pintype "passive"))
      (node (ref "R220") (pin "1") (pinfunction "1_1") (pintype "passive"))
    )
    (net (code "242") (name "Net-(R194-Pad2)") (class "Default")
      (node (ref "R194") (pin "2") (pinfunction "2_2") (pintype "passive"))
      (node (ref "R221") (pin "1") (pinfunction "1_1") (pintype "passive"))
    )
    (net (code "243") (name "Net-(R195-Pad2)") (class "Default")
      (node (ref "R195") (pin "2") (pinfunction "2_2") (pintype "passive"))
      (node (ref "R222") (pin "1") (pinfunction "1_1") (pintype "passive"))
    )
    (net (code "244") (name "Net-(R196-Pad2)") (class "Default")
      (node (ref "R196") (pin "2") (pinfunction "2_2") (pintype "passive"))
      (node (ref "R223") (pin "1") (pinfunction "1_1") (pintype "passive"))
    )
    (net (code "245") (name "Net-(R197-Pad2)") (class "Default")
      (node (ref "R197") (pin "2") (pinfunction "2_2") (pintype "passive"))
      (node (ref "R224") (pin "1") (pinfunction "1_1") (pintype "passive"))
    )
    (net (code "246") (name "Net-(R198-Pad2)") (class "Default")
      (node (ref "R198") (pin "2") (pinfunction "2_2") (pintype "passive"))
      (node (ref "R225") (pin "1") (pinfunction "1_1") (pintype "passive"))
    )
    (net (code "247") (name "Net-(R199-Pad2)") (class "Default")
      (node (ref "R199") (pin "2") (pinfunction "2_2") (pintype "passive"))
      (node (ref "R226") (pin "1") (pinfunction "1_1") (pintype "passive"))
    )
    (net (code "248") (name "Net-(R200-Pad2)") (class "Default")
      (node (ref "R200") (pin "2") (pinfunction "2_2") (pintype "passive"))
      (node (ref "R227") (pin "1") (pinfunction "1_1") (pintype "passive"))
    )
    (net (code "249") (name "Net-(R201-Pad2)") (class "Default")
      (node (ref "R201") (pin "2") (pinfunction "2_2") (pintype "passive"))
      (node (ref "R228") (pin "1") (pinfunction "1_1") (pintype "passive"))
    )
    (net (code "250") (name "Net-(R202-Pad2)") (class "Default")
      (node (ref "R202") (pin "2") (pinfunction "2_2") (pintype "passive"))
      (node (ref "R229") (pin "1") (pinfunction "1_1") (pintype "passive"))
    )
    (net (code "251") (name "Net-(R204-Pad2)") (class "Default")
      (node (ref "R204") (pin "2") (pinfunction "2_2") (pintype "passive"))
      (node (ref "R230") (pin "1") (pinfunction "1_1") (pintype "passive"))
    )
    (net (code "252") (name "Net-(R231-Pad2)") (class "Default")
      (node (ref "R231") (pin "2") (pinfunction "2_2") (pintype "passive"))
      (node (ref "R259") (pin "1") (pinfunction "1_1") (pintype "passive"))
    )
    (net (code "253") (name "Net-(R232-Pad2)") (class "Default")
      (node (ref "R232") (pin "2") (pinfunction "2_2") (pintype "passive"))
      (node (ref "R260") (pin "1") (pinfunction "1_1") (pintype "passive"))
    )
    (net (code "254") (name "Net-(R233-Pad2)") (class "Default")
      (node (ref "R233") (pin "2") (pinfunction "2_2") (pintype "passive"))
      (node (ref "R261") (pin "1") (pinfunction "1_1") (pintype "passive"))
    )
    (net (code "255") (name "Net-(R234-Pad2)") (class "Default")
      (node (ref "R234") (pin "2") (pinfunction "2_2") (pintype "passive"))
      (node (ref "R262") (pin "1") (pinfunction "1_1") (pintype "passive"))
    )
    (net (code "256") (name "Net-(R235-Pad2)") (class "Default")
      (node (ref "R235") (pin "2") (pinfunction "2_2") (pintype "passive"))
      (node (ref "R263") (pin "1") (pinfunction "1_1") (pintype "passive"))
    )
    (net (code "257") (name "Net-(R236-Pad2)") (class "Default")
      (node (ref "R236") (pin "2") (pinfunction "2_2") (pintype "passive"))
      (node (ref "R264") (pin "1") (pinfunction "1_1") (pintype "passive"))
    )
    (net (code "258") (name "Net-(R237-Pad2)") (class "Default")
      (node (ref "R237") (pin "2") (pinfunction "2_2") (pintype "passive"))
      (node (ref "R265") (pin "1") (pinfunction "1_1") (pintype "passive"))
    )
    (net (code "259") (name "Net-(R238-Pad2)") (class "Default")
      (node (ref "R238") (pin "2") (pinfunction "2_2") (pintype "passive"))
      (node (ref "R266") (pin "1") (pinfunction "1_1") (pintype "passive"))
    )
    (net (code "260") (name "Net-(R239-Pad2)") (class "Default")
      (node (ref "R239") (pin "2") (pinfunction "2_2") (pintype "passive"))
      (node (ref "R267") (pin "1") (pinfunction "1_1") (pintype "passive"))
    )
    (net (code "261") (name "Net-(R240-Pad2)") (class "Default")
      (node (ref "R240") (pin "2") (pinfunction "2_2") (pintype "passive"))
      (node (ref "R268") (pin "1") (pinfunction "1_1") (pintype "passive"))
    )
    (net (code "262") (name "Net-(R241-Pad2)") (class "Default")
      (node (ref "R241") (pin "2") (pinfunction "2_2") (pintype "passive"))
      (node (ref "R269") (pin "1") (pinfunction "1_1") (pintype "passive"))
    )
    (net (code "263") (name "Net-(R242-Pad2)") (class "Default")
      (node (ref "R242") (pin "2") (pinfunction "2_2") (pintype "passive"))
      (node (ref "R270") (pin "1") (pinfunction "1_1") (pintype "passive"))
    )
    (net (code "264") (name "Net-(R244-Pad2)") (class "Default")
      (node (ref "R244") (pin "2") (pinfunction "2_2") (pintype "passive"))
      (node (ref "R271") (pin "1") (pinfunction "1_1") (pintype "passive"))
    )
    (net (code "265") (name "Net-(R245-Pad2)") (class "Default")
      (node (ref "R245") (pin "2") (pinfunction "2_2") (pintype "passive"))
      (node (ref "R272") (pin "1") (pinfunction "1_1") (pintype "passive"))
    )
    (net (code "266") (name "Net-(R246-Pad2)") (class "Default")
      (node (ref "R246") (pin "2") (pinfunction "2_2") (pintype "passive"))
      (node (ref "R273") (pin "1") (pinfunction "1_1") (pintype "passive"))
    )
    (net (code "267") (name "Net-(R247-Pad2)") (class "Default")
      (node (ref "R247") (pin "2") (pinfunction "2_2") (pintype "passive"))
      (node (ref "R274") (pin "1") (pinfunction "1_1") (pintype "passive"))
    )
    (net (code "268") (name "Net-(R248-Pad2)") (class "Default")
      (node (ref "R248") (pin "2") (pinfunction "2_2") (pintype "passive"))
      (node (ref "R275") (pin "1") (pinfunction "1_1") (pintype "passive"))
    )
    (net (code "269") (name "Net-(R249-Pad2)") (class "Default")
      (node (ref "R249") (pin "2") (pinfunction "2_2") (pintype "passive"))
      (node (ref "R276") (pin "1") (pinfunction "1_1") (pintype "passive"))
    )
    (net (code "270") (name "Net-(R250-Pad2)") (class "Default")
      (node (ref "R250") (pin "2") (pinfunction "2_2") (pintype "passive"))
      (node (ref "R277") (pin "1") (pinfunction "1_1") (pintype "passive"))
    )
    (net (code "271") (name "Net-(R251-Pad2)") (class "Default")
      (node (ref "R251") (pin "2") (pinfunction "2_2") (pintype "passive"))
      (node (ref "R278") (pin "1") (pinfunction "1_1") (pintype "passive"))
    )
    (net (code "272") (name "Net-(R252-Pad2)") (class "Default")
      (node (ref "R252") (pin "2") (pinfunction "2_2") (pintype "passive"))
      (node (ref "R279") (pin "1") (pinfunction "1_1") (pintype "passive"))
    )
    (net (code "273") (name "Net-(R253-Pad2)") (class "Default")
      (node (ref "R253") (pin "2") (pinfunction "2_2") (pintype "passive"))
      (node (ref "R280") (pin "1") (pinfunction "1_1") (pintype "passive"))
    )
    (net (code "274") (name "Net-(R254-Pad2)") (class "Default")
      (node (ref "R254") (pin "2") (pinfunction "2_2") (pintype "passive"))
      (node (ref "R281") (pin "1") (pinfunction "1_1") (pintype "passive"))
    )
    (net (code "275") (name "Net-(R255-Pad2)") (class "Default")
      (node (ref "R255") (pin "2") (pinfunction "2_2") (pintype "passive"))
      (node (ref "R282") (pin "1") (pinfunction "1_1") (pintype "passive"))
    )
    (net (code "276") (name "Net-(R256-Pad2)") (class "Default")
      (node (ref "R256") (pin "2") (pinfunction "2_2") (pintype "passive"))
      (node (ref "R283") (pin "1") (pinfunction "1_1") (pintype "passive"))
    )
    (net (code "277") (name "Net-(R258-Pad2)") (class "Default")
      (node (ref "R258") (pin "2") (pinfunction "2_2") (pintype "passive"))
      (node (ref "R284") (pin "1") (pinfunction "1_1") (pintype "passive"))
    )
    (net (code "278") (name "Net-(R290-Pad2)") (class "Default")
      (node (ref "R290") (pin "2") (pinfunction "2_2") (pintype "passive"))
      (node (ref "R305") (pin "1") (pinfunction "1_1") (pintype "passive"))
    )
    (net (code "279") (name "Net-(R291-Pad2)") (class "Default")
      (node (ref "R291") (pin "2") (pinfunction "2_2") (pintype "passive"))
      (node (ref "R306") (pin "1") (pinfunction "1_1") (pintype "passive"))
    )
    (net (code "280") (name "Net-(R293-Pad2)") (class "Default")
      (node (ref "R293") (pin "2") (pinfunction "2_2") (pintype "passive"))
      (node (ref "R307") (pin "1") (pinfunction "1_1") (pintype "passive"))
    )
    (net (code "281") (name "Net-(R294-Pad2)") (class "Default")
      (node (ref "R294") (pin "2") (pinfunction "2_2") (pintype "passive"))
      (node (ref "R308") (pin "1") (pinfunction "1_1") (pintype "passive"))
    )
    (net (code "282") (name "Net-(R296-Pad2)") (class "Default")
      (node (ref "R296") (pin "2") (pinfunction "2_2") (pintype "passive"))
      (node (ref "R309") (pin "1") (pinfunction "1_1") (pintype "passive"))
    )
    (net (code "283") (name "Net-(R298-Pad2)") (class "Default")
      (node (ref "R298") (pin "2") (pinfunction "2_2") (pintype "passive"))
      (node (ref "R310") (pin "1") (pinfunction "1_1") (pintype "passive"))
    )
    (net (code "284") (name "Net-(R299-Pad2)") (class "Default")
      (node (ref "R299") (pin "2") (pinfunction "2_2") (pintype "passive"))
      (node (ref "R311") (pin "1") (pinfunction "1_1") (pintype "passive"))
    )
    (net (code "285") (name "Net-(R301-Pad2)") (class "Default")
      (node (ref "R301") (pin "2") (pinfunction "2_2") (pintype "passive"))
      (node (ref "R312") (pin "1") (pinfunction "1_1") (pintype "passive"))
    )
    (net (code "286") (name "Net-(R302-Pad2)") (class "Default")
      (node (ref "R302") (pin "2") (pinfunction "2_2") (pintype "passive"))
      (node (ref "R313") (pin "1") (pinfunction "1_1") (pintype "passive"))
    )
    (net (code "287") (name "Net-(R304-Pad2)") (class "Default")
      (node (ref "R304") (pin "2") (pinfunction "2_2") (pintype "passive"))
      (node (ref "R314") (pin "1") (pinfunction "1_1") (pintype "passive"))
    )
    (net (code "288") (name "Net-(R316-Pad2)") (class "Default")
      (node (ref "R316") (pin "2") (pinfunction "2_2") (pintype "passive"))
      (node (ref "R331") (pin "1") (pinfunction "1_1") (pintype "passive"))
    )
    (net (code "289") (name "Net-(R317-Pad2)") (class "Default")
      (node (ref "R317") (pin "2") (pinfunction "2_2") (pintype "passive"))
      (node (ref "R332") (pin "1") (pinfunction "1_1") (pintype "passive"))
    )
    (net (code "290") (name "Net-(R319-Pad2)") (class "Default")
      (node (ref "R319") (pin "2") (pinfunction "2_2") (pintype "passive"))
      (node (ref "R333") (pin "1") (pinfunction "1_1") (pintype "passive"))
    )
    (net (code "291") (name "Net-(R320-Pad2)") (class "Default")
      (node (ref "R320") (pin "2") (pinfunction "2_2") (pintype "passive"))
      (node (ref "R334") (pin "1") (pinfunction "1_1") (pintype "passive"))
    )
    (net (code "292") (name "Net-(R322-Pad2)") (class "Default")
      (node (ref "R322") (pin "2") (pinfunction "2_2") (pintype "passive"))
      (node (ref "R335") (pin "1") (pinfunction "1_1") (pintype "passive"))
    )
    (net (code "293") (name "Net-(R324-Pad2)") (class "Default")
      (node (ref "R324") (pin "2") (pinfunction "2_2") (pintype "passive"))
      (node (ref "R336") (pin "1") (pinfunction "1_1") (pintype "passive"))
    )
    (net (code "294") (name "Net-(R325-Pad2)") (class "Default")
      (node (ref "R325") (pin "2") (pinfunction "2_2") (pintype "passive"))
      (node (ref "R337") (pin "1") (pinfunction "1_1") (pintype "passive"))
    )
    (net (code "295") (name "Net-(R327-Pad2)") (class "Default")
      (node (ref "R327") (pin "2") (pinfunction "2_2") (pintype "passive"))
      (node (ref "R338") (pin "1") (pinfunction "1_1") (pintype "passive"))
    )
    (net (code "296") (name "Net-(R328-Pad2)") (class "Default")
      (node (ref "R328") (pin "2") (pinfunction "2_2") (pintype "passive"))
      (node (ref "R339") (pin "1") (pinfunction "1_1") (pintype "passive"))
    )
    (net (code "297") (name "Net-(R330-Pad2)") (class "Default")
      (node (ref "R330") (pin "2") (pinfunction "2_2") (pintype "passive"))
      (node (ref "R340") (pin "1") (pinfunction "1_1") (pintype "passive"))
    )
    (net (code "298") (name "SIGMA") (class "Default")
      (node (ref "IC2") (pin "14") (pinfunction "OUT_14") (pintype "output"))
      (node (ref "R60") (pin "2") (pinfunction "2_2") (pintype "passive"))
      (node (ref "R66") (pin "1") (pinfunction "1_1") (pintype "passive"))
      (node (ref "R70") (pin "1") (pinfunction "1_1") (pintype "passive"))
    )
    (net (code "299") (name "W0") (class "Default")
      (node (ref "IC6") (pin "14") (pinfunction "OUT_14") (pintype "output"))
      (node (ref "R161") (pin "2") (pinfunction "2_2") (pintype "passive"))
      (node (ref "R167") (pin "1") (pinfunction "1_1") (pintype "passive"))
      (node (ref "R177") (pin "1") (pinfunction "1_1") (pintype "passive"))
      (node (ref "R183") (pin "1") (pinfunction "1_1") (pintype "passive"))
      (node (ref "R245") (pin "1") (pinfunction "1_1") (pintype "passive"))
      (node (ref "R251") (pin "1") (pinfunction "1_1") (pintype "passive"))
      (node (ref "R257") (pin "1") (pinfunction "1_1") (pintype "passive"))
    )
    (net (code "300") (name "W90") (class "Default")
      (node (ref "IC6") (pin "8") (pinfunction "OUT_8") (pintype "output"))
      (node (ref "R162") (pin "2") (pinfunction "2_2") (pintype "passive"))
      (node (ref "R168") (pin "1") (pinfunction "1_1") (pintype "passive"))
      (node (ref "R231") (pin "1") (pinfunction "1_1") (pintype "passive"))
      (node (ref "R237") (pin "1") (pinfunction "1_1") (pintype "passive"))
      (node (ref "R246") (pin "1") (pinfunction "1_1") (pintype "passive"))
      (node (ref "R252") (pin "1") (pinfunction "1_1") (pintype "passive"))
    )
    (net (code "301") (name "W180") (class "Default")
      (node (ref "IC9") (pin "1") (pinfunction "OUT_1") (pintype "output"))
      (node (ref "R173") (pin "2") (pinfunction "2_2") (pintype "passive"))
      (node (ref "R191") (pin "1") (pinfunction "1_1") (pintype "passive"))
      (node (ref "R197") (pin "1") (pinfunction "1_1") (pintype "passive"))
      (node (ref "R203") (pin "1") (pinfunction "1_1") (pintype "passive"))
      (node (ref "R232") (pin "1") (pinfunction "1_1") (pintype "passive"))
      (node (ref "R238") (pin "1") (pinfunction "1_1") (pintype "passive"))
    )
    (net (code "302") (name "W270") (class "Default")
      (node (ref "IC9") (pin "7") (pinfunction "OUT_7") (pintype "output"))
      (node (ref "R174") (pin "2") (pinfunction "2_2") (pintype "passive"))
      (node (ref "R178") (pin "1") (pinfunction "1_1") (pintype "passive"))
      (node (ref "R184") (pin "1") (pinfunction "1_1") (pintype "passive"))
      (node (ref "R189") (pin "1") (pinfunction "1_1") (pintype "passive"))
      (node (ref "R192") (pin "1") (pinfunction "1_1") (pintype "passive"))
      (node (ref "R198") (pin "1") (pinfunction "1_1") (pintype "passive"))
    )
    (net (code "303") (name "WC") (class "Default")
      (node (ref "C23") (pin "+") (pinfunction "1_+") (pintype "passive"))
      (node (ref "C25") (pin "+") (pinfunction "1_+") (pintype "passive"))
      (node (ref "R107") (pin "1") (pinfunction "1_1") (pintype "passive"))
      (node (ref "R108") (pin "1") (pinfunction "1_1") (pintype "passive"))
      (node (ref "R289") (pin "1") (pinfunction "1_1") (pintype "passive"))
      (node (ref "R292") (pin "1") (pinfunction "1_1") (pintype "passive"))
      (node (ref "R295") (pin "1") (pinfunction "1_1") (pintype "passive"))
      (node (ref "R297") (pin "1") (pinfunction "1_1") (pintype "passive"))
      (node (ref "R300") (pin "1") (pinfunction "1_1") (pintype "passive"))
      (node (ref "R303") (pin "1") (pinfunction "1_1") (pintype "passive"))
      (node (ref "R315") (pin "1") (pinfunction "1_1") (pintype "passive"))
      (node (ref "R318") (pin "1") (pinfunction "1_1") (pintype "passive"))
      (node (ref "R321") (pin "1") (pinfunction "1_1") (pintype "passive"))
      (node (ref "R323") (pin "1") (pinfunction "1_1") (pintype "passive"))
      (node (ref "R326") (pin "1") (pinfunction "1_1") (pintype "passive"))
      (node (ref "R329") (pin "1") (pinfunction "1_1") (pintype "passive"))
      (node (ref "R80") (pin "2") (pinfunction "2_2") (pintype "passive"))
      (node (ref "R83") (pin "1") (pinfunction "1_1") (pintype "passive"))
      (node (ref "R84") (pin "1") (pinfunction "1_1") (pintype "passive"))
    )
    (net (code "304") (name "X0") (class "Default")
      (node (ref "IC7") (pin "14") (pinfunction "OUT_14") (pintype "output"))
      (node (ref "R163") (pin "2") (pinfunction "2_2") (pintype "passive"))
      (node (ref "R169") (pin "1") (pinfunction "1_1") (pintype "passive"))
      (node (ref "R179") (pin "1") (pinfunction "1_1") (pintype "passive"))
      (node (ref "R185") (pin "1") (pinfunction "1_1") (pintype "passive"))
      (node (ref "R193") (pin "1") (pinfunction "1_1") (pintype "passive"))
      (node (ref "R199") (pin "1") (pinfunction "1_1") (pintype "passive"))
      (node (ref "R204") (pin "1") (pinfunction "1_1") (pintype "passive"))
      (node (ref "R233") (pin "1") (pinfunction "1_1") (pintype "passive"))
      (node (ref "R239") (pin "1") (pinfunction "1_1") (pintype "passive"))
      (node (ref "R247") (pin "1") (pinfunction "1_1") (pintype "passive"))
      (node (ref "R253") (pin "1") (pinfunction "1_1") (pintype "passive"))
      (node (ref "R258") (pin "1") (pinfunction "1_1") (pintype "passive"))
    )
    (net (code "305") (name "X90") (class "Default")
      (node (ref "IC7") (pin "8") (pinfunction "OUT_8") (pintype "output"))
      (node (ref "R164") (pin "2") (pinfunction "2_2") (pintype "passive"))
      (node (ref "R170") (pin "1") (pinfunction "1_1") (pintype "passive"))
      (node (ref "R194") (pin "1") (pinfunction "1_1") (pintype "passive"))
      (node (ref "R200") (pin "1") (pinfunction "1_1") (pintype "passive"))
      (node (ref "R248") (pin "1") (pinfunction "1_1") (pintype "passive"))
      (node (ref "R254") (pin "1") (pinfunction "1_1") (pintype "passive"))
    )
    (net (code "306") (name "X180") (class "Default")
      (node (ref "IC9") (pin "8") (pinfunction "OUT_8") (pintype "output"))
      (node (ref "R175") (pin "2") (pinfunction "2_2") (pintype "passive"))
    )
    (net (code "307") (name "X270") (class "Default")
      (node (ref "IC9") (pin "14") (pinfunction "OUT_14") (pintype "output"))
      (node (ref "R176") (pin "2") (pinfunction "2_2") (pintype "passive"))
      (node (ref "R180") (pin "1") (pinfunction "1_1") (pintype "passive"))
      (node (ref "R186") (pin "1") (pinfunction "1_1") (pintype "passive"))
      (node (ref "R234") (pin "1") (pinfunction "1_1") (pintype "passive"))
      (node (ref "R240") (pin "1") (pinfunction "1_1") (pintype "passive"))
    )
    (net (code "308") (name "XC") (class "Default")
      (node (ref "C26") (pin "+") (pinfunction "1_+") (pintype "passive"))
      (node (ref "C27") (pin "+") (pinfunction "1_+") (pintype "passive"))
      (node (ref "R109") (pin "1") (pinfunction "1_1") (pintype "passive"))
      (node (ref "R110") (pin "1") (pinfunction "1_1") (pintype "passive"))
      (node (ref "R285") (pin "1") (pinfunction "1_1") (pintype "passive"))
      (node (ref "R290") (pin "1") (pinfunction "1_1") (pintype "passive"))
      (node (ref "R293") (pin "1") (pinfunction "1_1") (pintype "passive"))
      (node (ref "R324") (pin "1") (pinfunction "1_1") (pintype "passive"))
      (node (ref "R327") (pin "1") (pinfunction "1_1") (pintype "passive"))
      (node (ref "R330") (pin "1") (pinfunction "1_1") (pintype "passive"))
      (node (ref "R77") (pin "2") (pinfunction "2_2") (pintype "passive"))
      (node (ref "R85") (pin "1") (pinfunction "1_1") (pintype "passive"))
      (node (ref "R86") (pin "1") (pinfunction "1_1") (pintype "passive"))
    )
    (net (code "309") (name "Y0") (class "Default")
      (node (ref "IC5") (pin "14") (pinfunction "OUT_14") (pintype "output"))
      (node (ref "R159") (pin "2") (pinfunction "2_2") (pintype "passive"))
      (node (ref "R165") (pin "1") (pinfunction "1_1") (pintype "passive"))
      (node (ref "R195") (pin "1") (pinfunction "1_1") (pintype "passive"))
      (node (ref "R201") (pin "1") (pinfunction "1_1") (pintype "passive"))
      (node (ref "R243") (pin "1") (pinfunction "1_1") (pintype "passive"))
      (node (ref "R249") (pin "1") (pinfunction "1_1") (pintype "passive"))
      (node (ref "R255") (pin "1") (pinfunction "1_1") (pintype "passive"))
    )
    (net (code "310") (name "Y90") (class "Default")
      (node (ref "IC5") (pin "8") (pinfunction "OUT_8") (pintype "output"))
      (node (ref "R160") (pin "2") (pinfunction "2_2") (pintype "passive"))
      (node (ref "R166") (pin "1") (pinfunction "1_1") (pintype "passive"))
      (node (ref "R181") (pin "1") (pinfunction "1_1") (pintype "passive"))
      (node (ref "R187") (pin "1") (pinfunction "1_1") (pintype "passive"))
      (node (ref "R190") (pin "1") (pinfunction "1_1") (pintype "passive"))
      (node (ref "R196") (pin "1") (pinfunction "1_1") (pintype "passive"))
      (node (ref "R202") (pin "1") (pinfunction "1_1") (pintype "passive"))
      (node (ref "R235") (pin "1") (pinfunction "1_1") (pintype "passive"))
      (node (ref "R241") (pin "1") (pinfunction "1_1") (pintype "passive"))
      (node (ref "R244") (pin "1") (pinfunction "1_1") (pintype "passive"))
      (node (ref "R250") (pin "1") (pinfunction "1_1") (pintype "passive"))
      (node (ref "R256") (pin "1") (pinfunction "1_1") (pintype "passive"))
    )
    (net (code "311") (name "Y180") (class "Default")
      (node (ref "IC8") (pin "1") (pinfunction "OUT_1") (pintype "output"))
      (node (ref "R171") (pin "2") (pinfunction "2_2") (pintype "passive"))
      (node (ref "R182") (pin "1") (pinfunction "1_1") (pintype "passive"))
      (node (ref "R188") (pin "1") (pinfunction "1_1") (pintype "passive"))
      (node (ref "R236") (pin "1") (pinfunction "1_1") (pintype "passive"))
      (node (ref "R242") (pin "1") (pinfunction "1_1") (pintype "passive"))
    )
    (net (code "312") (name "Y270") (class "Default")
      (node (ref "IC8") (pin "7") (pinfunction "OUT_7") (pintype "output"))
      (node (ref "R172") (pin "2") (pinfunction "2_2") (pintype "passive"))
    )
    (net (code "313") (name "YC") (class "Default")
      (node (ref "C22") (pin "+") (pinfunction "1_+") (pintype "passive"))
      (node (ref "C24") (pin "+") (pinfunction "1_+") (pintype "passive"))
      (node (ref "R105") (pin "1") (pinfunction "1_1") (pintype "passive"))
      (node (ref "R106") (pin "1") (pinfunction "1_1") (pintype "passive"))
      (node (ref "R286") (pin "1") (pinfunction "1_1") (pintype "passive"))
      (node (ref "R317") (pin "1") (pinfunction "1_1") (pintype "passive"))
      (node (ref "R320") (pin "1") (pinfunction "1_1") (pintype "passive"))
      (node (ref "R322") (pin "1") (pinfunction "1_1") (pintype "passive"))
      (node (ref "R325") (pin "1") (pinfunction "1_1") (pintype "passive"))
      (node (ref "R328") (pin "1") (pinfunction "1_1") (pintype "passive"))
      (node (ref "R79") (pin "2") (pinfunction "2_2") (pintype "passive"))
      (node (ref "R81") (pin "1") (pinfunction "1_1") (pintype "passive"))
      (node (ref "R82") (pin "1") (pinfunction "1_1") (pintype "passive"))
    )
    (net (code "314") (name "unconnected-(J1-Pad10)") (class "Default")
      (node (ref "J1") (pin "10") (pinfunction "10_10") (pintype "bidirectional"))
    )
    (net (code "315") (name "unconnected-(J1-Pad11)") (class "Default")
      (node (ref "J1") (pin "11") (pinfunction "11_11") (pintype "bidirectional"))
    )
    (net (code "316") (name "unconnected-(J1-Pad12)") (class "Default")
      (node (ref "J1") (pin "12") (pinfunction "12_12") (pintype "bidirectional"))
    )
    (net (code "317") (name "unconnected-(J1-Pad13)") (class "Default")
      (node (ref "J1") (pin "13") (pinfunction "13_13") (pintype "bidirectional"))
    )
    (net (code "318") (name "unconnected-(J1-Pad14)") (class "Default")
      (node (ref "J1") (pin "14") (pinfunction "14_14") (pintype "bidirectional"))
    )
    (net (code "319") (name "unconnected-(J1-Pad15)") (class "Default")
      (node (ref "J1") (pin "15") (pinfunction "15_15") (pintype "bidirectional"))
    )
    (net (code "320") (name "unconnected-(J1-Pad16)") (class "Default")
      (node (ref "J1") (pin "16") (pinfunction "16_16") (pintype "bidirectional"))
    )
    (net (code "321") (name "unconnected-(J2-Pad13)") (class "Default")
      (node (ref "J2") (pin "13") (pinfunction "13_13") (pintype "bidirectional"))
    )
    (net (code "322") (name "unconnected-(J2-Pad14)") (class "Default")
      (node (ref "J2") (pin "14") (pinfunction "14_14") (pintype "bidirectional"))
    )
    (net (code "323") (name "unconnected-(J2-Pad15)") (class "Default")
      (node (ref "J2") (pin "15") (pinfunction "15_15") (pintype "bidirectional"))
    )
    (net (code "324") (name "unconnected-(J2-Pad16)") (class "Default")
      (node (ref "J2") (pin "16") (pinfunction "16_16") (pintype "bidirectional"))
    )
    (net (code "325") (name "unconnected-(J3-Pad13)") (class "Default")
      (node (ref "J3") (pin "13") (pinfunction "13_13") (pintype "bidirectional"))
    )
    (net (code "326") (name "unconnected-(J3-Pad14)") (class "Default")
      (node (ref "J3") (pin "14") (pinfunction "14_14") (pintype "bidirectional"))
    )
    (net (code "327") (name "unconnected-(J3-Pad15)") (class "Default")
      (node (ref "J3") (pin "15") (pinfunction "15_15") (pintype "bidirectional"))
    )
    (net (code "328") (name "unconnected-(J3-Pad16)") (class "Default")
      (node (ref "J3") (pin "16") (pinfunction "16_16") (pintype "bidirectional"))
    )
  )
)
